# WS2812-Ring_v100.net
KiCad netlist of a schematic drawn in EAGLE
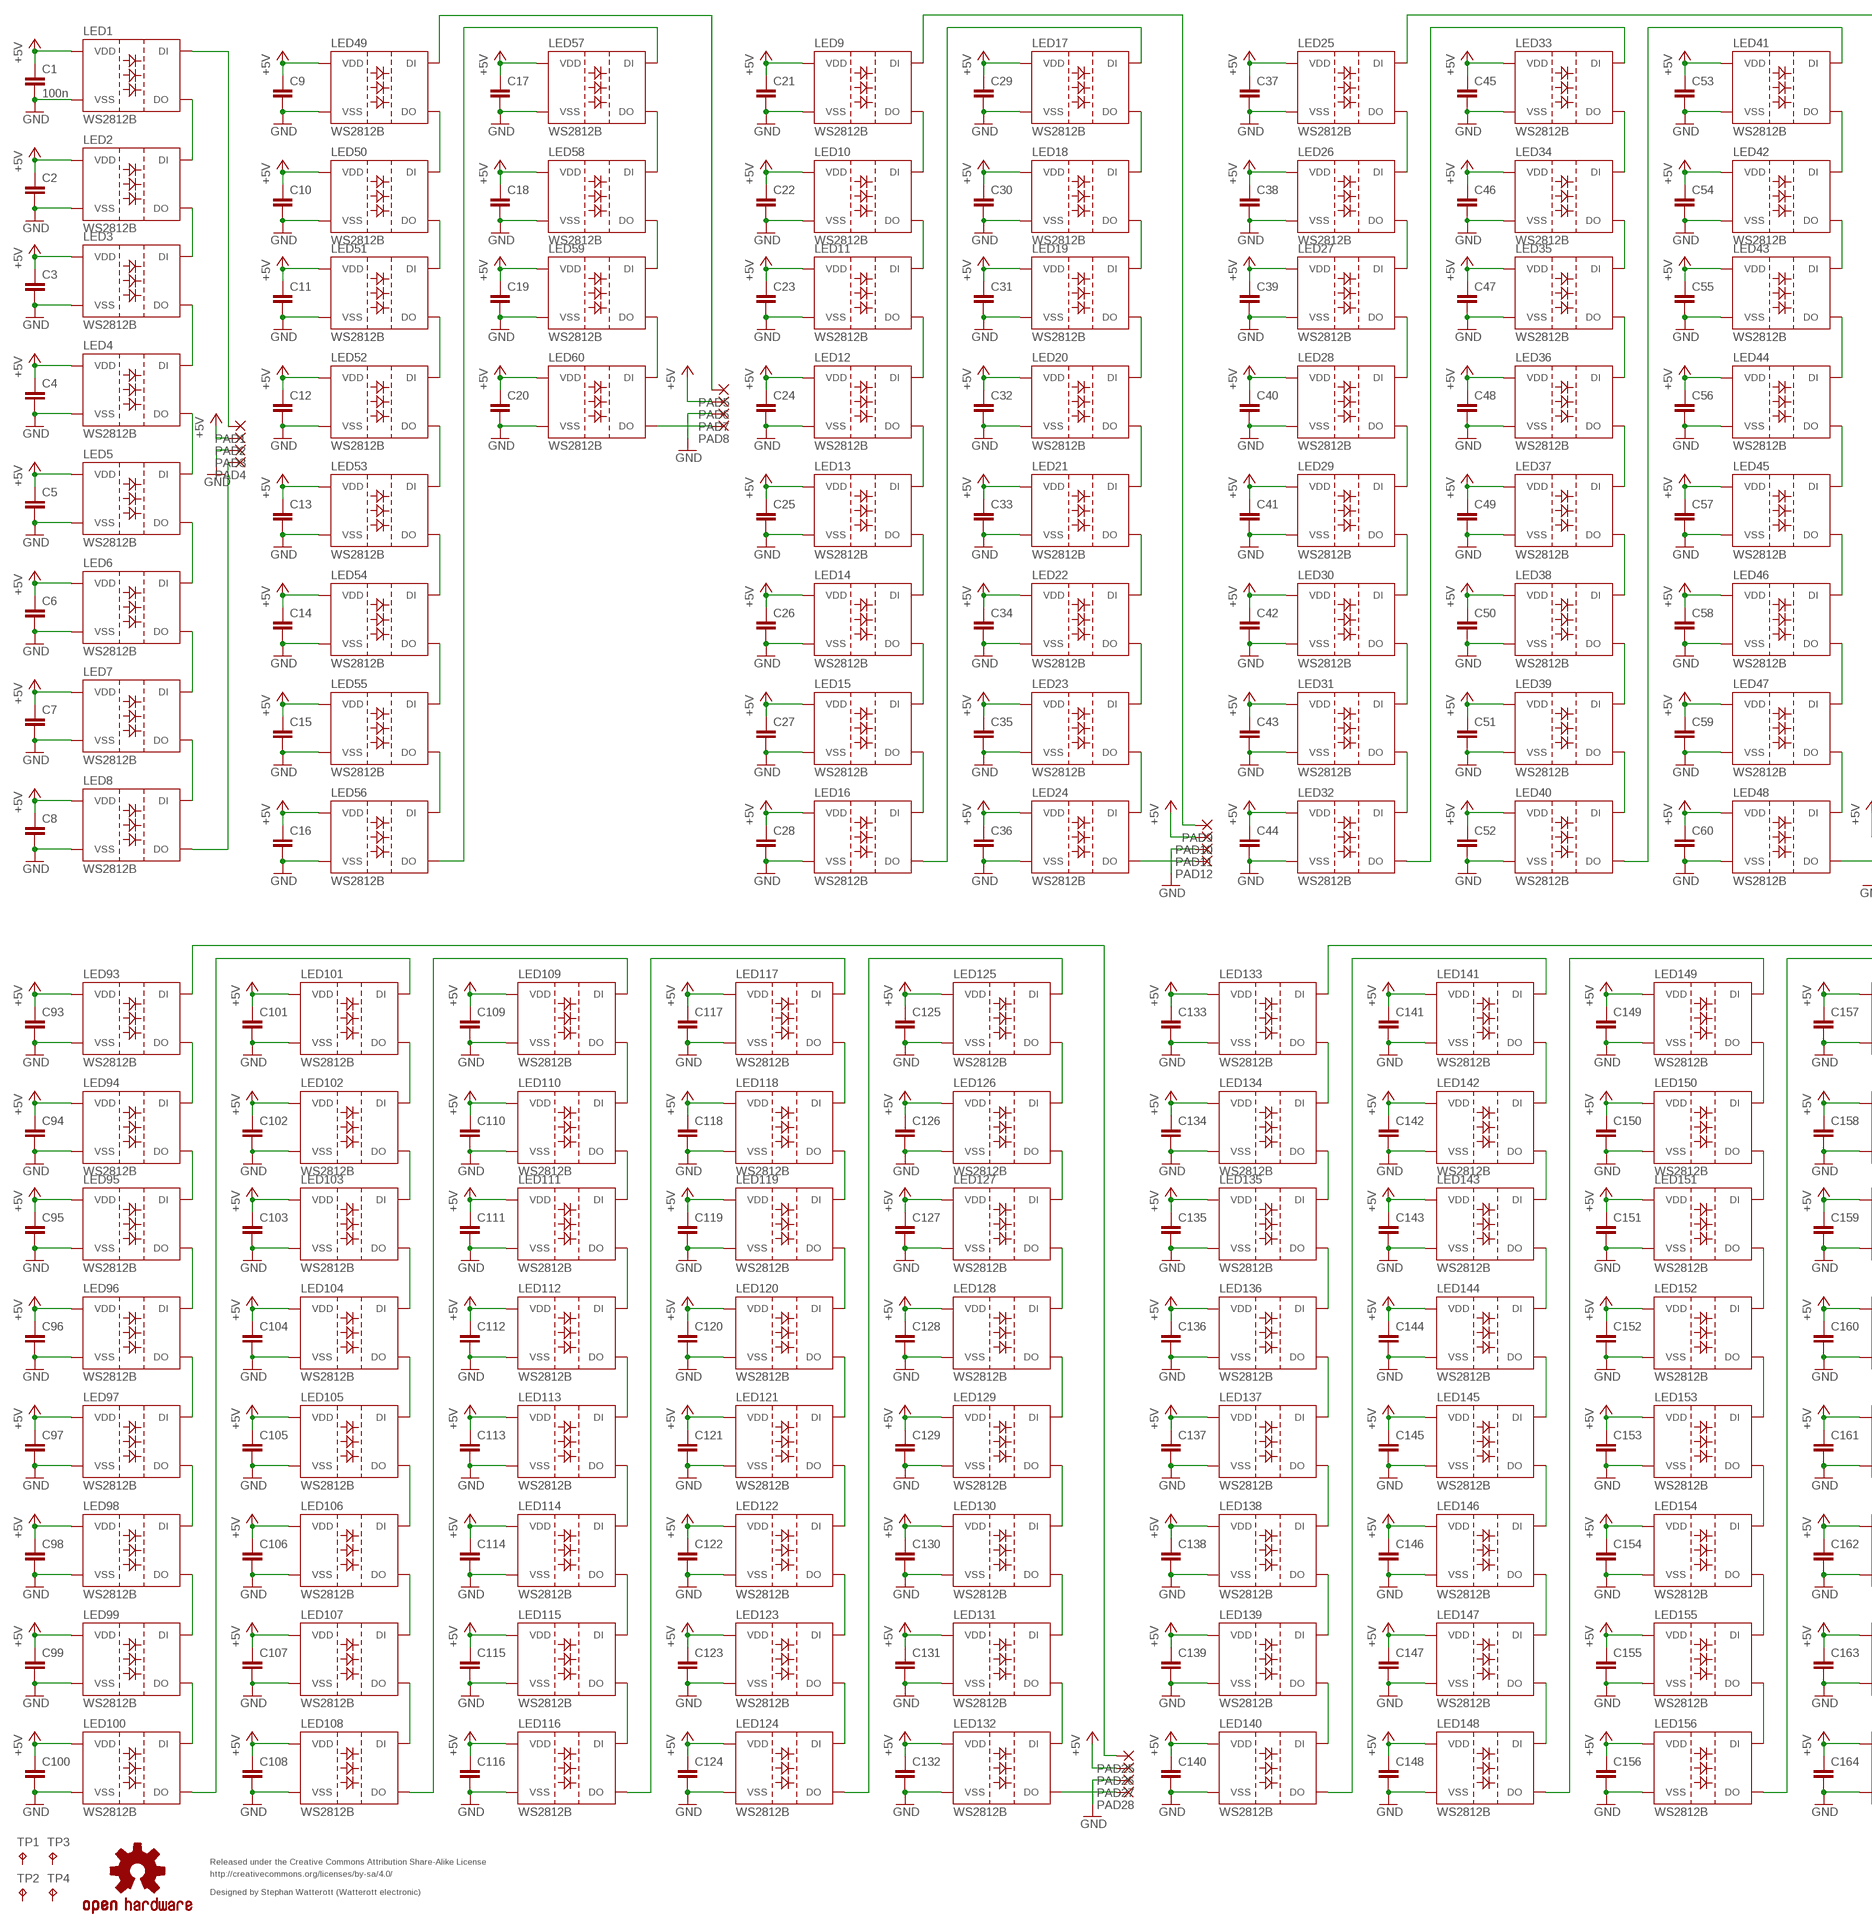
[diagram p0: schematic, sheet 1, part 1 of 2]
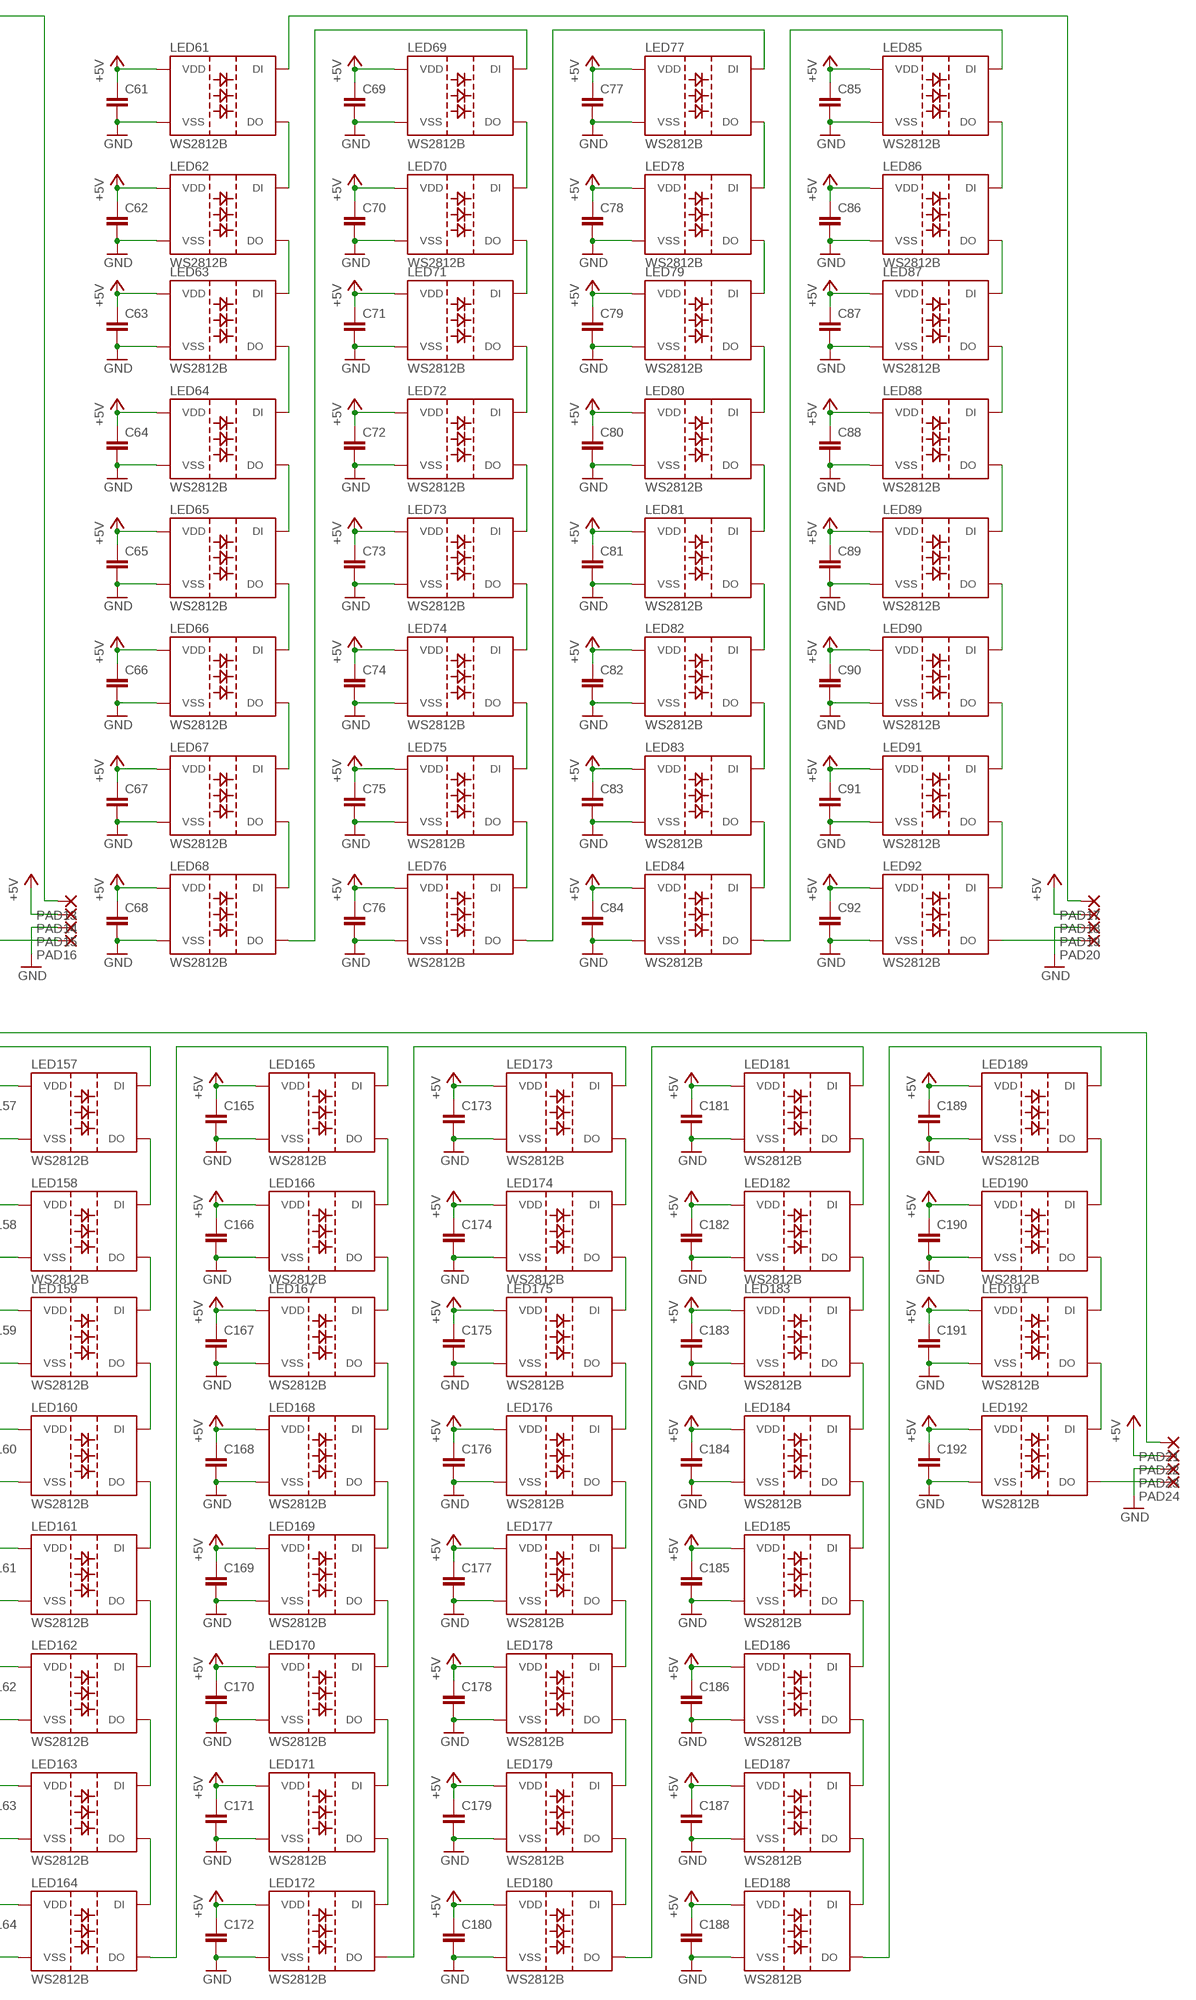
[diagram p1: schematic, sheet 1, part 2 of 2]

(export (version "E")
  (design (tool "Eeschema 10.0.6"))
  (components
    (comp (ref "C1")
      (value "100n")
      (footprint "eagle-import:C0402K")
      (libsource (lib "eagle-import") (part "C-EUC0402K"))
    )
    (comp (ref "C2")
      (value "C-EUC0402K")
      (footprint "eagle-import:C0402K")
      (libsource (lib "eagle-import") (part "C-EUC0402K"))
    )
    (comp (ref "C3")
      (value "C-EUC0402K")
      (footprint "eagle-import:C0402K")
      (libsource (lib "eagle-import") (part "C-EUC0402K"))
    )
    (comp (ref "C4")
      (value "C-EUC0402K")
      (footprint "eagle-import:C0402K")
      (libsource (lib "eagle-import") (part "C-EUC0402K"))
    )
    (comp (ref "C5")
      (value "C-EUC0402K")
      (footprint "eagle-import:C0402K")
      (libsource (lib "eagle-import") (part "C-EUC0402K"))
    )
    (comp (ref "C6")
      (value "C-EUC0402K")
      (footprint "eagle-import:C0402K")
      (libsource (lib "eagle-import") (part "C-EUC0402K"))
    )
    (comp (ref "C7")
      (value "C-EUC0402K")
      (footprint "eagle-import:C0402K")
      (libsource (lib "eagle-import") (part "C-EUC0402K"))
    )
    (comp (ref "C8")
      (value "C-EUC0402K")
      (footprint "eagle-import:C0402K")
      (libsource (lib "eagle-import") (part "C-EUC0402K"))
    )
    (comp (ref "C9")
      (value "C-EUC0402K")
      (footprint "eagle-import:C0402K")
      (libsource (lib "eagle-import") (part "C-EUC0402K"))
    )
    (comp (ref "C10")
      (value "C-EUC0402K")
      (footprint "eagle-import:C0402K")
      (libsource (lib "eagle-import") (part "C-EUC0402K"))
    )
    (comp (ref "C11")
      (value "C-EUC0402K")
      (footprint "eagle-import:C0402K")
      (libsource (lib "eagle-import") (part "C-EUC0402K"))
    )
    (comp (ref "C12")
      (value "C-EUC0402K")
      (footprint "eagle-import:C0402K")
      (libsource (lib "eagle-import") (part "C-EUC0402K"))
    )
    (comp (ref "C13")
      (value "C-EUC0402K")
      (footprint "eagle-import:C0402K")
      (libsource (lib "eagle-import") (part "C-EUC0402K"))
    )
    (comp (ref "C14")
      (value "C-EUC0402K")
      (footprint "eagle-import:C0402K")
      (libsource (lib "eagle-import") (part "C-EUC0402K"))
    )
    (comp (ref "C15")
      (value "C-EUC0402K")
      (footprint "eagle-import:C0402K")
      (libsource (lib "eagle-import") (part "C-EUC0402K"))
    )
    (comp (ref "C16")
      (value "C-EUC0402K")
      (footprint "eagle-import:C0402K")
      (libsource (lib "eagle-import") (part "C-EUC0402K"))
    )
    (comp (ref "C17")
      (value "C-EUC0402K")
      (footprint "eagle-import:C0402K")
      (libsource (lib "eagle-import") (part "C-EUC0402K"))
    )
    (comp (ref "C18")
      (value "C-EUC0402K")
      (footprint "eagle-import:C0402K")
      (libsource (lib "eagle-import") (part "C-EUC0402K"))
    )
    (comp (ref "C19")
      (value "C-EUC0402K")
      (footprint "eagle-import:C0402K")
      (libsource (lib "eagle-import") (part "C-EUC0402K"))
    )
    (comp (ref "C20")
      (value "C-EUC0402K")
      (footprint "eagle-import:C0402K")
      (libsource (lib "eagle-import") (part "C-EUC0402K"))
    )
    (comp (ref "C21")
      (value "C-EUC0402K")
      (footprint "eagle-import:C0402K")
      (libsource (lib "eagle-import") (part "C-EUC0402K"))
    )
    (comp (ref "C22")
      (value "C-EUC0402K")
      (footprint "eagle-import:C0402K")
      (libsource (lib "eagle-import") (part "C-EUC0402K"))
    )
    (comp (ref "C23")
      (value "C-EUC0402K")
      (footprint "eagle-import:C0402K")
      (libsource (lib "eagle-import") (part "C-EUC0402K"))
    )
    (comp (ref "C24")
      (value "C-EUC0402K")
      (footprint "eagle-import:C0402K")
      (libsource (lib "eagle-import") (part "C-EUC0402K"))
    )
    (comp (ref "C25")
      (value "C-EUC0402K")
      (footprint "eagle-import:C0402K")
      (libsource (lib "eagle-import") (part "C-EUC0402K"))
    )
    (comp (ref "C26")
      (value "C-EUC0402K")
      (footprint "eagle-import:C0402K")
      (libsource (lib "eagle-import") (part "C-EUC0402K"))
    )
    (comp (ref "C27")
      (value "C-EUC0402K")
      (footprint "eagle-import:C0402K")
      (libsource (lib "eagle-import") (part "C-EUC0402K"))
    )
    (comp (ref "C28")
      (value "C-EUC0402K")
      (footprint "eagle-import:C0402K")
      (libsource (lib "eagle-import") (part "C-EUC0402K"))
    )
    (comp (ref "C29")
      (value "C-EUC0402K")
      (footprint "eagle-import:C0402K")
      (libsource (lib "eagle-import") (part "C-EUC0402K"))
    )
    (comp (ref "C30")
      (value "C-EUC0402K")
      (footprint "eagle-import:C0402K")
      (libsource (lib "eagle-import") (part "C-EUC0402K"))
    )
    (comp (ref "C31")
      (value "C-EUC0402K")
      (footprint "eagle-import:C0402K")
      (libsource (lib "eagle-import") (part "C-EUC0402K"))
    )
    (comp (ref "C32")
      (value "C-EUC0402K")
      (footprint "eagle-import:C0402K")
      (libsource (lib "eagle-import") (part "C-EUC0402K"))
    )
    (comp (ref "C33")
      (value "C-EUC0402K")
      (footprint "eagle-import:C0402K")
      (libsource (lib "eagle-import") (part "C-EUC0402K"))
    )
    (comp (ref "C34")
      (value "C-EUC0402K")
      (footprint "eagle-import:C0402K")
      (libsource (lib "eagle-import") (part "C-EUC0402K"))
    )
    (comp (ref "C35")
      (value "C-EUC0402K")
      (footprint "eagle-import:C0402K")
      (libsource (lib "eagle-import") (part "C-EUC0402K"))
    )
    (comp (ref "C36")
      (value "C-EUC0402K")
      (footprint "eagle-import:C0402K")
      (libsource (lib "eagle-import") (part "C-EUC0402K"))
    )
    (comp (ref "C37")
      (value "C-EUC0402K")
      (footprint "eagle-import:C0402K")
      (libsource (lib "eagle-import") (part "C-EUC0402K"))
    )
    (comp (ref "C38")
      (value "C-EUC0402K")
      (footprint "eagle-import:C0402K")
      (libsource (lib "eagle-import") (part "C-EUC0402K"))
    )
    (comp (ref "C39")
      (value "C-EUC0402K")
      (footprint "eagle-import:C0402K")
      (libsource (lib "eagle-import") (part "C-EUC0402K"))
    )
    (comp (ref "C40")
      (value "C-EUC0402K")
      (footprint "eagle-import:C0402K")
      (libsource (lib "eagle-import") (part "C-EUC0402K"))
    )
    (comp (ref "C41")
      (value "C-EUC0402K")
      (footprint "eagle-import:C0402K")
      (libsource (lib "eagle-import") (part "C-EUC0402K"))
    )
    (comp (ref "C42")
      (value "C-EUC0402K")
      (footprint "eagle-import:C0402K")
      (libsource (lib "eagle-import") (part "C-EUC0402K"))
    )
    (comp (ref "C43")
      (value "C-EUC0402K")
      (footprint "eagle-import:C0402K")
      (libsource (lib "eagle-import") (part "C-EUC0402K"))
    )
    (comp (ref "C44")
      (value "C-EUC0402K")
      (footprint "eagle-import:C0402K")
      (libsource (lib "eagle-import") (part "C-EUC0402K"))
    )
    (comp (ref "C45")
      (value "C-EUC0402K")
      (footprint "eagle-import:C0402K")
      (libsource (lib "eagle-import") (part "C-EUC0402K"))
    )
    (comp (ref "C46")
      (value "C-EUC0402K")
      (footprint "eagle-import:C0402K")
      (libsource (lib "eagle-import") (part "C-EUC0402K"))
    )
    (comp (ref "C47")
      (value "C-EUC0402K")
      (footprint "eagle-import:C0402K")
      (libsource (lib "eagle-import") (part "C-EUC0402K"))
    )
    (comp (ref "C48")
      (value "C-EUC0402K")
      (footprint "eagle-import:C0402K")
      (libsource (lib "eagle-import") (part "C-EUC0402K"))
    )
    (comp (ref "C49")
      (value "C-EUC0402K")
      (footprint "eagle-import:C0402K")
      (libsource (lib "eagle-import") (part "C-EUC0402K"))
    )
    (comp (ref "C50")
      (value "C-EUC0402K")
      (footprint "eagle-import:C0402K")
      (libsource (lib "eagle-import") (part "C-EUC0402K"))
    )
    (comp (ref "C51")
      (value "C-EUC0402K")
      (footprint "eagle-import:C0402K")
      (libsource (lib "eagle-import") (part "C-EUC0402K"))
    )
    (comp (ref "C52")
      (value "C-EUC0402K")
      (footprint "eagle-import:C0402K")
      (libsource (lib "eagle-import") (part "C-EUC0402K"))
    )
    (comp (ref "C53")
      (value "C-EUC0402K")
      (footprint "eagle-import:C0402K")
      (libsource (lib "eagle-import") (part "C-EUC0402K"))
    )
    (comp (ref "C54")
      (value "C-EUC0402K")
      (footprint "eagle-import:C0402K")
      (libsource (lib "eagle-import") (part "C-EUC0402K"))
    )
    (comp (ref "C55")
      (value "C-EUC0402K")
      (footprint "eagle-import:C0402K")
      (libsource (lib "eagle-import") (part "C-EUC0402K"))
    )
    (comp (ref "C56")
      (value "C-EUC0402K")
      (footprint "eagle-import:C0402K")
      (libsource (lib "eagle-import") (part "C-EUC0402K"))
    )
    (comp (ref "C57")
      (value "C-EUC0402K")
      (footprint "eagle-import:C0402K")
      (libsource (lib "eagle-import") (part "C-EUC0402K"))
    )
    (comp (ref "C58")
      (value "C-EUC0402K")
      (footprint "eagle-import:C0402K")
      (libsource (lib "eagle-import") (part "C-EUC0402K"))
    )
    (comp (ref "C59")
      (value "C-EUC0402K")
      (footprint "eagle-import:C0402K")
      (libsource (lib "eagle-import") (part "C-EUC0402K"))
    )
    (comp (ref "C60")
      (value "C-EUC0402K")
      (footprint "eagle-import:C0402K")
      (libsource (lib "eagle-import") (part "C-EUC0402K"))
    )
    (comp (ref "C61")
      (value "C-EUC0402K")
      (footprint "eagle-import:C0402K")
      (libsource (lib "eagle-import") (part "C-EUC0402K"))
    )
    (comp (ref "C62")
      (value "C-EUC0402K")
      (footprint "eagle-import:C0402K")
      (libsource (lib "eagle-import") (part "C-EUC0402K"))
    )
    (comp (ref "C63")
      (value "C-EUC0402K")
      (footprint "eagle-import:C0402K")
      (libsource (lib "eagle-import") (part "C-EUC0402K"))
    )
    (comp (ref "C64")
      (value "C-EUC0402K")
      (footprint "eagle-import:C0402K")
      (libsource (lib "eagle-import") (part "C-EUC0402K"))
    )
    (comp (ref "C65")
      (value "C-EUC0402K")
      (footprint "eagle-import:C0402K")
      (libsource (lib "eagle-import") (part "C-EUC0402K"))
    )
    (comp (ref "C66")
      (value "C-EUC0402K")
      (footprint "eagle-import:C0402K")
      (libsource (lib "eagle-import") (part "C-EUC0402K"))
    )
    (comp (ref "C67")
      (value "C-EUC0402K")
      (footprint "eagle-import:C0402K")
      (libsource (lib "eagle-import") (part "C-EUC0402K"))
    )
    (comp (ref "C68")
      (value "C-EUC0402K")
      (footprint "eagle-import:C0402K")
      (libsource (lib "eagle-import") (part "C-EUC0402K"))
    )
    (comp (ref "C69")
      (value "C-EUC0402K")
      (footprint "eagle-import:C0402K")
      (libsource (lib "eagle-import") (part "C-EUC0402K"))
    )
    (comp (ref "C70")
      (value "C-EUC0402K")
      (footprint "eagle-import:C0402K")
      (libsource (lib "eagle-import") (part "C-EUC0402K"))
    )
    (comp (ref "C71")
      (value "C-EUC0402K")
      (footprint "eagle-import:C0402K")
      (libsource (lib "eagle-import") (part "C-EUC0402K"))
    )
    (comp (ref "C72")
      (value "C-EUC0402K")
      (footprint "eagle-import:C0402K")
      (libsource (lib "eagle-import") (part "C-EUC0402K"))
    )
    (comp (ref "C73")
      (value "C-EUC0402K")
      (footprint "eagle-import:C0402K")
      (libsource (lib "eagle-import") (part "C-EUC0402K"))
    )
    (comp (ref "C74")
      (value "C-EUC0402K")
      (footprint "eagle-import:C0402K")
      (libsource (lib "eagle-import") (part "C-EUC0402K"))
    )
    (comp (ref "C75")
      (value "C-EUC0402K")
      (footprint "eagle-import:C0402K")
      (libsource (lib "eagle-import") (part "C-EUC0402K"))
    )
    (comp (ref "C76")
      (value "C-EUC0402K")
      (footprint "eagle-import:C0402K")
      (libsource (lib "eagle-import") (part "C-EUC0402K"))
    )
    (comp (ref "C77")
      (value "C-EUC0402K")
      (footprint "eagle-import:C0402K")
      (libsource (lib "eagle-import") (part "C-EUC0402K"))
    )
    (comp (ref "C78")
      (value "C-EUC0402K")
      (footprint "eagle-import:C0402K")
      (libsource (lib "eagle-import") (part "C-EUC0402K"))
    )
    (comp (ref "C79")
      (value "C-EUC0402K")
      (footprint "eagle-import:C0402K")
      (libsource (lib "eagle-import") (part "C-EUC0402K"))
    )
    (comp (ref "C80")
      (value "C-EUC0402K")
      (footprint "eagle-import:C0402K")
      (libsource (lib "eagle-import") (part "C-EUC0402K"))
    )
    (comp (ref "C81")
      (value "C-EUC0402K")
      (footprint "eagle-import:C0402K")
      (libsource (lib "eagle-import") (part "C-EUC0402K"))
    )
    (comp (ref "C82")
      (value "C-EUC0402K")
      (footprint "eagle-import:C0402K")
      (libsource (lib "eagle-import") (part "C-EUC0402K"))
    )
    (comp (ref "C83")
      (value "C-EUC0402K")
      (footprint "eagle-import:C0402K")
      (libsource (lib "eagle-import") (part "C-EUC0402K"))
    )
    (comp (ref "C84")
      (value "C-EUC0402K")
      (footprint "eagle-import:C0402K")
      (libsource (lib "eagle-import") (part "C-EUC0402K"))
    )
    (comp (ref "C85")
      (value "C-EUC0402K")
      (footprint "eagle-import:C0402K")
      (libsource (lib "eagle-import") (part "C-EUC0402K"))
    )
    (comp (ref "C86")
      (value "C-EUC0402K")
      (footprint "eagle-import:C0402K")
      (libsource (lib "eagle-import") (part "C-EUC0402K"))
    )
    (comp (ref "C87")
      (value "C-EUC0402K")
      (footprint "eagle-import:C0402K")
      (libsource (lib "eagle-import") (part "C-EUC0402K"))
    )
    (comp (ref "C88")
      (value "C-EUC0402K")
      (footprint "eagle-import:C0402K")
      (libsource (lib "eagle-import") (part "C-EUC0402K"))
    )
    (comp (ref "C89")
      (value "C-EUC0402K")
      (footprint "eagle-import:C0402K")
      (libsource (lib "eagle-import") (part "C-EUC0402K"))
    )
    (comp (ref "C90")
      (value "C-EUC0402K")
      (footprint "eagle-import:C0402K")
      (libsource (lib "eagle-import") (part "C-EUC0402K"))
    )
    (comp (ref "C91")
      (value "C-EUC0402K")
      (footprint "eagle-import:C0402K")
      (libsource (lib "eagle-import") (part "C-EUC0402K"))
    )
    (comp (ref "C92")
      (value "C-EUC0402K")
      (footprint "eagle-import:C0402K")
      (libsource (lib "eagle-import") (part "C-EUC0402K"))
    )
    (comp (ref "C93")
      (value "C-EUC0402K")
      (footprint "eagle-import:C0402K")
      (libsource (lib "eagle-import") (part "C-EUC0402K"))
    )
    (comp (ref "C94")
      (value "C-EUC0402K")
      (footprint "eagle-import:C0402K")
      (libsource (lib "eagle-import") (part "C-EUC0402K"))
    )
    (comp (ref "C95")
      (value "C-EUC0402K")
      (footprint "eagle-import:C0402K")
      (libsource (lib "eagle-import") (part "C-EUC0402K"))
    )
    (comp (ref "C96")
      (value "C-EUC0402K")
      (footprint "eagle-import:C0402K")
      (libsource (lib "eagle-import") (part "C-EUC0402K"))
    )
    (comp (ref "C97")
      (value "C-EUC0402K")
      (footprint "eagle-import:C0402K")
      (libsource (lib "eagle-import") (part "C-EUC0402K"))
    )
    (comp (ref "C98")
      (value "C-EUC0402K")
      (footprint "eagle-import:C0402K")
      (libsource (lib "eagle-import") (part "C-EUC0402K"))
    )
    (comp (ref "C99")
      (value "C-EUC0402K")
      (footprint "eagle-import:C0402K")
      (libsource (lib "eagle-import") (part "C-EUC0402K"))
    )
    (comp (ref "C100")
      (value "C-EUC0402K")
      (footprint "eagle-import:C0402K")
      (libsource (lib "eagle-import") (part "C-EUC0402K"))
    )
    (comp (ref "C101")
      (value "C-EUC0402K")
      (footprint "eagle-import:C0402K")
      (libsource (lib "eagle-import") (part "C-EUC0402K"))
    )
    (comp (ref "C102")
      (value "C-EUC0402K")
      (footprint "eagle-import:C0402K")
      (libsource (lib "eagle-import") (part "C-EUC0402K"))
    )
    (comp (ref "C103")
      (value "C-EUC0402K")
      (footprint "eagle-import:C0402K")
      (libsource (lib "eagle-import") (part "C-EUC0402K"))
    )
    (comp (ref "C104")
      (value "C-EUC0402K")
      (footprint "eagle-import:C0402K")
      (libsource (lib "eagle-import") (part "C-EUC0402K"))
    )
    (comp (ref "C105")
      (value "C-EUC0402K")
      (footprint "eagle-import:C0402K")
      (libsource (lib "eagle-import") (part "C-EUC0402K"))
    )
    (comp (ref "C106")
      (value "C-EUC0402K")
      (footprint "eagle-import:C0402K")
      (libsource (lib "eagle-import") (part "C-EUC0402K"))
    )
    (comp (ref "C107")
      (value "C-EUC0402K")
      (footprint "eagle-import:C0402K")
      (libsource (lib "eagle-import") (part "C-EUC0402K"))
    )
    (comp (ref "C108")
      (value "C-EUC0402K")
      (footprint "eagle-import:C0402K")
      (libsource (lib "eagle-import") (part "C-EUC0402K"))
    )
    (comp (ref "C109")
      (value "C-EUC0402K")
      (footprint "eagle-import:C0402K")
      (libsource (lib "eagle-import") (part "C-EUC0402K"))
    )
    (comp (ref "C110")
      (value "C-EUC0402K")
      (footprint "eagle-import:C0402K")
      (libsource (lib "eagle-import") (part "C-EUC0402K"))
    )
    (comp (ref "C111")
      (value "C-EUC0402K")
      (footprint "eagle-import:C0402K")
      (libsource (lib "eagle-import") (part "C-EUC0402K"))
    )
    (comp (ref "C112")
      (value "C-EUC0402K")
      (footprint "eagle-import:C0402K")
      (libsource (lib "eagle-import") (part "C-EUC0402K"))
    )
    (comp (ref "C113")
      (value "C-EUC0402K")
      (footprint "eagle-import:C0402K")
      (libsource (lib "eagle-import") (part "C-EUC0402K"))
    )
    (comp (ref "C114")
      (value "C-EUC0402K")
      (footprint "eagle-import:C0402K")
      (libsource (lib "eagle-import") (part "C-EUC0402K"))
    )
    (comp (ref "C115")
      (value "C-EUC0402K")
      (footprint "eagle-import:C0402K")
      (libsource (lib "eagle-import") (part "C-EUC0402K"))
    )
    (comp (ref "C116")
      (value "C-EUC0402K")
      (footprint "eagle-import:C0402K")
      (libsource (lib "eagle-import") (part "C-EUC0402K"))
    )
    (comp (ref "C117")
      (value "C-EUC0402K")
      (footprint "eagle-import:C0402K")
      (libsource (lib "eagle-import") (part "C-EUC0402K"))
    )
    (comp (ref "C118")
      (value "C-EUC0402K")
      (footprint "eagle-import:C0402K")
      (libsource (lib "eagle-import") (part "C-EUC0402K"))
    )
    (comp (ref "C119")
      (value "C-EUC0402K")
      (footprint "eagle-import:C0402K")
      (libsource (lib "eagle-import") (part "C-EUC0402K"))
    )
    (comp (ref "C120")
      (value "C-EUC0402K")
      (footprint "eagle-import:C0402K")
      (libsource (lib "eagle-import") (part "C-EUC0402K"))
    )
    (comp (ref "C121")
      (value "C-EUC0402K")
      (footprint "eagle-import:C0402K")
      (libsource (lib "eagle-import") (part "C-EUC0402K"))
    )
    (comp (ref "C122")
      (value "C-EUC0402K")
      (footprint "eagle-import:C0402K")
      (libsource (lib "eagle-import") (part "C-EUC0402K"))
    )
    (comp (ref "C123")
      (value "C-EUC0402K")
      (footprint "eagle-import:C0402K")
      (libsource (lib "eagle-import") (part "C-EUC0402K"))
    )
    (comp (ref "C124")
      (value "C-EUC0402K")
      (footprint "eagle-import:C0402K")
      (libsource (lib "eagle-import") (part "C-EUC0402K"))
    )
    (comp (ref "C125")
      (value "C-EUC0402K")
      (footprint "eagle-import:C0402K")
      (libsource (lib "eagle-import") (part "C-EUC0402K"))
    )
    (comp (ref "C126")
      (value "C-EUC0402K")
      (footprint "eagle-import:C0402K")
      (libsource (lib "eagle-import") (part "C-EUC0402K"))
    )
    (comp (ref "C127")
      (value "C-EUC0402K")
      (footprint "eagle-import:C0402K")
      (libsource (lib "eagle-import") (part "C-EUC0402K"))
    )
    (comp (ref "C128")
      (value "C-EUC0402K")
      (footprint "eagle-import:C0402K")
      (libsource (lib "eagle-import") (part "C-EUC0402K"))
    )
    (comp (ref "C129")
      (value "C-EUC0402K")
      (footprint "eagle-import:C0402K")
      (libsource (lib "eagle-import") (part "C-EUC0402K"))
    )
    (comp (ref "C130")
      (value "C-EUC0402K")
      (footprint "eagle-import:C0402K")
      (libsource (lib "eagle-import") (part "C-EUC0402K"))
    )
    (comp (ref "C131")
      (value "C-EUC0402K")
      (footprint "eagle-import:C0402K")
      (libsource (lib "eagle-import") (part "C-EUC0402K"))
    )
    (comp (ref "C132")
      (value "C-EUC0402K")
      (footprint "eagle-import:C0402K")
      (libsource (lib "eagle-import") (part "C-EUC0402K"))
    )
    (comp (ref "C133")
      (value "C-EUC0402K")
      (footprint "eagle-import:C0402K")
      (libsource (lib "eagle-import") (part "C-EUC0402K"))
    )
    (comp (ref "C134")
      (value "C-EUC0402K")
      (footprint "eagle-import:C0402K")
      (libsource (lib "eagle-import") (part "C-EUC0402K"))
    )
    (comp (ref "C135")
      (value "C-EUC0402K")
      (footprint "eagle-import:C0402K")
      (libsource (lib "eagle-import") (part "C-EUC0402K"))
    )
    (comp (ref "C136")
      (value "C-EUC0402K")
      (footprint "eagle-import:C0402K")
      (libsource (lib "eagle-import") (part "C-EUC0402K"))
    )
    (comp (ref "C137")
      (value "C-EUC0402K")
      (footprint "eagle-import:C0402K")
      (libsource (lib "eagle-import") (part "C-EUC0402K"))
    )
    (comp (ref "C138")
      (value "C-EUC0402K")
      (footprint "eagle-import:C0402K")
      (libsource (lib "eagle-import") (part "C-EUC0402K"))
    )
    (comp (ref "C139")
      (value "C-EUC0402K")
      (footprint "eagle-import:C0402K")
      (libsource (lib "eagle-import") (part "C-EUC0402K"))
    )
    (comp (ref "C140")
      (value "C-EUC0402K")
      (footprint "eagle-import:C0402K")
      (libsource (lib "eagle-import") (part "C-EUC0402K"))
    )
    (comp (ref "C141")
      (value "C-EUC0402K")
      (footprint "eagle-import:C0402K")
      (libsource (lib "eagle-import") (part "C-EUC0402K"))
    )
    (comp (ref "C142")
      (value "C-EUC0402K")
      (footprint "eagle-import:C0402K")
      (libsource (lib "eagle-import") (part "C-EUC0402K"))
    )
    (comp (ref "C143")
      (value "C-EUC0402K")
      (footprint "eagle-import:C0402K")
      (libsource (lib "eagle-import") (part "C-EUC0402K"))
    )
    (comp (ref "C144")
      (value "C-EUC0402K")
      (footprint "eagle-import:C0402K")
      (libsource (lib "eagle-import") (part "C-EUC0402K"))
    )
    (comp (ref "C145")
      (value "C-EUC0402K")
      (footprint "eagle-import:C0402K")
      (libsource (lib "eagle-import") (part "C-EUC0402K"))
    )
    (comp (ref "C146")
      (value "C-EUC0402K")
      (footprint "eagle-import:C0402K")
      (libsource (lib "eagle-import") (part "C-EUC0402K"))
    )
    (comp (ref "C147")
      (value "C-EUC0402K")
      (footprint "eagle-import:C0402K")
      (libsource (lib "eagle-import") (part "C-EUC0402K"))
    )
    (comp (ref "C148")
      (value "C-EUC0402K")
      (footprint "eagle-import:C0402K")
      (libsource (lib "eagle-import") (part "C-EUC0402K"))
    )
    (comp (ref "C149")
      (value "C-EUC0402K")
      (footprint "eagle-import:C0402K")
      (libsource (lib "eagle-import") (part "C-EUC0402K"))
    )
    (comp (ref "C150")
      (value "C-EUC0402K")
      (footprint "eagle-import:C0402K")
      (libsource (lib "eagle-import") (part "C-EUC0402K"))
    )
    (comp (ref "C151")
      (value "C-EUC0402K")
      (footprint "eagle-import:C0402K")
      (libsource (lib "eagle-import") (part "C-EUC0402K"))
    )
    (comp (ref "C152")
      (value "C-EUC0402K")
      (footprint "eagle-import:C0402K")
      (libsource (lib "eagle-import") (part "C-EUC0402K"))
    )
    (comp (ref "C153")
      (value "C-EUC0402K")
      (footprint "eagle-import:C0402K")
      (libsource (lib "eagle-import") (part "C-EUC0402K"))
    )
    (comp (ref "C154")
      (value "C-EUC0402K")
      (footprint "eagle-import:C0402K")
      (libsource (lib "eagle-import") (part "C-EUC0402K"))
    )
    (comp (ref "C155")
      (value "C-EUC0402K")
      (footprint "eagle-import:C0402K")
      (libsource (lib "eagle-import") (part "C-EUC0402K"))
    )
    (comp (ref "C156")
      (value "C-EUC0402K")
      (footprint "eagle-import:C0402K")
      (libsource (lib "eagle-import") (part "C-EUC0402K"))
    )
    (comp (ref "C157")
      (value "C-EUC0402K")
      (footprint "eagle-import:C0402K")
      (libsource (lib "eagle-import") (part "C-EUC0402K"))
    )
    (comp (ref "C158")
      (value "C-EUC0402K")
      (footprint "eagle-import:C0402K")
      (libsource (lib "eagle-import") (part "C-EUC0402K"))
    )
    (comp (ref "C159")
      (value "C-EUC0402K")
      (footprint "eagle-import:C0402K")
      (libsource (lib "eagle-import") (part "C-EUC0402K"))
    )
    (comp (ref "C160")
      (value "C-EUC0402K")
      (footprint "eagle-import:C0402K")
      (libsource (lib "eagle-import") (part "C-EUC0402K"))
    )
    (comp (ref "C161")
      (value "C-EUC0402K")
      (footprint "eagle-import:C0402K")
      (libsource (lib "eagle-import") (part "C-EUC0402K"))
    )
    (comp (ref "C162")
      (value "C-EUC0402K")
      (footprint "eagle-import:C0402K")
      (libsource (lib "eagle-import") (part "C-EUC0402K"))
    )
    (comp (ref "C163")
      (value "C-EUC0402K")
      (footprint "eagle-import:C0402K")
      (libsource (lib "eagle-import") (part "C-EUC0402K"))
    )
    (comp (ref "C164")
      (value "C-EUC0402K")
      (footprint "eagle-import:C0402K")
      (libsource (lib "eagle-import") (part "C-EUC0402K"))
    )
    (comp (ref "C165")
      (value "C-EUC0402K")
      (footprint "eagle-import:C0402K")
      (libsource (lib "eagle-import") (part "C-EUC0402K"))
    )
    (comp (ref "C166")
      (value "C-EUC0402K")
      (footprint "eagle-import:C0402K")
      (libsource (lib "eagle-import") (part "C-EUC0402K"))
    )
    (comp (ref "C167")
      (value "C-EUC0402K")
      (footprint "eagle-import:C0402K")
      (libsource (lib "eagle-import") (part "C-EUC0402K"))
    )
    (comp (ref "C168")
      (value "C-EUC0402K")
      (footprint "eagle-import:C0402K")
      (libsource (lib "eagle-import") (part "C-EUC0402K"))
    )
    (comp (ref "C169")
      (value "C-EUC0402K")
      (footprint "eagle-import:C0402K")
      (libsource (lib "eagle-import") (part "C-EUC0402K"))
    )
    (comp (ref "C170")
      (value "C-EUC0402K")
      (footprint "eagle-import:C0402K")
      (libsource (lib "eagle-import") (part "C-EUC0402K"))
    )
    (comp (ref "C171")
      (value "C-EUC0402K")
      (footprint "eagle-import:C0402K")
      (libsource (lib "eagle-import") (part "C-EUC0402K"))
    )
    (comp (ref "C172")
      (value "C-EUC0402K")
      (footprint "eagle-import:C0402K")
      (libsource (lib "eagle-import") (part "C-EUC0402K"))
    )
    (comp (ref "C173")
      (value "C-EUC0402K")
      (footprint "eagle-import:C0402K")
      (libsource (lib "eagle-import") (part "C-EUC0402K"))
    )
    (comp (ref "C174")
      (value "C-EUC0402K")
      (footprint "eagle-import:C0402K")
      (libsource (lib "eagle-import") (part "C-EUC0402K"))
    )
    (comp (ref "C175")
      (value "C-EUC0402K")
      (footprint "eagle-import:C0402K")
      (libsource (lib "eagle-import") (part "C-EUC0402K"))
    )
    (comp (ref "C176")
      (value "C-EUC0402K")
      (footprint "eagle-import:C0402K")
      (libsource (lib "eagle-import") (part "C-EUC0402K"))
    )
    (comp (ref "C177")
      (value "C-EUC0402K")
      (footprint "eagle-import:C0402K")
      (libsource (lib "eagle-import") (part "C-EUC0402K"))
    )
    (comp (ref "C178")
      (value "C-EUC0402K")
      (footprint "eagle-import:C0402K")
      (libsource (lib "eagle-import") (part "C-EUC0402K"))
    )
    (comp (ref "C179")
      (value "C-EUC0402K")
      (footprint "eagle-import:C0402K")
      (libsource (lib "eagle-import") (part "C-EUC0402K"))
    )
    (comp (ref "C180")
      (value "C-EUC0402K")
      (footprint "eagle-import:C0402K")
      (libsource (lib "eagle-import") (part "C-EUC0402K"))
    )
    (comp (ref "C181")
      (value "C-EUC0402K")
      (footprint "eagle-import:C0402K")
      (libsource (lib "eagle-import") (part "C-EUC0402K"))
    )
    (comp (ref "C182")
      (value "C-EUC0402K")
      (footprint "eagle-import:C0402K")
      (libsource (lib "eagle-import") (part "C-EUC0402K"))
    )
    (comp (ref "C183")
      (value "C-EUC0402K")
      (footprint "eagle-import:C0402K")
      (libsource (lib "eagle-import") (part "C-EUC0402K"))
    )
    (comp (ref "C184")
      (value "C-EUC0402K")
      (footprint "eagle-import:C0402K")
      (libsource (lib "eagle-import") (part "C-EUC0402K"))
    )
    (comp (ref "C185")
      (value "C-EUC0402K")
      (footprint "eagle-import:C0402K")
      (libsource (lib "eagle-import") (part "C-EUC0402K"))
    )
    (comp (ref "C186")
      (value "C-EUC0402K")
      (footprint "eagle-import:C0402K")
      (libsource (lib "eagle-import") (part "C-EUC0402K"))
    )
    (comp (ref "C187")
      (value "C-EUC0402K")
      (footprint "eagle-import:C0402K")
      (libsource (lib "eagle-import") (part "C-EUC0402K"))
    )
    (comp (ref "C188")
      (value "C-EUC0402K")
      (footprint "eagle-import:C0402K")
      (libsource (lib "eagle-import") (part "C-EUC0402K"))
    )
    (comp (ref "C189")
      (value "C-EUC0402K")
      (footprint "eagle-import:C0402K")
      (libsource (lib "eagle-import") (part "C-EUC0402K"))
    )
    (comp (ref "C190")
      (value "C-EUC0402K")
      (footprint "eagle-import:C0402K")
      (libsource (lib "eagle-import") (part "C-EUC0402K"))
    )
    (comp (ref "C191")
      (value "C-EUC0402K")
      (footprint "eagle-import:C0402K")
      (libsource (lib "eagle-import") (part "C-EUC0402K"))
    )
    (comp (ref "C192")
      (value "C-EUC0402K")
      (footprint "eagle-import:C0402K")
      (libsource (lib "eagle-import") (part "C-EUC0402K"))
    )
    (comp (ref "LED1")
      (value "WS2812B")
      (footprint "eagle-import:WS2812B")
      (libsource (lib "eagle-import") (part "WS2812B"))
    )
    (comp (ref "LED2")
      (value "WS2812B")
      (footprint "eagle-import:WS2812B")
      (libsource (lib "eagle-import") (part "WS2812B"))
    )
    (comp (ref "LED3")
      (value "WS2812B")
      (footprint "eagle-import:WS2812B")
      (libsource (lib "eagle-import") (part "WS2812B"))
    )
    (comp (ref "LED4")
      (value "WS2812B")
      (footprint "eagle-import:WS2812B")
      (libsource (lib "eagle-import") (part "WS2812B"))
    )
    (comp (ref "LED5")
      (value "WS2812B")
      (footprint "eagle-import:WS2812B")
      (libsource (lib "eagle-import") (part "WS2812B"))
    )
    (comp (ref "LED6")
      (value "WS2812B")
      (footprint "eagle-import:WS2812B")
      (libsource (lib "eagle-import") (part "WS2812B"))
    )
    (comp (ref "LED7")
      (value "WS2812B")
      (footprint "eagle-import:WS2812B")
      (libsource (lib "eagle-import") (part "WS2812B"))
    )
    (comp (ref "LED8")
      (value "WS2812B")
      (footprint "eagle-import:WS2812B")
      (libsource (lib "eagle-import") (part "WS2812B"))
    )
    (comp (ref "LED9")
      (value "WS2812B")
      (footprint "eagle-import:WS2812B")
      (libsource (lib "eagle-import") (part "WS2812B"))
    )
    (comp (ref "LED10")
      (value "WS2812B")
      (footprint "eagle-import:WS2812B")
      (libsource (lib "eagle-import") (part "WS2812B"))
    )
    (comp (ref "LED11")
      (value "WS2812B")
      (footprint "eagle-import:WS2812B")
      (libsource (lib "eagle-import") (part "WS2812B"))
    )
    (comp (ref "LED12")
      (value "WS2812B")
      (footprint "eagle-import:WS2812B")
      (libsource (lib "eagle-import") (part "WS2812B"))
    )
    (comp (ref "LED13")
      (value "WS2812B")
      (footprint "eagle-import:WS2812B")
      (libsource (lib "eagle-import") (part "WS2812B"))
    )
    (comp (ref "LED14")
      (value "WS2812B")
      (footprint "eagle-import:WS2812B")
      (libsource (lib "eagle-import") (part "WS2812B"))
    )
    (comp (ref "LED15")
      (value "WS2812B")
      (footprint "eagle-import:WS2812B")
      (libsource (lib "eagle-import") (part "WS2812B"))
    )
    (comp (ref "LED16")
      (value "WS2812B")
      (footprint "eagle-import:WS2812B")
      (libsource (lib "eagle-import") (part "WS2812B"))
    )
    (comp (ref "LED17")
      (value "WS2812B")
      (footprint "eagle-import:WS2812B")
      (libsource (lib "eagle-import") (part "WS2812B"))
    )
    (comp (ref "LED18")
      (value "WS2812B")
      (footprint "eagle-import:WS2812B")
      (libsource (lib "eagle-import") (part "WS2812B"))
    )
    (comp (ref "LED19")
      (value "WS2812B")
      (footprint "eagle-import:WS2812B")
      (libsource (lib "eagle-import") (part "WS2812B"))
    )
    (comp (ref "LED20")
      (value "WS2812B")
      (footprint "eagle-import:WS2812B")
      (libsource (lib "eagle-import") (part "WS2812B"))
    )
    (comp (ref "LED21")
      (value "WS2812B")
      (footprint "eagle-import:WS2812B")
      (libsource (lib "eagle-import") (part "WS2812B"))
    )
    (comp (ref "LED22")
      (value "WS2812B")
      (footprint "eagle-import:WS2812B")
      (libsource (lib "eagle-import") (part "WS2812B"))
    )
    (comp (ref "LED23")
      (value "WS2812B")
      (footprint "eagle-import:WS2812B")
      (libsource (lib "eagle-import") (part "WS2812B"))
    )
    (comp (ref "LED24")
      (value "WS2812B")
      (footprint "eagle-import:WS2812B")
      (libsource (lib "eagle-import") (part "WS2812B"))
    )
    (comp (ref "LED25")
      (value "WS2812B")
      (footprint "eagle-import:WS2812B")
      (libsource (lib "eagle-import") (part "WS2812B"))
    )
    (comp (ref "LED26")
      (value "WS2812B")
      (footprint "eagle-import:WS2812B")
      (libsource (lib "eagle-import") (part "WS2812B"))
    )
    (comp (ref "LED27")
      (value "WS2812B")
      (footprint "eagle-import:WS2812B")
      (libsource (lib "eagle-import") (part "WS2812B"))
    )
    (comp (ref "LED28")
      (value "WS2812B")
      (footprint "eagle-import:WS2812B")
      (libsource (lib "eagle-import") (part "WS2812B"))
    )
    (comp (ref "LED29")
      (value "WS2812B")
      (footprint "eagle-import:WS2812B")
      (libsource (lib "eagle-import") (part "WS2812B"))
    )
    (comp (ref "LED30")
      (value "WS2812B")
      (footprint "eagle-import:WS2812B")
      (libsource (lib "eagle-import") (part "WS2812B"))
    )
    (comp (ref "LED31")
      (value "WS2812B")
      (footprint "eagle-import:WS2812B")
      (libsource (lib "eagle-import") (part "WS2812B"))
    )
    (comp (ref "LED32")
      (value "WS2812B")
      (footprint "eagle-import:WS2812B")
      (libsource (lib "eagle-import") (part "WS2812B"))
    )
    (comp (ref "LED33")
      (value "WS2812B")
      (footprint "eagle-import:WS2812B")
      (libsource (lib "eagle-import") (part "WS2812B"))
    )
    (comp (ref "LED34")
      (value "WS2812B")
      (footprint "eagle-import:WS2812B")
      (libsource (lib "eagle-import") (part "WS2812B"))
    )
    (comp (ref "LED35")
      (value "WS2812B")
      (footprint "eagle-import:WS2812B")
      (libsource (lib "eagle-import") (part "WS2812B"))
    )
    (comp (ref "LED36")
      (value "WS2812B")
      (footprint "eagle-import:WS2812B")
      (libsource (lib "eagle-import") (part "WS2812B"))
    )
    (comp (ref "LED37")
      (value "WS2812B")
      (footprint "eagle-import:WS2812B")
      (libsource (lib "eagle-import") (part "WS2812B"))
    )
    (comp (ref "LED38")
      (value "WS2812B")
      (footprint "eagle-import:WS2812B")
      (libsource (lib "eagle-import") (part "WS2812B"))
    )
    (comp (ref "LED39")
      (value "WS2812B")
      (footprint "eagle-import:WS2812B")
      (libsource (lib "eagle-import") (part "WS2812B"))
    )
    (comp (ref "LED40")
      (value "WS2812B")
      (footprint "eagle-import:WS2812B")
      (libsource (lib "eagle-import") (part "WS2812B"))
    )
    (comp (ref "LED41")
      (value "WS2812B")
      (footprint "eagle-import:WS2812B")
      (libsource (lib "eagle-import") (part "WS2812B"))
    )
    (comp (ref "LED42")
      (value "WS2812B")
      (footprint "eagle-import:WS2812B")
      (libsource (lib "eagle-import") (part "WS2812B"))
    )
    (comp (ref "LED43")
      (value "WS2812B")
      (footprint "eagle-import:WS2812B")
      (libsource (lib "eagle-import") (part "WS2812B"))
    )
    (comp (ref "LED44")
      (value "WS2812B")
      (footprint "eagle-import:WS2812B")
      (libsource (lib "eagle-import") (part "WS2812B"))
    )
    (comp (ref "LED45")
      (value "WS2812B")
      (footprint "eagle-import:WS2812B")
      (libsource (lib "eagle-import") (part "WS2812B"))
    )
    (comp (ref "LED46")
      (value "WS2812B")
      (footprint "eagle-import:WS2812B")
      (libsource (lib "eagle-import") (part "WS2812B"))
    )
    (comp (ref "LED47")
      (value "WS2812B")
      (footprint "eagle-import:WS2812B")
      (libsource (lib "eagle-import") (part "WS2812B"))
    )
    (comp (ref "LED48")
      (value "WS2812B")
      (footprint "eagle-import:WS2812B")
      (libsource (lib "eagle-import") (part "WS2812B"))
    )
    (comp (ref "LED49")
      (value "WS2812B")
      (footprint "eagle-import:WS2812B")
      (libsource (lib "eagle-import") (part "WS2812B"))
    )
    (comp (ref "LED50")
      (value "WS2812B")
      (footprint "eagle-import:WS2812B")
      (libsource (lib "eagle-import") (part "WS2812B"))
    )
    (comp (ref "LED51")
      (value "WS2812B")
      (footprint "eagle-import:WS2812B")
      (libsource (lib "eagle-import") (part "WS2812B"))
    )
    (comp (ref "LED52")
      (value "WS2812B")
      (footprint "eagle-import:WS2812B")
      (libsource (lib "eagle-import") (part "WS2812B"))
    )
    (comp (ref "LED53")
      (value "WS2812B")
      (footprint "eagle-import:WS2812B")
      (libsource (lib "eagle-import") (part "WS2812B"))
    )
    (comp (ref "LED54")
      (value "WS2812B")
      (footprint "eagle-import:WS2812B")
      (libsource (lib "eagle-import") (part "WS2812B"))
    )
    (comp (ref "LED55")
      (value "WS2812B")
      (footprint "eagle-import:WS2812B")
      (libsource (lib "eagle-import") (part "WS2812B"))
    )
    (comp (ref "LED56")
      (value "WS2812B")
      (footprint "eagle-import:WS2812B")
      (libsource (lib "eagle-import") (part "WS2812B"))
    )
    (comp (ref "LED57")
      (value "WS2812B")
      (footprint "eagle-import:WS2812B")
      (libsource (lib "eagle-import") (part "WS2812B"))
    )
    (comp (ref "LED58")
      (value "WS2812B")
      (footprint "eagle-import:WS2812B")
      (libsource (lib "eagle-import") (part "WS2812B"))
    )
    (comp (ref "LED59")
      (value "WS2812B")
      (footprint "eagle-import:WS2812B")
      (libsource (lib "eagle-import") (part "WS2812B"))
    )
    (comp (ref "LED60")
      (value "WS2812B")
      (footprint "eagle-import:WS2812B")
      (libsource (lib "eagle-import") (part "WS2812B"))
    )
    (comp (ref "LED61")
      (value "WS2812B")
      (footprint "eagle-import:WS2812B")
      (libsource (lib "eagle-import") (part "WS2812B"))
    )
    (comp (ref "LED62")
      (value "WS2812B")
      (footprint "eagle-import:WS2812B")
      (libsource (lib "eagle-import") (part "WS2812B"))
    )
    (comp (ref "LED63")
      (value "WS2812B")
      (footprint "eagle-import:WS2812B")
      (libsource (lib "eagle-import") (part "WS2812B"))
    )
    (comp (ref "LED64")
      (value "WS2812B")
      (footprint "eagle-import:WS2812B")
      (libsource (lib "eagle-import") (part "WS2812B"))
    )
    (comp (ref "LED65")
      (value "WS2812B")
      (footprint "eagle-import:WS2812B")
      (libsource (lib "eagle-import") (part "WS2812B"))
    )
    (comp (ref "LED66")
      (value "WS2812B")
      (footprint "eagle-import:WS2812B")
      (libsource (lib "eagle-import") (part "WS2812B"))
    )
    (comp (ref "LED67")
      (value "WS2812B")
      (footprint "eagle-import:WS2812B")
      (libsource (lib "eagle-import") (part "WS2812B"))
    )
    (comp (ref "LED68")
      (value "WS2812B")
      (footprint "eagle-import:WS2812B")
      (libsource (lib "eagle-import") (part "WS2812B"))
    )
    (comp (ref "LED69")
      (value "WS2812B")
      (footprint "eagle-import:WS2812B")
      (libsource (lib "eagle-import") (part "WS2812B"))
    )
    (comp (ref "LED70")
      (value "WS2812B")
      (footprint "eagle-import:WS2812B")
      (libsource (lib "eagle-import") (part "WS2812B"))
    )
    (comp (ref "LED71")
      (value "WS2812B")
      (footprint "eagle-import:WS2812B")
      (libsource (lib "eagle-import") (part "WS2812B"))
    )
    (comp (ref "LED72")
      (value "WS2812B")
      (footprint "eagle-import:WS2812B")
      (libsource (lib "eagle-import") (part "WS2812B"))
    )
    (comp (ref "LED73")
      (value "WS2812B")
      (footprint "eagle-import:WS2812B")
      (libsource (lib "eagle-import") (part "WS2812B"))
    )
    (comp (ref "LED74")
      (value "WS2812B")
      (footprint "eagle-import:WS2812B")
      (libsource (lib "eagle-import") (part "WS2812B"))
    )
    (comp (ref "LED75")
      (value "WS2812B")
      (footprint "eagle-import:WS2812B")
      (libsource (lib "eagle-import") (part "WS2812B"))
    )
    (comp (ref "LED76")
      (value "WS2812B")
      (footprint "eagle-import:WS2812B")
      (libsource (lib "eagle-import") (part "WS2812B"))
    )
    (comp (ref "LED77")
      (value "WS2812B")
      (footprint "eagle-import:WS2812B")
      (libsource (lib "eagle-import") (part "WS2812B"))
    )
    (comp (ref "LED78")
      (value "WS2812B")
      (footprint "eagle-import:WS2812B")
      (libsource (lib "eagle-import") (part "WS2812B"))
    )
    (comp (ref "LED79")
      (value "WS2812B")
      (footprint "eagle-import:WS2812B")
      (libsource (lib "eagle-import") (part "WS2812B"))
    )
    (comp (ref "LED80")
      (value "WS2812B")
      (footprint "eagle-import:WS2812B")
      (libsource (lib "eagle-import") (part "WS2812B"))
    )
    (comp (ref "LED81")
      (value "WS2812B")
      (footprint "eagle-import:WS2812B")
      (libsource (lib "eagle-import") (part "WS2812B"))
    )
    (comp (ref "LED82")
      (value "WS2812B")
      (footprint "eagle-import:WS2812B")
      (libsource (lib "eagle-import") (part "WS2812B"))
    )
    (comp (ref "LED83")
      (value "WS2812B")
      (footprint "eagle-import:WS2812B")
      (libsource (lib "eagle-import") (part "WS2812B"))
    )
    (comp (ref "LED84")
      (value "WS2812B")
      (footprint "eagle-import:WS2812B")
      (libsource (lib "eagle-import") (part "WS2812B"))
    )
    (comp (ref "LED85")
      (value "WS2812B")
      (footprint "eagle-import:WS2812B")
      (libsource (lib "eagle-import") (part "WS2812B"))
    )
    (comp (ref "LED86")
      (value "WS2812B")
      (footprint "eagle-import:WS2812B")
      (libsource (lib "eagle-import") (part "WS2812B"))
    )
    (comp (ref "LED87")
      (value "WS2812B")
      (footprint "eagle-import:WS2812B")
      (libsource (lib "eagle-import") (part "WS2812B"))
    )
    (comp (ref "LED88")
      (value "WS2812B")
      (footprint "eagle-import:WS2812B")
      (libsource (lib "eagle-import") (part "WS2812B"))
    )
    (comp (ref "LED89")
      (value "WS2812B")
      (footprint "eagle-import:WS2812B")
      (libsource (lib "eagle-import") (part "WS2812B"))
    )
    (comp (ref "LED90")
      (value "WS2812B")
      (footprint "eagle-import:WS2812B")
      (libsource (lib "eagle-import") (part "WS2812B"))
    )
    (comp (ref "LED91")
      (value "WS2812B")
      (footprint "eagle-import:WS2812B")
      (libsource (lib "eagle-import") (part "WS2812B"))
    )
    (comp (ref "LED92")
      (value "WS2812B")
      (footprint "eagle-import:WS2812B")
      (libsource (lib "eagle-import") (part "WS2812B"))
    )
    (comp (ref "LED93")
      (value "WS2812B")
      (footprint "eagle-import:WS2812B")
      (libsource (lib "eagle-import") (part "WS2812B"))
    )
    (comp (ref "LED94")
      (value "WS2812B")
      (footprint "eagle-import:WS2812B")
      (libsource (lib "eagle-import") (part "WS2812B"))
    )
    (comp (ref "LED95")
      (value "WS2812B")
      (footprint "eagle-import:WS2812B")
      (libsource (lib "eagle-import") (part "WS2812B"))
    )
    (comp (ref "LED96")
      (value "WS2812B")
      (footprint "eagle-import:WS2812B")
      (libsource (lib "eagle-import") (part "WS2812B"))
    )
    (comp (ref "LED97")
      (value "WS2812B")
      (footprint "eagle-import:WS2812B")
      (libsource (lib "eagle-import") (part "WS2812B"))
    )
    (comp (ref "LED98")
      (value "WS2812B")
      (footprint "eagle-import:WS2812B")
      (libsource (lib "eagle-import") (part "WS2812B"))
    )
    (comp (ref "LED99")
      (value "WS2812B")
      (footprint "eagle-import:WS2812B")
      (libsource (lib "eagle-import") (part "WS2812B"))
    )
    (comp (ref "LED100")
      (value "WS2812B")
      (footprint "eagle-import:WS2812B")
      (libsource (lib "eagle-import") (part "WS2812B"))
    )
    (comp (ref "LED101")
      (value "WS2812B")
      (footprint "eagle-import:WS2812B")
      (libsource (lib "eagle-import") (part "WS2812B"))
    )
    (comp (ref "LED102")
      (value "WS2812B")
      (footprint "eagle-import:WS2812B")
      (libsource (lib "eagle-import") (part "WS2812B"))
    )
    (comp (ref "LED103")
      (value "WS2812B")
      (footprint "eagle-import:WS2812B")
      (libsource (lib "eagle-import") (part "WS2812B"))
    )
    (comp (ref "LED104")
      (value "WS2812B")
      (footprint "eagle-import:WS2812B")
      (libsource (lib "eagle-import") (part "WS2812B"))
    )
    (comp (ref "LED105")
      (value "WS2812B")
      (footprint "eagle-import:WS2812B")
      (libsource (lib "eagle-import") (part "WS2812B"))
    )
    (comp (ref "LED106")
      (value "WS2812B")
      (footprint "eagle-import:WS2812B")
      (libsource (lib "eagle-import") (part "WS2812B"))
    )
    (comp (ref "LED107")
      (value "WS2812B")
      (footprint "eagle-import:WS2812B")
      (libsource (lib "eagle-import") (part "WS2812B"))
    )
    (comp (ref "LED108")
      (value "WS2812B")
      (footprint "eagle-import:WS2812B")
      (libsource (lib "eagle-import") (part "WS2812B"))
    )
    (comp (ref "LED109")
      (value "WS2812B")
      (footprint "eagle-import:WS2812B")
      (libsource (lib "eagle-import") (part "WS2812B"))
    )
    (comp (ref "LED110")
      (value "WS2812B")
      (footprint "eagle-import:WS2812B")
      (libsource (lib "eagle-import") (part "WS2812B"))
    )
    (comp (ref "LED111")
      (value "WS2812B")
      (footprint "eagle-import:WS2812B")
      (libsource (lib "eagle-import") (part "WS2812B"))
    )
    (comp (ref "LED112")
      (value "WS2812B")
      (footprint "eagle-import:WS2812B")
      (libsource (lib "eagle-import") (part "WS2812B"))
    )
    (comp (ref "LED113")
      (value "WS2812B")
      (footprint "eagle-import:WS2812B")
      (libsource (lib "eagle-import") (part "WS2812B"))
    )
    (comp (ref "LED114")
      (value "WS2812B")
      (footprint "eagle-import:WS2812B")
      (libsource (lib "eagle-import") (part "WS2812B"))
    )
    (comp (ref "LED115")
      (value "WS2812B")
      (footprint "eagle-import:WS2812B")
      (libsource (lib "eagle-import") (part "WS2812B"))
    )
    (comp (ref "LED116")
      (value "WS2812B")
      (footprint "eagle-import:WS2812B")
      (libsource (lib "eagle-import") (part "WS2812B"))
    )
    (comp (ref "LED117")
      (value "WS2812B")
      (footprint "eagle-import:WS2812B")
      (libsource (lib "eagle-import") (part "WS2812B"))
    )
    (comp (ref "LED118")
      (value "WS2812B")
      (footprint "eagle-import:WS2812B")
      (libsource (lib "eagle-import") (part "WS2812B"))
    )
    (comp (ref "LED119")
      (value "WS2812B")
      (footprint "eagle-import:WS2812B")
      (libsource (lib "eagle-import") (part "WS2812B"))
    )
    (comp (ref "LED120")
      (value "WS2812B")
      (footprint "eagle-import:WS2812B")
      (libsource (lib "eagle-import") (part "WS2812B"))
    )
    (comp (ref "LED121")
      (value "WS2812B")
      (footprint "eagle-import:WS2812B")
      (libsource (lib "eagle-import") (part "WS2812B"))
    )
    (comp (ref "LED122")
      (value "WS2812B")
      (footprint "eagle-import:WS2812B")
      (libsource (lib "eagle-import") (part "WS2812B"))
    )
    (comp (ref "LED123")
      (value "WS2812B")
      (footprint "eagle-import:WS2812B")
      (libsource (lib "eagle-import") (part "WS2812B"))
    )
    (comp (ref "LED124")
      (value "WS2812B")
      (footprint "eagle-import:WS2812B")
      (libsource (lib "eagle-import") (part "WS2812B"))
    )
    (comp (ref "LED125")
      (value "WS2812B")
      (footprint "eagle-import:WS2812B")
      (libsource (lib "eagle-import") (part "WS2812B"))
    )
    (comp (ref "LED126")
      (value "WS2812B")
      (footprint "eagle-import:WS2812B")
      (libsource (lib "eagle-import") (part "WS2812B"))
    )
    (comp (ref "LED127")
      (value "WS2812B")
      (footprint "eagle-import:WS2812B")
      (libsource (lib "eagle-import") (part "WS2812B"))
    )
    (comp (ref "LED128")
      (value "WS2812B")
      (footprint "eagle-import:WS2812B")
      (libsource (lib "eagle-import") (part "WS2812B"))
    )
    (comp (ref "LED129")
      (value "WS2812B")
      (footprint "eagle-import:WS2812B")
      (libsource (lib "eagle-import") (part "WS2812B"))
    )
    (comp (ref "LED130")
      (value "WS2812B")
      (footprint "eagle-import:WS2812B")
      (libsource (lib "eagle-import") (part "WS2812B"))
    )
    (comp (ref "LED131")
      (value "WS2812B")
      (footprint "eagle-import:WS2812B")
      (libsource (lib "eagle-import") (part "WS2812B"))
    )
    (comp (ref "LED132")
      (value "WS2812B")
      (footprint "eagle-import:WS2812B")
      (libsource (lib "eagle-import") (part "WS2812B"))
    )
    (comp (ref "LED133")
      (value "WS2812B")
      (footprint "eagle-import:WS2812B")
      (libsource (lib "eagle-import") (part "WS2812B"))
    )
    (comp (ref "LED134")
      (value "WS2812B")
      (footprint "eagle-import:WS2812B")
      (libsource (lib "eagle-import") (part "WS2812B"))
    )
    (comp (ref "LED135")
      (value "WS2812B")
      (footprint "eagle-import:WS2812B")
      (libsource (lib "eagle-import") (part "WS2812B"))
    )
    (comp (ref "LED136")
      (value "WS2812B")
      (footprint "eagle-import:WS2812B")
      (libsource (lib "eagle-import") (part "WS2812B"))
    )
    (comp (ref "LED137")
      (value "WS2812B")
      (footprint "eagle-import:WS2812B")
      (libsource (lib "eagle-import") (part "WS2812B"))
    )
    (comp (ref "LED138")
      (value "WS2812B")
      (footprint "eagle-import:WS2812B")
      (libsource (lib "eagle-import") (part "WS2812B"))
    )
    (comp (ref "LED139")
      (value "WS2812B")
      (footprint "eagle-import:WS2812B")
      (libsource (lib "eagle-import") (part "WS2812B"))
    )
    (comp (ref "LED140")
      (value "WS2812B")
      (footprint "eagle-import:WS2812B")
      (libsource (lib "eagle-import") (part "WS2812B"))
    )
    (comp (ref "LED141")
      (value "WS2812B")
      (footprint "eagle-import:WS2812B")
      (libsource (lib "eagle-import") (part "WS2812B"))
    )
    (comp (ref "LED142")
      (value "WS2812B")
      (footprint "eagle-import:WS2812B")
      (libsource (lib "eagle-import") (part "WS2812B"))
    )
    (comp (ref "LED143")
      (value "WS2812B")
      (footprint "eagle-import:WS2812B")
      (libsource (lib "eagle-import") (part "WS2812B"))
    )
    (comp (ref "LED144")
      (value "WS2812B")
      (footprint "eagle-import:WS2812B")
      (libsource (lib "eagle-import") (part "WS2812B"))
    )
    (comp (ref "LED145")
      (value "WS2812B")
      (footprint "eagle-import:WS2812B")
      (libsource (lib "eagle-import") (part "WS2812B"))
    )
    (comp (ref "LED146")
      (value "WS2812B")
      (footprint "eagle-import:WS2812B")
      (libsource (lib "eagle-import") (part "WS2812B"))
    )
    (comp (ref "LED147")
      (value "WS2812B")
      (footprint "eagle-import:WS2812B")
      (libsource (lib "eagle-import") (part "WS2812B"))
    )
    (comp (ref "LED148")
      (value "WS2812B")
      (footprint "eagle-import:WS2812B")
      (libsource (lib "eagle-import") (part "WS2812B"))
    )
    (comp (ref "LED149")
      (value "WS2812B")
      (footprint "eagle-import:WS2812B")
      (libsource (lib "eagle-import") (part "WS2812B"))
    )
    (comp (ref "LED150")
      (value "WS2812B")
      (footprint "eagle-import:WS2812B")
      (libsource (lib "eagle-import") (part "WS2812B"))
    )
    (comp (ref "LED151")
      (value "WS2812B")
      (footprint "eagle-import:WS2812B")
      (libsource (lib "eagle-import") (part "WS2812B"))
    )
    (comp (ref "LED152")
      (value "WS2812B")
      (footprint "eagle-import:WS2812B")
      (libsource (lib "eagle-import") (part "WS2812B"))
    )
    (comp (ref "LED153")
      (value "WS2812B")
      (footprint "eagle-import:WS2812B")
      (libsource (lib "eagle-import") (part "WS2812B"))
    )
    (comp (ref "LED154")
      (value "WS2812B")
      (footprint "eagle-import:WS2812B")
      (libsource (lib "eagle-import") (part "WS2812B"))
    )
    (comp (ref "LED155")
      (value "WS2812B")
      (footprint "eagle-import:WS2812B")
      (libsource (lib "eagle-import") (part "WS2812B"))
    )
    (comp (ref "LED156")
      (value "WS2812B")
      (footprint "eagle-import:WS2812B")
      (libsource (lib "eagle-import") (part "WS2812B"))
    )
    (comp (ref "LED157")
      (value "WS2812B")
      (footprint "eagle-import:WS2812B")
      (libsource (lib "eagle-import") (part "WS2812B"))
    )
    (comp (ref "LED158")
      (value "WS2812B")
      (footprint "eagle-import:WS2812B")
      (libsource (lib "eagle-import") (part "WS2812B"))
    )
    (comp (ref "LED159")
      (value "WS2812B")
      (footprint "eagle-import:WS2812B")
      (libsource (lib "eagle-import") (part "WS2812B"))
    )
    (comp (ref "LED160")
      (value "WS2812B")
      (footprint "eagle-import:WS2812B")
      (libsource (lib "eagle-import") (part "WS2812B"))
    )
    (comp (ref "LED161")
      (value "WS2812B")
      (footprint "eagle-import:WS2812B")
      (libsource (lib "eagle-import") (part "WS2812B"))
    )
    (comp (ref "LED162")
      (value "WS2812B")
      (footprint "eagle-import:WS2812B")
      (libsource (lib "eagle-import") (part "WS2812B"))
    )
    (comp (ref "LED163")
      (value "WS2812B")
      (footprint "eagle-import:WS2812B")
      (libsource (lib "eagle-import") (part "WS2812B"))
    )
    (comp (ref "LED164")
      (value "WS2812B")
      (footprint "eagle-import:WS2812B")
      (libsource (lib "eagle-import") (part "WS2812B"))
    )
    (comp (ref "LED165")
      (value "WS2812B")
      (footprint "eagle-import:WS2812B")
      (libsource (lib "eagle-import") (part "WS2812B"))
    )
    (comp (ref "LED166")
      (value "WS2812B")
      (footprint "eagle-import:WS2812B")
      (libsource (lib "eagle-import") (part "WS2812B"))
    )
    (comp (ref "LED167")
      (value "WS2812B")
      (footprint "eagle-import:WS2812B")
      (libsource (lib "eagle-import") (part "WS2812B"))
    )
    (comp (ref "LED168")
      (value "WS2812B")
      (footprint "eagle-import:WS2812B")
      (libsource (lib "eagle-import") (part "WS2812B"))
    )
    (comp (ref "LED169")
      (value "WS2812B")
      (footprint "eagle-import:WS2812B")
      (libsource (lib "eagle-import") (part "WS2812B"))
    )
    (comp (ref "LED170")
      (value "WS2812B")
      (footprint "eagle-import:WS2812B")
      (libsource (lib "eagle-import") (part "WS2812B"))
    )
    (comp (ref "LED171")
      (value "WS2812B")
      (footprint "eagle-import:WS2812B")
      (libsource (lib "eagle-import") (part "WS2812B"))
    )
    (comp (ref "LED172")
      (value "WS2812B")
      (footprint "eagle-import:WS2812B")
      (libsource (lib "eagle-import") (part "WS2812B"))
    )
    (comp (ref "LED173")
      (value "WS2812B")
      (footprint "eagle-import:WS2812B")
      (libsource (lib "eagle-import") (part "WS2812B"))
    )
    (comp (ref "LED174")
      (value "WS2812B")
      (footprint "eagle-import:WS2812B")
      (libsource (lib "eagle-import") (part "WS2812B"))
    )
    (comp (ref "LED175")
      (value "WS2812B")
      (footprint "eagle-import:WS2812B")
      (libsource (lib "eagle-import") (part "WS2812B"))
    )
    (comp (ref "LED176")
      (value "WS2812B")
      (footprint "eagle-import:WS2812B")
      (libsource (lib "eagle-import") (part "WS2812B"))
    )
    (comp (ref "LED177")
      (value "WS2812B")
      (footprint "eagle-import:WS2812B")
      (libsource (lib "eagle-import") (part "WS2812B"))
    )
    (comp (ref "LED178")
      (value "WS2812B")
      (footprint "eagle-import:WS2812B")
      (libsource (lib "eagle-import") (part "WS2812B"))
    )
    (comp (ref "LED179")
      (value "WS2812B")
      (footprint "eagle-import:WS2812B")
      (libsource (lib "eagle-import") (part "WS2812B"))
    )
    (comp (ref "LED180")
      (value "WS2812B")
      (footprint "eagle-import:WS2812B")
      (libsource (lib "eagle-import") (part "WS2812B"))
    )
    (comp (ref "LED181")
      (value "WS2812B")
      (footprint "eagle-import:WS2812B")
      (libsource (lib "eagle-import") (part "WS2812B"))
    )
    (comp (ref "LED182")
      (value "WS2812B")
      (footprint "eagle-import:WS2812B")
      (libsource (lib "eagle-import") (part "WS2812B"))
    )
    (comp (ref "LED183")
      (value "WS2812B")
      (footprint "eagle-import:WS2812B")
      (libsource (lib "eagle-import") (part "WS2812B"))
    )
    (comp (ref "LED184")
      (value "WS2812B")
      (footprint "eagle-import:WS2812B")
      (libsource (lib "eagle-import") (part "WS2812B"))
    )
    (comp (ref "LED185")
      (value "WS2812B")
      (footprint "eagle-import:WS2812B")
      (libsource (lib "eagle-import") (part "WS2812B"))
    )
    (comp (ref "LED186")
      (value "WS2812B")
      (footprint "eagle-import:WS2812B")
      (libsource (lib "eagle-import") (part "WS2812B"))
    )
    (comp (ref "LED187")
      (value "WS2812B")
      (footprint "eagle-import:WS2812B")
      (libsource (lib "eagle-import") (part "WS2812B"))
    )
    (comp (ref "LED188")
      (value "WS2812B")
      (footprint "eagle-import:WS2812B")
      (libsource (lib "eagle-import") (part "WS2812B"))
    )
    (comp (ref "LED189")
      (value "WS2812B")
      (footprint "eagle-import:WS2812B")
      (libsource (lib "eagle-import") (part "WS2812B"))
    )
    (comp (ref "LED190")
      (value "WS2812B")
      (footprint "eagle-import:WS2812B")
      (libsource (lib "eagle-import") (part "WS2812B"))
    )
    (comp (ref "LED191")
      (value "WS2812B")
      (footprint "eagle-import:WS2812B")
      (libsource (lib "eagle-import") (part "WS2812B"))
    )
    (comp (ref "LED192")
      (value "WS2812B")
      (footprint "eagle-import:WS2812B")
      (libsource (lib "eagle-import") (part "WS2812B"))
    )
    (comp (ref "LOGO7")
      (value "OSHW-LOGOM")
      (footprint "eagle-import:OSHW-LOGO-M")
      (libsource (lib "eagle-import") (part "OSHW-LOGOM"))
    )
    (comp (ref "PAD1")
      (value "SMD2")
      (footprint "eagle-import:SMD1,27-2,54")
      (libsource (lib "eagle-import") (part "SMD2"))
    )
    (comp (ref "PAD2")
      (value "SMD2")
      (footprint "eagle-import:SMD1,27-2,54")
      (libsource (lib "eagle-import") (part "SMD2"))
    )
    (comp (ref "PAD3")
      (value "SMD2")
      (footprint "eagle-import:SMD1,27-2,54")
      (libsource (lib "eagle-import") (part "SMD2"))
    )
    (comp (ref "PAD4")
      (value "SMD2")
      (footprint "eagle-import:SMD1,27-2,54")
      (libsource (lib "eagle-import") (part "SMD2"))
    )
    (comp (ref "PAD5")
      (value "SMD2")
      (footprint "eagle-import:SMD1,27-2,54")
      (libsource (lib "eagle-import") (part "SMD2"))
    )
    (comp (ref "PAD6")
      (value "SMD2")
      (footprint "eagle-import:SMD1,27-2,54")
      (libsource (lib "eagle-import") (part "SMD2"))
    )
    (comp (ref "PAD7")
      (value "SMD2")
      (footprint "eagle-import:SMD1,27-2,54")
      (libsource (lib "eagle-import") (part "SMD2"))
    )
    (comp (ref "PAD8")
      (value "SMD2")
      (footprint "eagle-import:SMD1,27-2,54")
      (libsource (lib "eagle-import") (part "SMD2"))
    )
    (comp (ref "PAD9")
      (value "SMD2")
      (footprint "eagle-import:SMD1,27-2,54")
      (libsource (lib "eagle-import") (part "SMD2"))
    )
    (comp (ref "PAD10")
      (value "SMD2")
      (footprint "eagle-import:SMD1,27-2,54")
      (libsource (lib "eagle-import") (part "SMD2"))
    )
    (comp (ref "PAD11")
      (value "SMD2")
      (footprint "eagle-import:SMD1,27-2,54")
      (libsource (lib "eagle-import") (part "SMD2"))
    )
    (comp (ref "PAD12")
      (value "SMD2")
      (footprint "eagle-import:SMD1,27-2,54")
      (libsource (lib "eagle-import") (part "SMD2"))
    )
    (comp (ref "PAD13")
      (value "SMD2")
      (footprint "eagle-import:SMD1,27-2,54")
      (libsource (lib "eagle-import") (part "SMD2"))
    )
    (comp (ref "PAD14")
      (value "SMD2")
      (footprint "eagle-import:SMD1,27-2,54")
      (libsource (lib "eagle-import") (part "SMD2"))
    )
    (comp (ref "PAD15")
      (value "SMD2")
      (footprint "eagle-import:SMD1,27-2,54")
      (libsource (lib "eagle-import") (part "SMD2"))
    )
    (comp (ref "PAD16")
      (value "SMD2")
      (footprint "eagle-import:SMD1,27-2,54")
      (libsource (lib "eagle-import") (part "SMD2"))
    )
    (comp (ref "PAD17")
      (value "SMD2")
      (footprint "eagle-import:SMD1,27-2,54")
      (libsource (lib "eagle-import") (part "SMD2"))
    )
    (comp (ref "PAD18")
      (value "SMD2")
      (footprint "eagle-import:SMD1,27-2,54")
      (libsource (lib "eagle-import") (part "SMD2"))
    )
    (comp (ref "PAD19")
      (value "SMD2")
      (footprint "eagle-import:SMD1,27-2,54")
      (libsource (lib "eagle-import") (part "SMD2"))
    )
    (comp (ref "PAD20")
      (value "SMD2")
      (footprint "eagle-import:SMD1,27-2,54")
      (libsource (lib "eagle-import") (part "SMD2"))
    )
    (comp (ref "PAD21")
      (value "SMD2")
      (footprint "eagle-import:SMD1,27-2,54")
      (libsource (lib "eagle-import") (part "SMD2"))
    )
    (comp (ref "PAD22")
      (value "SMD2")
      (footprint "eagle-import:SMD1,27-2,54")
      (libsource (lib "eagle-import") (part "SMD2"))
    )
    (comp (ref "PAD23")
      (value "SMD2")
      (footprint "eagle-import:SMD1,27-2,54")
      (libsource (lib "eagle-import") (part "SMD2"))
    )
    (comp (ref "PAD24")
      (value "SMD2")
      (footprint "eagle-import:SMD1,27-2,54")
      (libsource (lib "eagle-import") (part "SMD2"))
    )
    (comp (ref "PAD25")
      (value "SMD2")
      (footprint "eagle-import:SMD1,27-2,54")
      (libsource (lib "eagle-import") (part "SMD2"))
    )
    (comp (ref "PAD26")
      (value "SMD2")
      (footprint "eagle-import:SMD1,27-2,54")
      (libsource (lib "eagle-import") (part "SMD2"))
    )
    (comp (ref "PAD27")
      (value "SMD2")
      (footprint "eagle-import:SMD1,27-2,54")
      (libsource (lib "eagle-import") (part "SMD2"))
    )
    (comp (ref "PAD28")
      (value "SMD2")
      (footprint "eagle-import:SMD1,27-2,54")
      (libsource (lib "eagle-import") (part "SMD2"))
    )
    (comp (ref "TP1")
      (value "TPB1,27")
      (footprint "eagle-import:B1,27")
      (libsource (lib "eagle-import") (part "TPB1,27"))
    )
    (comp (ref "TP2")
      (value "TPB1,27")
      (footprint "eagle-import:B1,27")
      (libsource (lib "eagle-import") (part "TPB1,27"))
    )
    (comp (ref "TP3")
      (value "TPB1,27")
      (footprint "eagle-import:B1,27")
      (libsource (lib "eagle-import") (part "TPB1,27"))
    )
    (comp (ref "TP4")
      (value "TPB1,27")
      (footprint "eagle-import:B1,27")
      (libsource (lib "eagle-import") (part "TPB1,27"))
    )
  )
  (nets
    (net (code "1") (name "+5V") (class "Default")
      (node (ref "C1") (pin "1") (pinfunction "1_1") (pintype "passive"))
      (node (ref "C10") (pin "1") (pinfunction "1_1") (pintype "passive"))
      (node (ref "C100") (pin "1") (pinfunction "1_1") (pintype "passive"))
      (node (ref "C101") (pin "1") (pinfunction "1_1") (pintype "passive"))
      (node (ref "C102") (pin "1") (pinfunction "1_1") (pintype "passive"))
      (node (ref "C103") (pin "1") (pinfunction "1_1") (pintype "passive"))
      (node (ref "C104") (pin "1") (pinfunction "1_1") (pintype "passive"))
      (node (ref "C105") (pin "1") (pinfunction "1_1") (pintype "passive"))
      (node (ref "C106") (pin "1") (pinfunction "1_1") (pintype "passive"))
      (node (ref "C107") (pin "1") (pinfunction "1_1") (pintype "passive"))
      (node (ref "C108") (pin "1") (pinfunction "1_1") (pintype "passive"))
      (node (ref "C109") (pin "1") (pinfunction "1_1") (pintype "passive"))
      (node (ref "C11") (pin "1") (pinfunction "1_1") (pintype "passive"))
      (node (ref "C110") (pin "1") (pinfunction "1_1") (pintype "passive"))
      (node (ref "C111") (pin "1") (pinfunction "1_1") (pintype "passive"))
      (node (ref "C112") (pin "1") (pinfunction "1_1") (pintype "passive"))
      (node (ref "C113") (pin "1") (pinfunction "1_1") (pintype "passive"))
      (node (ref "C114") (pin "1") (pinfunction "1_1") (pintype "passive"))
      (node (ref "C115") (pin "1") (pinfunction "1_1") (pintype "passive"))
      (node (ref "C116") (pin "1") (pinfunction "1_1") (pintype "passive"))
      (node (ref "C117") (pin "1") (pinfunction "1_1") (pintype "passive"))
      (node (ref "C118") (pin "1") (pinfunction "1_1") (pintype "passive"))
      (node (ref "C119") (pin "1") (pinfunction "1_1") (pintype "passive"))
      (node (ref "C12") (pin "1") (pinfunction "1_1") (pintype "passive"))
      (node (ref "C120") (pin "1") (pinfunction "1_1") (pintype "passive"))
      (node (ref "C121") (pin "1") (pinfunction "1_1") (pintype "passive"))
      (node (ref "C122") (pin "1") (pinfunction "1_1") (pintype "passive"))
      (node (ref "C123") (pin "1") (pinfunction "1_1") (pintype "passive"))
      (node (ref "C124") (pin "1") (pinfunction "1_1") (pintype "passive"))
      (node (ref "C125") (pin "1") (pinfunction "1_1") (pintype "passive"))
      (node (ref "C126") (pin "1") (pinfunction "1_1") (pintype "passive"))
      (node (ref "C127") (pin "1") (pinfunction "1_1") (pintype "passive"))
      (node (ref "C128") (pin "1") (pinfunction "1_1") (pintype "passive"))
      (node (ref "C129") (pin "1") (pinfunction "1_1") (pintype "passive"))
      (node (ref "C13") (pin "1") (pinfunction "1_1") (pintype "passive"))
      (node (ref "C130") (pin "1") (pinfunction "1_1") (pintype "passive"))
      (node (ref "C131") (pin "1") (pinfunction "1_1") (pintype "passive"))
      (node (ref "C132") (pin "1") (pinfunction "1_1") (pintype "passive"))
      (node (ref "C133") (pin "1") (pinfunction "1_1") (pintype "passive"))
      (node (ref "C134") (pin "1") (pinfunction "1_1") (pintype "passive"))
      (node (ref "C135") (pin "1") (pinfunction "1_1") (pintype "passive"))
      (node (ref "C136") (pin "1") (pinfunction "1_1") (pintype "passive"))
      (node (ref "C137") (pin "1") (pinfunction "1_1") (pintype "passive"))
      (node (ref "C138") (pin "1") (pinfunction "1_1") (pintype "passive"))
      (node (ref "C139") (pin "1") (pinfunction "1_1") (pintype "passive"))
      (node (ref "C14") (pin "1") (pinfunction "1_1") (pintype "passive"))
      (node (ref "C140") (pin "1") (pinfunction "1_1") (pintype "passive"))
      (node (ref "C141") (pin "1") (pinfunction "1_1") (pintype "passive"))
      (node (ref "C142") (pin "1") (pinfunction "1_1") (pintype "passive"))
      (node (ref "C143") (pin "1") (pinfunction "1_1") (pintype "passive"))
      (node (ref "C144") (pin "1") (pinfunction "1_1") (pintype "passive"))
      (node (ref "C145") (pin "1") (pinfunction "1_1") (pintype "passive"))
      (node (ref "C146") (pin "1") (pinfunction "1_1") (pintype "passive"))
      (node (ref "C147") (pin "1") (pinfunction "1_1") (pintype "passive"))
      (node (ref "C148") (pin "1") (pinfunction "1_1") (pintype "passive"))
      (node (ref "C149") (pin "1") (pinfunction "1_1") (pintype "passive"))
      (node (ref "C15") (pin "1") (pinfunction "1_1") (pintype "passive"))
      (node (ref "C150") (pin "1") (pinfunction "1_1") (pintype "passive"))
      (node (ref "C151") (pin "1") (pinfunction "1_1") (pintype "passive"))
      (node (ref "C152") (pin "1") (pinfunction "1_1") (pintype "passive"))
      (node (ref "C153") (pin "1") (pinfunction "1_1") (pintype "passive"))
      (node (ref "C154") (pin "1") (pinfunction "1_1") (pintype "passive"))
      (node (ref "C155") (pin "1") (pinfunction "1_1") (pintype "passive"))
      (node (ref "C156") (pin "1") (pinfunction "1_1") (pintype "passive"))
      (node (ref "C157") (pin "1") (pinfunction "1_1") (pintype "passive"))
      (node (ref "C158") (pin "1") (pinfunction "1_1") (pintype "passive"))
      (node (ref "C159") (pin "1") (pinfunction "1_1") (pintype "passive"))
      (node (ref "C16") (pin "1") (pinfunction "1_1") (pintype "passive"))
      (node (ref "C160") (pin "1") (pinfunction "1_1") (pintype "passive"))
      (node (ref "C161") (pin "1") (pinfunction "1_1") (pintype "passive"))
      (node (ref "C162") (pin "1") (pinfunction "1_1") (pintype "passive"))
      (node (ref "C163") (pin "1") (pinfunction "1_1") (pintype "passive"))
      (node (ref "C164") (pin "1") (pinfunction "1_1") (pintype "passive"))
      (node (ref "C165") (pin "1") (pinfunction "1_1") (pintype "passive"))
      (node (ref "C166") (pin "1") (pinfunction "1_1") (pintype "passive"))
      (node (ref "C167") (pin "1") (pinfunction "1_1") (pintype "passive"))
      (node (ref "C168") (pin "1") (pinfunction "1_1") (pintype "passive"))
      (node (ref "C169") (pin "1") (pinfunction "1_1") (pintype "passive"))
      (node (ref "C17") (pin "1") (pinfunction "1_1") (pintype "passive"))
      (node (ref "C170") (pin "1") (pinfunction "1_1") (pintype "passive"))
      (node (ref "C171") (pin "1") (pinfunction "1_1") (pintype "passive"))
      (node (ref "C172") (pin "1") (pinfunction "1_1") (pintype "passive"))
      (node (ref "C173") (pin "1") (pinfunction "1_1") (pintype "passive"))
      (node (ref "C174") (pin "1") (pinfunction "1_1") (pintype "passive"))
      (node (ref "C175") (pin "1") (pinfunction "1_1") (pintype "passive"))
      (node (ref "C176") (pin "1") (pinfunction "1_1") (pintype "passive"))
      (node (ref "C177") (pin "1") (pinfunction "1_1") (pintype "passive"))
      (node (ref "C178") (pin "1") (pinfunction "1_1") (pintype "passive"))
      (node (ref "C179") (pin "1") (pinfunction "1_1") (pintype "passive"))
      (node (ref "C18") (pin "1") (pinfunction "1_1") (pintype "passive"))
      (node (ref "C180") (pin "1") (pinfunction "1_1") (pintype "passive"))
      (node (ref "C181") (pin "1") (pinfunction "1_1") (pintype "passive"))
      (node (ref "C182") (pin "1") (pinfunction "1_1") (pintype "passive"))
      (node (ref "C183") (pin "1") (pinfunction "1_1") (pintype "passive"))
      (node (ref "C184") (pin "1") (pinfunction "1_1") (pintype "passive"))
      (node (ref "C185") (pin "1") (pinfunction "1_1") (pintype "passive"))
      (node (ref "C186") (pin "1") (pinfunction "1_1") (pintype "passive"))
      (node (ref "C187") (pin "1") (pinfunction "1_1") (pintype "passive"))
      (node (ref "C188") (pin "1") (pinfunction "1_1") (pintype "passive"))
      (node (ref "C189") (pin "1") (pinfunction "1_1") (pintype "passive"))
      (node (ref "C19") (pin "1") (pinfunction "1_1") (pintype "passive"))
      (node (ref "C190") (pin "1") (pinfunction "1_1") (pintype "passive"))
      (node (ref "C191") (pin "1") (pinfunction "1_1") (pintype "passive"))
      (node (ref "C192") (pin "1") (pinfunction "1_1") (pintype "passive"))
      (node (ref "C2") (pin "1") (pinfunction "1_1") (pintype "passive"))
      (node (ref "C20") (pin "1") (pinfunction "1_1") (pintype "passive"))
      (node (ref "C21") (pin "1") (pinfunction "1_1") (pintype "passive"))
      (node (ref "C22") (pin "1") (pinfunction "1_1") (pintype "passive"))
      (node (ref "C23") (pin "1") (pinfunction "1_1") (pintype "passive"))
      (node (ref "C24") (pin "1") (pinfunction "1_1") (pintype "passive"))
      (node (ref "C25") (pin "1") (pinfunction "1_1") (pintype "passive"))
      (node (ref "C26") (pin "1") (pinfunction "1_1") (pintype "passive"))
      (node (ref "C27") (pin "1") (pinfunction "1_1") (pintype "passive"))
      (node (ref "C28") (pin "1") (pinfunction "1_1") (pintype "passive"))
      (node (ref "C29") (pin "1") (pinfunction "1_1") (pintype "passive"))
      (node (ref "C3") (pin "1") (pinfunction "1_1") (pintype "passive"))
      (node (ref "C30") (pin "1") (pinfunction "1_1") (pintype "passive"))
      (node (ref "C31") (pin "1") (pinfunction "1_1") (pintype "passive"))
      (node (ref "C32") (pin "1") (pinfunction "1_1") (pintype "passive"))
      (node (ref "C33") (pin "1") (pinfunction "1_1") (pintype "passive"))
      (node (ref "C34") (pin "1") (pinfunction "1_1") (pintype "passive"))
      (node (ref "C35") (pin "1") (pinfunction "1_1") (pintype "passive"))
      (node (ref "C36") (pin "1") (pinfunction "1_1") (pintype "passive"))
      (node (ref "C37") (pin "1") (pinfunction "1_1") (pintype "passive"))
      (node (ref "C38") (pin "1") (pinfunction "1_1") (pintype "passive"))
      (node (ref "C39") (pin "1") (pinfunction "1_1") (pintype "passive"))
      (node (ref "C4") (pin "1") (pinfunction "1_1") (pintype "passive"))
      (node (ref "C40") (pin "1") (pinfunction "1_1") (pintype "passive"))
      (node (ref "C41") (pin "1") (pinfunction "1_1") (pintype "passive"))
      (node (ref "C42") (pin "1") (pinfunction "1_1") (pintype "passive"))
      (node (ref "C43") (pin "1") (pinfunction "1_1") (pintype "passive"))
      (node (ref "C44") (pin "1") (pinfunction "1_1") (pintype "passive"))
      (node (ref "C45") (pin "1") (pinfunction "1_1") (pintype "passive"))
      (node (ref "C46") (pin "1") (pinfunction "1_1") (pintype "passive"))
      (node (ref "C47") (pin "1") (pinfunction "1_1") (pintype "passive"))
      (node (ref "C48") (pin "1") (pinfunction "1_1") (pintype "passive"))
      (node (ref "C49") (pin "1") (pinfunction "1_1") (pintype "passive"))
      (node (ref "C5") (pin "1") (pinfunction "1_1") (pintype "passive"))
      (node (ref "C50") (pin "1") (pinfunction "1_1") (pintype "passive"))
      (node (ref "C51") (pin "1") (pinfunction "1_1") (pintype "passive"))
      (node (ref "C52") (pin "1") (pinfunction "1_1") (pintype "passive"))
      (node (ref "C53") (pin "1") (pinfunction "1_1") (pintype "passive"))
      (node (ref "C54") (pin "1") (pinfunction "1_1") (pintype "passive"))
      (node (ref "C55") (pin "1") (pinfunction "1_1") (pintype "passive"))
      (node (ref "C56") (pin "1") (pinfunction "1_1") (pintype "passive"))
      (node (ref "C57") (pin "1") (pinfunction "1_1") (pintype "passive"))
      (node (ref "C58") (pin "1") (pinfunction "1_1") (pintype "passive"))
      (node (ref "C59") (pin "1") (pinfunction "1_1") (pintype "passive"))
      (node (ref "C6") (pin "1") (pinfunction "1_1") (pintype "passive"))
      (node (ref "C60") (pin "1") (pinfunction "1_1") (pintype "passive"))
      (node (ref "C61") (pin "1") (pinfunction "1_1") (pintype "passive"))
      (node (ref "C62") (pin "1") (pinfunction "1_1") (pintype "passive"))
      (node (ref "C63") (pin "1") (pinfunction "1_1") (pintype "passive"))
      (node (ref "C64") (pin "1") (pinfunction "1_1") (pintype "passive"))
      (node (ref "C65") (pin "1") (pinfunction "1_1") (pintype "passive"))
      (node (ref "C66") (pin "1") (pinfunction "1_1") (pintype "passive"))
      (node (ref "C67") (pin "1") (pinfunction "1_1") (pintype "passive"))
      (node (ref "C68") (pin "1") (pinfunction "1_1") (pintype "passive"))
      (node (ref "C69") (pin "1") (pinfunction "1_1") (pintype "passive"))
      (node (ref "C7") (pin "1") (pinfunction "1_1") (pintype "passive"))
      (node (ref "C70") (pin "1") (pinfunction "1_1") (pintype "passive"))
      (node (ref "C71") (pin "1") (pinfunction "1_1") (pintype "passive"))
      (node (ref "C72") (pin "1") (pinfunction "1_1") (pintype "passive"))
      (node (ref "C73") (pin "1") (pinfunction "1_1") (pintype "passive"))
      (node (ref "C74") (pin "1") (pinfunction "1_1") (pintype "passive"))
      (node (ref "C75") (pin "1") (pinfunction "1_1") (pintype "passive"))
      (node (ref "C76") (pin "1") (pinfunction "1_1") (pintype "passive"))
      (node (ref "C77") (pin "1") (pinfunction "1_1") (pintype "passive"))
      (node (ref "C78") (pin "1") (pinfunction "1_1") (pintype "passive"))
      (node (ref "C79") (pin "1") (pinfunction "1_1") (pintype "passive"))
      (node (ref "C8") (pin "1") (pinfunction "1_1") (pintype "passive"))
      (node (ref "C80") (pin "1") (pinfunction "1_1") (pintype "passive"))
      (node (ref "C81") (pin "1") (pinfunction "1_1") (pintype "passive"))
      (node (ref "C82") (pin "1") (pinfunction "1_1") (pintype "passive"))
      (node (ref "C83") (pin "1") (pinfunction "1_1") (pintype "passive"))
      (node (ref "C84") (pin "1") (pinfunction "1_1") (pintype "passive"))
      (node (ref "C85") (pin "1") (pinfunction "1_1") (pintype "passive"))
      (node (ref "C86") (pin "1") (pinfunction "1_1") (pintype "passive"))
      (node (ref "C87") (pin "1") (pinfunction "1_1") (pintype "passive"))
      (node (ref "C88") (pin "1") (pinfunction "1_1") (pintype "passive"))
      (node (ref "C89") (pin "1") (pinfunction "1_1") (pintype "passive"))
      (node (ref "C9") (pin "1") (pinfunction "1_1") (pintype "passive"))
      (node (ref "C90") (pin "1") (pinfunction "1_1") (pintype "passive"))
      (node (ref "C91") (pin "1") (pinfunction "1_1") (pintype "passive"))
      (node (ref "C92") (pin "1") (pinfunction "1_1") (pintype "passive"))
      (node (ref "C93") (pin "1") (pinfunction "1_1") (pintype "passive"))
      (node (ref "C94") (pin "1") (pinfunction "1_1") (pintype "passive"))
      (node (ref "C95") (pin "1") (pinfunction "1_1") (pintype "passive"))
      (node (ref "C96") (pin "1") (pinfunction "1_1") (pintype "passive"))
      (node (ref "C97") (pin "1") (pinfunction "1_1") (pintype "passive"))
      (node (ref "C98") (pin "1") (pinfunction "1_1") (pintype "passive"))
      (node (ref "C99") (pin "1") (pinfunction "1_1") (pintype "passive"))
      (node (ref "LED1") (pin "1") (pinfunction "VDD_1") (pintype "bidirectional"))
      (node (ref "LED10") (pin "1") (pinfunction "VDD_1") (pintype "bidirectional"))
      (node (ref "LED100") (pin "1") (pinfunction "VDD_1") (pintype "bidirectional"))
      (node (ref "LED101") (pin "1") (pinfunction "VDD_1") (pintype "bidirectional"))
      (node (ref "LED102") (pin "1") (pinfunction "VDD_1") (pintype "bidirectional"))
      (node (ref "LED103") (pin "1") (pinfunction "VDD_1") (pintype "bidirectional"))
      (node (ref "LED104") (pin "1") (pinfunction "VDD_1") (pintype "bidirectional"))
      (node (ref "LED105") (pin "1") (pinfunction "VDD_1") (pintype "bidirectional"))
      (node (ref "LED106") (pin "1") (pinfunction "VDD_1") (pintype "bidirectional"))
      (node (ref "LED107") (pin "1") (pinfunction "VDD_1") (pintype "bidirectional"))
      (node (ref "LED108") (pin "1") (pinfunction "VDD_1") (pintype "bidirectional"))
      (node (ref "LED109") (pin "1") (pinfunction "VDD_1") (pintype "bidirectional"))
      (node (ref "LED11") (pin "1") (pinfunction "VDD_1") (pintype "bidirectional"))
      (node (ref "LED110") (pin "1") (pinfunction "VDD_1") (pintype "bidirectional"))
      (node (ref "LED111") (pin "1") (pinfunction "VDD_1") (pintype "bidirectional"))
      (node (ref "LED112") (pin "1") (pinfunction "VDD_1") (pintype "bidirectional"))
      (node (ref "LED113") (pin "1") (pinfunction "VDD_1") (pintype "bidirectional"))
      (node (ref "LED114") (pin "1") (pinfunction "VDD_1") (pintype "bidirectional"))
      (node (ref "LED115") (pin "1") (pinfunction "VDD_1") (pintype "bidirectional"))
      (node (ref "LED116") (pin "1") (pinfunction "VDD_1") (pintype "bidirectional"))
      (node (ref "LED117") (pin "1") (pinfunction "VDD_1") (pintype "bidirectional"))
      (node (ref "LED118") (pin "1") (pinfunction "VDD_1") (pintype "bidirectional"))
      (node (ref "LED119") (pin "1") (pinfunction "VDD_1") (pintype "bidirectional"))
      (node (ref "LED12") (pin "1") (pinfunction "VDD_1") (pintype "bidirectional"))
      (node (ref "LED120") (pin "1") (pinfunction "VDD_1") (pintype "bidirectional"))
      (node (ref "LED121") (pin "1") (pinfunction "VDD_1") (pintype "bidirectional"))
      (node (ref "LED122") (pin "1") (pinfunction "VDD_1") (pintype "bidirectional"))
      (node (ref "LED123") (pin "1") (pinfunction "VDD_1") (pintype "bidirectional"))
      (node (ref "LED124") (pin "1") (pinfunction "VDD_1") (pintype "bidirectional"))
      (node (ref "LED125") (pin "1") (pinfunction "VDD_1") (pintype "bidirectional"))
      (node (ref "LED126") (pin "1") (pinfunction "VDD_1") (pintype "bidirectional"))
      (node (ref "LED127") (pin "1") (pinfunction "VDD_1") (pintype "bidirectional"))
      (node (ref "LED128") (pin "1") (pinfunction "VDD_1") (pintype "bidirectional"))
      (node (ref "LED129") (pin "1") (pinfunction "VDD_1") (pintype "bidirectional"))
      (node (ref "LED13") (pin "1") (pinfunction "VDD_1") (pintype "bidirectional"))
      (node (ref "LED130") (pin "1") (pinfunction "VDD_1") (pintype "bidirectional"))
      (node (ref "LED131") (pin "1") (pinfunction "VDD_1") (pintype "bidirectional"))
      (node (ref "LED132") (pin "1") (pinfunction "VDD_1") (pintype "bidirectional"))
      (node (ref "LED133") (pin "1") (pinfunction "VDD_1") (pintype "bidirectional"))
      (node (ref "LED134") (pin "1") (pinfunction "VDD_1") (pintype "bidirectional"))
      (node (ref "LED135") (pin "1") (pinfunction "VDD_1") (pintype "bidirectional"))
      (node (ref "LED136") (pin "1") (pinfunction "VDD_1") (pintype "bidirectional"))
      (node (ref "LED137") (pin "1") (pinfunction "VDD_1") (pintype "bidirectional"))
      (node (ref "LED138") (pin "1") (pinfunction "VDD_1") (pintype "bidirectional"))
      (node (ref "LED139") (pin "1") (pinfunction "VDD_1") (pintype "bidirectional"))
      (node (ref "LED14") (pin "1") (pinfunction "VDD_1") (pintype "bidirectional"))
      (node (ref "LED140") (pin "1") (pinfunction "VDD_1") (pintype "bidirectional"))
      (node (ref "LED141") (pin "1") (pinfunction "VDD_1") (pintype "bidirectional"))
      (node (ref "LED142") (pin "1") (pinfunction "VDD_1") (pintype "bidirectional"))
      (node (ref "LED143") (pin "1") (pinfunction "VDD_1") (pintype "bidirectional"))
      (node (ref "LED144") (pin "1") (pinfunction "VDD_1") (pintype "bidirectional"))
      (node (ref "LED145") (pin "1") (pinfunction "VDD_1") (pintype "bidirectional"))
      (node (ref "LED146") (pin "1") (pinfunction "VDD_1") (pintype "bidirectional"))
      (node (ref "LED147") (pin "1") (pinfunction "VDD_1") (pintype "bidirectional"))
      (node (ref "LED148") (pin "1") (pinfunction "VDD_1") (pintype "bidirectional"))
      (node (ref "LED149") (pin "1") (pinfunction "VDD_1") (pintype "bidirectional"))
      (node (ref "LED15") (pin "1") (pinfunction "VDD_1") (pintype "bidirectional"))
      (node (ref "LED150") (pin "1") (pinfunction "VDD_1") (pintype "bidirectional"))
      (node (ref "LED151") (pin "1") (pinfunction "VDD_1") (pintype "bidirectional"))
      (node (ref "LED152") (pin "1") (pinfunction "VDD_1") (pintype "bidirectional"))
      (node (ref "LED153") (pin "1") (pinfunction "VDD_1") (pintype "bidirectional"))
      (node (ref "LED154") (pin "1") (pinfunction "VDD_1") (pintype "bidirectional"))
      (node (ref "LED155") (pin "1") (pinfunction "VDD_1") (pintype "bidirectional"))
      (node (ref "LED156") (pin "1") (pinfunction "VDD_1") (pintype "bidirectional"))
      (node (ref "LED157") (pin "1") (pinfunction "VDD_1") (pintype "bidirectional"))
      (node (ref "LED158") (pin "1") (pinfunction "VDD_1") (pintype "bidirectional"))
      (node (ref "LED159") (pin "1") (pinfunction "VDD_1") (pintype "bidirectional"))
      (node (ref "LED16") (pin "1") (pinfunction "VDD_1") (pintype "bidirectional"))
      (node (ref "LED160") (pin "1") (pinfunction "VDD_1") (pintype "bidirectional"))
      (node (ref "LED161") (pin "1") (pinfunction "VDD_1") (pintype "bidirectional"))
      (node (ref "LED162") (pin "1") (pinfunction "VDD_1") (pintype "bidirectional"))
      (node (ref "LED163") (pin "1") (pinfunction "VDD_1") (pintype "bidirectional"))
      (node (ref "LED164") (pin "1") (pinfunction "VDD_1") (pintype "bidirectional"))
      (node (ref "LED165") (pin "1") (pinfunction "VDD_1") (pintype "bidirectional"))
      (node (ref "LED166") (pin "1") (pinfunction "VDD_1") (pintype "bidirectional"))
      (node (ref "LED167") (pin "1") (pinfunction "VDD_1") (pintype "bidirectional"))
      (node (ref "LED168") (pin "1") (pinfunction "VDD_1") (pintype "bidirectional"))
      (node (ref "LED169") (pin "1") (pinfunction "VDD_1") (pintype "bidirectional"))
      (node (ref "LED17") (pin "1") (pinfunction "VDD_1") (pintype "bidirectional"))
      (node (ref "LED170") (pin "1") (pinfunction "VDD_1") (pintype "bidirectional"))
      (node (ref "LED171") (pin "1") (pinfunction "VDD_1") (pintype "bidirectional"))
      (node (ref "LED172") (pin "1") (pinfunction "VDD_1") (pintype "bidirectional"))
      (node (ref "LED173") (pin "1") (pinfunction "VDD_1") (pintype "bidirectional"))
      (node (ref "LED174") (pin "1") (pinfunction "VDD_1") (pintype "bidirectional"))
      (node (ref "LED175") (pin "1") (pinfunction "VDD_1") (pintype "bidirectional"))
      (node (ref "LED176") (pin "1") (pinfunction "VDD_1") (pintype "bidirectional"))
      (node (ref "LED177") (pin "1") (pinfunction "VDD_1") (pintype "bidirectional"))
      (node (ref "LED178") (pin "1") (pinfunction "VDD_1") (pintype "bidirectional"))
      (node (ref "LED179") (pin "1") (pinfunction "VDD_1") (pintype "bidirectional"))
      (node (ref "LED18") (pin "1") (pinfunction "VDD_1") (pintype "bidirectional"))
      (node (ref "LED180") (pin "1") (pinfunction "VDD_1") (pintype "bidirectional"))
      (node (ref "LED181") (pin "1") (pinfunction "VDD_1") (pintype "bidirectional"))
      (node (ref "LED182") (pin "1") (pinfunction "VDD_1") (pintype "bidirectional"))
      (node (ref "LED183") (pin "1") (pinfunction "VDD_1") (pintype "bidirectional"))
      (node (ref "LED184") (pin "1") (pinfunction "VDD_1") (pintype "bidirectional"))
      (node (ref "LED185") (pin "1") (pinfunction "VDD_1") (pintype "bidirectional"))
      (node (ref "LED186") (pin "1") (pinfunction "VDD_1") (pintype "bidirectional"))
      (node (ref "LED187") (pin "1") (pinfunction "VDD_1") (pintype "bidirectional"))
      (node (ref "LED188") (pin "1") (pinfunction "VDD_1") (pintype "bidirectional"))
      (node (ref "LED189") (pin "1") (pinfunction "VDD_1") (pintype "bidirectional"))
      (node (ref "LED19") (pin "1") (pinfunction "VDD_1") (pintype "bidirectional"))
      (node (ref "LED190") (pin "1") (pinfunction "VDD_1") (pintype "bidirectional"))
      (node (ref "LED191") (pin "1") (pinfunction "VDD_1") (pintype "bidirectional"))
      (node (ref "LED192") (pin "1") (pinfunction "VDD_1") (pintype "bidirectional"))
      (node (ref "LED2") (pin "1") (pinfunction "VDD_1") (pintype "bidirectional"))
      (node (ref "LED20") (pin "1") (pinfunction "VDD_1") (pintype "bidirectional"))
      (node (ref "LED21") (pin "1") (pinfunction "VDD_1") (pintype "bidirectional"))
      (node (ref "LED22") (pin "1") (pinfunction "VDD_1") (pintype "bidirectional"))
      (node (ref "LED23") (pin "1") (pinfunction "VDD_1") (pintype "bidirectional"))
      (node (ref "LED24") (pin "1") (pinfunction "VDD_1") (pintype "bidirectional"))
      (node (ref "LED25") (pin "1") (pinfunction "VDD_1") (pintype "bidirectional"))
      (node (ref "LED26") (pin "1") (pinfunction "VDD_1") (pintype "bidirectional"))
      (node (ref "LED27") (pin "1") (pinfunction "VDD_1") (pintype "bidirectional"))
      (node (ref "LED28") (pin "1") (pinfunction "VDD_1") (pintype "bidirectional"))
      (node (ref "LED29") (pin "1") (pinfunction "VDD_1") (pintype "bidirectional"))
      (node (ref "LED3") (pin "1") (pinfunction "VDD_1") (pintype "bidirectional"))
      (node (ref "LED30") (pin "1") (pinfunction "VDD_1") (pintype "bidirectional"))
      (node (ref "LED31") (pin "1") (pinfunction "VDD_1") (pintype "bidirectional"))
      (node (ref "LED32") (pin "1") (pinfunction "VDD_1") (pintype "bidirectional"))
      (node (ref "LED33") (pin "1") (pinfunction "VDD_1") (pintype "bidirectional"))
      (node (ref "LED34") (pin "1") (pinfunction "VDD_1") (pintype "bidirectional"))
      (node (ref "LED35") (pin "1") (pinfunction "VDD_1") (pintype "bidirectional"))
      (node (ref "LED36") (pin "1") (pinfunction "VDD_1") (pintype "bidirectional"))
      (node (ref "LED37") (pin "1") (pinfunction "VDD_1") (pintype "bidirectional"))
      (node (ref "LED38") (pin "1") (pinfunction "VDD_1") (pintype "bidirectional"))
      (node (ref "LED39") (pin "1") (pinfunction "VDD_1") (pintype "bidirectional"))
      (node (ref "LED4") (pin "1") (pinfunction "VDD_1") (pintype "bidirectional"))
      (node (ref "LED40") (pin "1") (pinfunction "VDD_1") (pintype "bidirectional"))
      (node (ref "LED41") (pin "1") (pinfunction "VDD_1") (pintype "bidirectional"))
      (node (ref "LED42") (pin "1") (pinfunction "VDD_1") (pintype "bidirectional"))
      (node (ref "LED43") (pin "1") (pinfunction "VDD_1") (pintype "bidirectional"))
      (node (ref "LED44") (pin "1") (pinfunction "VDD_1") (pintype "bidirectional"))
      (node (ref "LED45") (pin "1") (pinfunction "VDD_1") (pintype "bidirectional"))
      (node (ref "LED46") (pin "1") (pinfunction "VDD_1") (pintype "bidirectional"))
      (node (ref "LED47") (pin "1") (pinfunction "VDD_1") (pintype "bidirectional"))
      (node (ref "LED48") (pin "1") (pinfunction "VDD_1") (pintype "bidirectional"))
      (node (ref "LED49") (pin "1") (pinfunction "VDD_1") (pintype "bidirectional"))
      (node (ref "LED5") (pin "1") (pinfunction "VDD_1") (pintype "bidirectional"))
      (node (ref "LED50") (pin "1") (pinfunction "VDD_1") (pintype "bidirectional"))
      (node (ref "LED51") (pin "1") (pinfunction "VDD_1") (pintype "bidirectional"))
      (node (ref "LED52") (pin "1") (pinfunction "VDD_1") (pintype "bidirectional"))
      (node (ref "LED53") (pin "1") (pinfunction "VDD_1") (pintype "bidirectional"))
      (node (ref "LED54") (pin "1") (pinfunction "VDD_1") (pintype "bidirectional"))
      (node (ref "LED55") (pin "1") (pinfunction "VDD_1") (pintype "bidirectional"))
      (node (ref "LED56") (pin "1") (pinfunction "VDD_1") (pintype "bidirectional"))
      (node (ref "LED57") (pin "1") (pinfunction "VDD_1") (pintype "bidirectional"))
      (node (ref "LED58") (pin "1") (pinfunction "VDD_1") (pintype "bidirectional"))
      (node (ref "LED59") (pin "1") (pinfunction "VDD_1") (pintype "bidirectional"))
      (node (ref "LED6") (pin "1") (pinfunction "VDD_1") (pintype "bidirectional"))
      (node (ref "LED60") (pin "1") (pinfunction "VDD_1") (pintype "bidirectional"))
      (node (ref "LED61") (pin "1") (pinfunction "VDD_1") (pintype "bidirectional"))
      (node (ref "LED62") (pin "1") (pinfunction "VDD_1") (pintype "bidirectional"))
      (node (ref "LED63") (pin "1") (pinfunction "VDD_1") (pintype "bidirectional"))
      (node (ref "LED64") (pin "1") (pinfunction "VDD_1") (pintype "bidirectional"))
      (node (ref "LED65") (pin "1") (pinfunction "VDD_1") (pintype "bidirectional"))
      (node (ref "LED66") (pin "1") (pinfunction "VDD_1") (pintype "bidirectional"))
      (node (ref "LED67") (pin "1") (pinfunction "VDD_1") (pintype "bidirectional"))
      (node (ref "LED68") (pin "1") (pinfunction "VDD_1") (pintype "bidirectional"))
      (node (ref "LED69") (pin "1") (pinfunction "VDD_1") (pintype "bidirectional"))
      (node (ref "LED7") (pin "1") (pinfunction "VDD_1") (pintype "bidirectional"))
      (node (ref "LED70") (pin "1") (pinfunction "VDD_1") (pintype "bidirectional"))
      (node (ref "LED71") (pin "1") (pinfunction "VDD_1") (pintype "bidirectional"))
      (node (ref "LED72") (pin "1") (pinfunction "VDD_1") (pintype "bidirectional"))
      (node (ref "LED73") (pin "1") (pinfunction "VDD_1") (pintype "bidirectional"))
      (node (ref "LED74") (pin "1") (pinfunction "VDD_1") (pintype "bidirectional"))
      (node (ref "LED75") (pin "1") (pinfunction "VDD_1") (pintype "bidirectional"))
      (node (ref "LED76") (pin "1") (pinfunction "VDD_1") (pintype "bidirectional"))
      (node (ref "LED77") (pin "1") (pinfunction "VDD_1") (pintype "bidirectional"))
      (node (ref "LED78") (pin "1") (pinfunction "VDD_1") (pintype "bidirectional"))
      (node (ref "LED79") (pin "1") (pinfunction "VDD_1") (pintype "bidirectional"))
      (node (ref "LED8") (pin "1") (pinfunction "VDD_1") (pintype "bidirectional"))
      (node (ref "LED80") (pin "1") (pinfunction "VDD_1") (pintype "bidirectional"))
      (node (ref "LED81") (pin "1") (pinfunction "VDD_1") (pintype "bidirectional"))
      (node (ref "LED82") (pin "1") (pinfunction "VDD_1") (pintype "bidirectional"))
      (node (ref "LED83") (pin "1") (pinfunction "VDD_1") (pintype "bidirectional"))
      (node (ref "LED84") (pin "1") (pinfunction "VDD_1") (pintype "bidirectional"))
      (node (ref "LED85") (pin "1") (pinfunction "VDD_1") (pintype "bidirectional"))
      (node (ref "LED86") (pin "1") (pinfunction "VDD_1") (pintype "bidirectional"))
      (node (ref "LED87") (pin "1") (pinfunction "VDD_1") (pintype "bidirectional"))
      (node (ref "LED88") (pin "1") (pinfunction "VDD_1") (pintype "bidirectional"))
      (node (ref "LED89") (pin "1") (pinfunction "VDD_1") (pintype "bidirectional"))
      (node (ref "LED9") (pin "1") (pinfunction "VDD_1") (pintype "bidirectional"))
      (node (ref "LED90") (pin "1") (pinfunction "VDD_1") (pintype "bidirectional"))
      (node (ref "LED91") (pin "1") (pinfunction "VDD_1") (pintype "bidirectional"))
      (node (ref "LED92") (pin "1") (pinfunction "VDD_1") (pintype "bidirectional"))
      (node (ref "LED93") (pin "1") (pinfunction "VDD_1") (pintype "bidirectional"))
      (node (ref "LED94") (pin "1") (pinfunction "VDD_1") (pintype "bidirectional"))
      (node (ref "LED95") (pin "1") (pinfunction "VDD_1") (pintype "bidirectional"))
      (node (ref "LED96") (pin "1") (pinfunction "VDD_1") (pintype "bidirectional"))
      (node (ref "LED97") (pin "1") (pinfunction "VDD_1") (pintype "bidirectional"))
      (node (ref "LED98") (pin "1") (pinfunction "VDD_1") (pintype "bidirectional"))
      (node (ref "LED99") (pin "1") (pinfunction "VDD_1") (pintype "bidirectional"))
      (node (ref "PAD10") (pin "1") (pinfunction "P_1") (pintype "passive"))
      (node (ref "PAD14") (pin "1") (pinfunction "P_1") (pintype "passive"))
      (node (ref "PAD18") (pin "1") (pinfunction "P_1") (pintype "passive"))
      (node (ref "PAD2") (pin "1") (pinfunction "P_1") (pintype "passive"))
      (node (ref "PAD22") (pin "1") (pinfunction "P_1") (pintype "passive"))
      (node (ref "PAD26") (pin "1") (pinfunction "P_1") (pintype "passive"))
      (node (ref "PAD6") (pin "1") (pinfunction "P_1") (pintype "passive"))
    )
    (net (code "2") (name "GND") (class "Default")
      (node (ref "C1") (pin "2") (pinfunction "2_2") (pintype "passive"))
      (node (ref "C10") (pin "2") (pinfunction "2_2") (pintype "passive"))
      (node (ref "C100") (pin "2") (pinfunction "2_2") (pintype "passive"))
      (node (ref "C101") (pin "2") (pinfunction "2_2") (pintype "passive"))
      (node (ref "C102") (pin "2") (pinfunction "2_2") (pintype "passive"))
      (node (ref "C103") (pin "2") (pinfunction "2_2") (pintype "passive"))
      (node (ref "C104") (pin "2") (pinfunction "2_2") (pintype "passive"))
      (node (ref "C105") (pin "2") (pinfunction "2_2") (pintype "passive"))
      (node (ref "C106") (pin "2") (pinfunction "2_2") (pintype "passive"))
      (node (ref "C107") (pin "2") (pinfunction "2_2") (pintype "passive"))
      (node (ref "C108") (pin "2") (pinfunction "2_2") (pintype "passive"))
      (node (ref "C109") (pin "2") (pinfunction "2_2") (pintype "passive"))
      (node (ref "C11") (pin "2") (pinfunction "2_2") (pintype "passive"))
      (node (ref "C110") (pin "2") (pinfunction "2_2") (pintype "passive"))
      (node (ref "C111") (pin "2") (pinfunction "2_2") (pintype "passive"))
      (node (ref "C112") (pin "2") (pinfunction "2_2") (pintype "passive"))
      (node (ref "C113") (pin "2") (pinfunction "2_2") (pintype "passive"))
      (node (ref "C114") (pin "2") (pinfunction "2_2") (pintype "passive"))
      (node (ref "C115") (pin "2") (pinfunction "2_2") (pintype "passive"))
      (node (ref "C116") (pin "2") (pinfunction "2_2") (pintype "passive"))
      (node (ref "C117") (pin "2") (pinfunction "2_2") (pintype "passive"))
      (node (ref "C118") (pin "2") (pinfunction "2_2") (pintype "passive"))
      (node (ref "C119") (pin "2") (pinfunction "2_2") (pintype "passive"))
      (node (ref "C12") (pin "2") (pinfunction "2_2") (pintype "passive"))
      (node (ref "C120") (pin "2") (pinfunction "2_2") (pintype "passive"))
      (node (ref "C121") (pin "2") (pinfunction "2_2") (pintype "passive"))
      (node (ref "C122") (pin "2") (pinfunction "2_2") (pintype "passive"))
      (node (ref "C123") (pin "2") (pinfunction "2_2") (pintype "passive"))
      (node (ref "C124") (pin "2") (pinfunction "2_2") (pintype "passive"))
      (node (ref "C125") (pin "2") (pinfunction "2_2") (pintype "passive"))
      (node (ref "C126") (pin "2") (pinfunction "2_2") (pintype "passive"))
      (node (ref "C127") (pin "2") (pinfunction "2_2") (pintype "passive"))
      (node (ref "C128") (pin "2") (pinfunction "2_2") (pintype "passive"))
      (node (ref "C129") (pin "2") (pinfunction "2_2") (pintype "passive"))
      (node (ref "C13") (pin "2") (pinfunction "2_2") (pintype "passive"))
      (node (ref "C130") (pin "2") (pinfunction "2_2") (pintype "passive"))
      (node (ref "C131") (pin "2") (pinfunction "2_2") (pintype "passive"))
      (node (ref "C132") (pin "2") (pinfunction "2_2") (pintype "passive"))
      (node (ref "C133") (pin "2") (pinfunction "2_2") (pintype "passive"))
      (node (ref "C134") (pin "2") (pinfunction "2_2") (pintype "passive"))
      (node (ref "C135") (pin "2") (pinfunction "2_2") (pintype "passive"))
      (node (ref "C136") (pin "2") (pinfunction "2_2") (pintype "passive"))
      (node (ref "C137") (pin "2") (pinfunction "2_2") (pintype "passive"))
      (node (ref "C138") (pin "2") (pinfunction "2_2") (pintype "passive"))
      (node (ref "C139") (pin "2") (pinfunction "2_2") (pintype "passive"))
      (node (ref "C14") (pin "2") (pinfunction "2_2") (pintype "passive"))
      (node (ref "C140") (pin "2") (pinfunction "2_2") (pintype "passive"))
      (node (ref "C141") (pin "2") (pinfunction "2_2") (pintype "passive"))
      (node (ref "C142") (pin "2") (pinfunction "2_2") (pintype "passive"))
      (node (ref "C143") (pin "2") (pinfunction "2_2") (pintype "passive"))
      (node (ref "C144") (pin "2") (pinfunction "2_2") (pintype "passive"))
      (node (ref "C145") (pin "2") (pinfunction "2_2") (pintype "passive"))
      (node (ref "C146") (pin "2") (pinfunction "2_2") (pintype "passive"))
      (node (ref "C147") (pin "2") (pinfunction "2_2") (pintype "passive"))
      (node (ref "C148") (pin "2") (pinfunction "2_2") (pintype "passive"))
      (node (ref "C149") (pin "2") (pinfunction "2_2") (pintype "passive"))
      (node (ref "C15") (pin "2") (pinfunction "2_2") (pintype "passive"))
      (node (ref "C150") (pin "2") (pinfunction "2_2") (pintype "passive"))
      (node (ref "C151") (pin "2") (pinfunction "2_2") (pintype "passive"))
      (node (ref "C152") (pin "2") (pinfunction "2_2") (pintype "passive"))
      (node (ref "C153") (pin "2") (pinfunction "2_2") (pintype "passive"))
      (node (ref "C154") (pin "2") (pinfunction "2_2") (pintype "passive"))
      (node (ref "C155") (pin "2") (pinfunction "2_2") (pintype "passive"))
      (node (ref "C156") (pin "2") (pinfunction "2_2") (pintype "passive"))
      (node (ref "C157") (pin "2") (pinfunction "2_2") (pintype "passive"))
      (node (ref "C158") (pin "2") (pinfunction "2_2") (pintype "passive"))
      (node (ref "C159") (pin "2") (pinfunction "2_2") (pintype "passive"))
      (node (ref "C16") (pin "2") (pinfunction "2_2") (pintype "passive"))
      (node (ref "C160") (pin "2") (pinfunction "2_2") (pintype "passive"))
      (node (ref "C161") (pin "2") (pinfunction "2_2") (pintype "passive"))
      (node (ref "C162") (pin "2") (pinfunction "2_2") (pintype "passive"))
      (node (ref "C163") (pin "2") (pinfunction "2_2") (pintype "passive"))
      (node (ref "C164") (pin "2") (pinfunction "2_2") (pintype "passive"))
      (node (ref "C165") (pin "2") (pinfunction "2_2") (pintype "passive"))
      (node (ref "C166") (pin "2") (pinfunction "2_2") (pintype "passive"))
      (node (ref "C167") (pin "2") (pinfunction "2_2") (pintype "passive"))
      (node (ref "C168") (pin "2") (pinfunction "2_2") (pintype "passive"))
      (node (ref "C169") (pin "2") (pinfunction "2_2") (pintype "passive"))
      (node (ref "C17") (pin "2") (pinfunction "2_2") (pintype "passive"))
      (node (ref "C170") (pin "2") (pinfunction "2_2") (pintype "passive"))
      (node (ref "C171") (pin "2") (pinfunction "2_2") (pintype "passive"))
      (node (ref "C172") (pin "2") (pinfunction "2_2") (pintype "passive"))
      (node (ref "C173") (pin "2") (pinfunction "2_2") (pintype "passive"))
      (node (ref "C174") (pin "2") (pinfunction "2_2") (pintype "passive"))
      (node (ref "C175") (pin "2") (pinfunction "2_2") (pintype "passive"))
      (node (ref "C176") (pin "2") (pinfunction "2_2") (pintype "passive"))
      (node (ref "C177") (pin "2") (pinfunction "2_2") (pintype "passive"))
      (node (ref "C178") (pin "2") (pinfunction "2_2") (pintype "passive"))
      (node (ref "C179") (pin "2") (pinfunction "2_2") (pintype "passive"))
      (node (ref "C18") (pin "2") (pinfunction "2_2") (pintype "passive"))
      (node (ref "C180") (pin "2") (pinfunction "2_2") (pintype "passive"))
      (node (ref "C181") (pin "2") (pinfunction "2_2") (pintype "passive"))
      (node (ref "C182") (pin "2") (pinfunction "2_2") (pintype "passive"))
      (node (ref "C183") (pin "2") (pinfunction "2_2") (pintype "passive"))
      (node (ref "C184") (pin "2") (pinfunction "2_2") (pintype "passive"))
      (node (ref "C185") (pin "2") (pinfunction "2_2") (pintype "passive"))
      (node (ref "C186") (pin "2") (pinfunction "2_2") (pintype "passive"))
      (node (ref "C187") (pin "2") (pinfunction "2_2") (pintype "passive"))
      (node (ref "C188") (pin "2") (pinfunction "2_2") (pintype "passive"))
      (node (ref "C189") (pin "2") (pinfunction "2_2") (pintype "passive"))
      (node (ref "C19") (pin "2") (pinfunction "2_2") (pintype "passive"))
      (node (ref "C190") (pin "2") (pinfunction "2_2") (pintype "passive"))
      (node (ref "C191") (pin "2") (pinfunction "2_2") (pintype "passive"))
      (node (ref "C192") (pin "2") (pinfunction "2_2") (pintype "passive"))
      (node (ref "C2") (pin "2") (pinfunction "2_2") (pintype "passive"))
      (node (ref "C20") (pin "2") (pinfunction "2_2") (pintype "passive"))
      (node (ref "C21") (pin "2") (pinfunction "2_2") (pintype "passive"))
      (node (ref "C22") (pin "2") (pinfunction "2_2") (pintype "passive"))
      (node (ref "C23") (pin "2") (pinfunction "2_2") (pintype "passive"))
      (node (ref "C24") (pin "2") (pinfunction "2_2") (pintype "passive"))
      (node (ref "C25") (pin "2") (pinfunction "2_2") (pintype "passive"))
      (node (ref "C26") (pin "2") (pinfunction "2_2") (pintype "passive"))
      (node (ref "C27") (pin "2") (pinfunction "2_2") (pintype "passive"))
      (node (ref "C28") (pin "2") (pinfunction "2_2") (pintype "passive"))
      (node (ref "C29") (pin "2") (pinfunction "2_2") (pintype "passive"))
      (node (ref "C3") (pin "2") (pinfunction "2_2") (pintype "passive"))
      (node (ref "C30") (pin "2") (pinfunction "2_2") (pintype "passive"))
      (node (ref "C31") (pin "2") (pinfunction "2_2") (pintype "passive"))
      (node (ref "C32") (pin "2") (pinfunction "2_2") (pintype "passive"))
      (node (ref "C33") (pin "2") (pinfunction "2_2") (pintype "passive"))
      (node (ref "C34") (pin "2") (pinfunction "2_2") (pintype "passive"))
      (node (ref "C35") (pin "2") (pinfunction "2_2") (pintype "passive"))
      (node (ref "C36") (pin "2") (pinfunction "2_2") (pintype "passive"))
      (node (ref "C37") (pin "2") (pinfunction "2_2") (pintype "passive"))
      (node (ref "C38") (pin "2") (pinfunction "2_2") (pintype "passive"))
      (node (ref "C39") (pin "2") (pinfunction "2_2") (pintype "passive"))
      (node (ref "C4") (pin "2") (pinfunction "2_2") (pintype "passive"))
      (node (ref "C40") (pin "2") (pinfunction "2_2") (pintype "passive"))
      (node (ref "C41") (pin "2") (pinfunction "2_2") (pintype "passive"))
      (node (ref "C42") (pin "2") (pinfunction "2_2") (pintype "passive"))
      (node (ref "C43") (pin "2") (pinfunction "2_2") (pintype "passive"))
      (node (ref "C44") (pin "2") (pinfunction "2_2") (pintype "passive"))
      (node (ref "C45") (pin "2") (pinfunction "2_2") (pintype "passive"))
      (node (ref "C46") (pin "2") (pinfunction "2_2") (pintype "passive"))
      (node (ref "C47") (pin "2") (pinfunction "2_2") (pintype "passive"))
      (node (ref "C48") (pin "2") (pinfunction "2_2") (pintype "passive"))
      (node (ref "C49") (pin "2") (pinfunction "2_2") (pintype "passive"))
      (node (ref "C5") (pin "2") (pinfunction "2_2") (pintype "passive"))
      (node (ref "C50") (pin "2") (pinfunction "2_2") (pintype "passive"))
      (node (ref "C51") (pin "2") (pinfunction "2_2") (pintype "passive"))
      (node (ref "C52") (pin "2") (pinfunction "2_2") (pintype "passive"))
      (node (ref "C53") (pin "2") (pinfunction "2_2") (pintype "passive"))
      (node (ref "C54") (pin "2") (pinfunction "2_2") (pintype "passive"))
      (node (ref "C55") (pin "2") (pinfunction "2_2") (pintype "passive"))
      (node (ref "C56") (pin "2") (pinfunction "2_2") (pintype "passive"))
      (node (ref "C57") (pin "2") (pinfunction "2_2") (pintype "passive"))
      (node (ref "C58") (pin "2") (pinfunction "2_2") (pintype "passive"))
      (node (ref "C59") (pin "2") (pinfunction "2_2") (pintype "passive"))
      (node (ref "C6") (pin "2") (pinfunction "2_2") (pintype "passive"))
      (node (ref "C60") (pin "2") (pinfunction "2_2") (pintype "passive"))
      (node (ref "C61") (pin "2") (pinfunction "2_2") (pintype "passive"))
      (node (ref "C62") (pin "2") (pinfunction "2_2") (pintype "passive"))
      (node (ref "C63") (pin "2") (pinfunction "2_2") (pintype "passive"))
      (node (ref "C64") (pin "2") (pinfunction "2_2") (pintype "passive"))
      (node (ref "C65") (pin "2") (pinfunction "2_2") (pintype "passive"))
      (node (ref "C66") (pin "2") (pinfunction "2_2") (pintype "passive"))
      (node (ref "C67") (pin "2") (pinfunction "2_2") (pintype "passive"))
      (node (ref "C68") (pin "2") (pinfunction "2_2") (pintype "passive"))
      (node (ref "C69") (pin "2") (pinfunction "2_2") (pintype "passive"))
      (node (ref "C7") (pin "2") (pinfunction "2_2") (pintype "passive"))
      (node (ref "C70") (pin "2") (pinfunction "2_2") (pintype "passive"))
      (node (ref "C71") (pin "2") (pinfunction "2_2") (pintype "passive"))
      (node (ref "C72") (pin "2") (pinfunction "2_2") (pintype "passive"))
      (node (ref "C73") (pin "2") (pinfunction "2_2") (pintype "passive"))
      (node (ref "C74") (pin "2") (pinfunction "2_2") (pintype "passive"))
      (node (ref "C75") (pin "2") (pinfunction "2_2") (pintype "passive"))
      (node (ref "C76") (pin "2") (pinfunction "2_2") (pintype "passive"))
      (node (ref "C77") (pin "2") (pinfunction "2_2") (pintype "passive"))
      (node (ref "C78") (pin "2") (pinfunction "2_2") (pintype "passive"))
      (node (ref "C79") (pin "2") (pinfunction "2_2") (pintype "passive"))
      (node (ref "C8") (pin "2") (pinfunction "2_2") (pintype "passive"))
      (node (ref "C80") (pin "2") (pinfunction "2_2") (pintype "passive"))
      (node (ref "C81") (pin "2") (pinfunction "2_2") (pintype "passive"))
      (node (ref "C82") (pin "2") (pinfunction "2_2") (pintype "passive"))
      (node (ref "C83") (pin "2") (pinfunction "2_2") (pintype "passive"))
      (node (ref "C84") (pin "2") (pinfunction "2_2") (pintype "passive"))
      (node (ref "C85") (pin "2") (pinfunction "2_2") (pintype "passive"))
      (node (ref "C86") (pin "2") (pinfunction "2_2") (pintype "passive"))
      (node (ref "C87") (pin "2") (pinfunction "2_2") (pintype "passive"))
      (node (ref "C88") (pin "2") (pinfunction "2_2") (pintype "passive"))
      (node (ref "C89") (pin "2") (pinfunction "2_2") (pintype "passive"))
      (node (ref "C9") (pin "2") (pinfunction "2_2") (pintype "passive"))
      (node (ref "C90") (pin "2") (pinfunction "2_2") (pintype "passive"))
      (node (ref "C91") (pin "2") (pinfunction "2_2") (pintype "passive"))
      (node (ref "C92") (pin "2") (pinfunction "2_2") (pintype "passive"))
      (node (ref "C93") (pin "2") (pinfunction "2_2") (pintype "passive"))
      (node (ref "C94") (pin "2") (pinfunction "2_2") (pintype "passive"))
      (node (ref "C95") (pin "2") (pinfunction "2_2") (pintype "passive"))
      (node (ref "C96") (pin "2") (pinfunction "2_2") (pintype "passive"))
      (node (ref "C97") (pin "2") (pinfunction "2_2") (pintype "passive"))
      (node (ref "C98") (pin "2") (pinfunction "2_2") (pintype "passive"))
      (node (ref "C99") (pin "2") (pinfunction "2_2") (pintype "passive"))
      (node (ref "LED1") (pin "3") (pinfunction "VSS_3") (pintype "bidirectional"))
      (node (ref "LED10") (pin "3") (pinfunction "VSS_3") (pintype "bidirectional"))
      (node (ref "LED100") (pin "3") (pinfunction "VSS_3") (pintype "bidirectional"))
      (node (ref "LED101") (pin "3") (pinfunction "VSS_3") (pintype "bidirectional"))
      (node (ref "LED102") (pin "3") (pinfunction "VSS_3") (pintype "bidirectional"))
      (node (ref "LED103") (pin "3") (pinfunction "VSS_3") (pintype "bidirectional"))
      (node (ref "LED104") (pin "3") (pinfunction "VSS_3") (pintype "bidirectional"))
      (node (ref "LED105") (pin "3") (pinfunction "VSS_3") (pintype "bidirectional"))
      (node (ref "LED106") (pin "3") (pinfunction "VSS_3") (pintype "bidirectional"))
      (node (ref "LED107") (pin "3") (pinfunction "VSS_3") (pintype "bidirectional"))
      (node (ref "LED108") (pin "3") (pinfunction "VSS_3") (pintype "bidirectional"))
      (node (ref "LED109") (pin "3") (pinfunction "VSS_3") (pintype "bidirectional"))
      (node (ref "LED11") (pin "3") (pinfunction "VSS_3") (pintype "bidirectional"))
      (node (ref "LED110") (pin "3") (pinfunction "VSS_3") (pintype "bidirectional"))
      (node (ref "LED111") (pin "3") (pinfunction "VSS_3") (pintype "bidirectional"))
      (node (ref "LED112") (pin "3") (pinfunction "VSS_3") (pintype "bidirectional"))
      (node (ref "LED113") (pin "3") (pinfunction "VSS_3") (pintype "bidirectional"))
      (node (ref "LED114") (pin "3") (pinfunction "VSS_3") (pintype "bidirectional"))
      (node (ref "LED115") (pin "3") (pinfunction "VSS_3") (pintype "bidirectional"))
      (node (ref "LED116") (pin "3") (pinfunction "VSS_3") (pintype "bidirectional"))
      (node (ref "LED117") (pin "3") (pinfunction "VSS_3") (pintype "bidirectional"))
      (node (ref "LED118") (pin "3") (pinfunction "VSS_3") (pintype "bidirectional"))
      (node (ref "LED119") (pin "3") (pinfunction "VSS_3") (pintype "bidirectional"))
      (node (ref "LED12") (pin "3") (pinfunction "VSS_3") (pintype "bidirectional"))
      (node (ref "LED120") (pin "3") (pinfunction "VSS_3") (pintype "bidirectional"))
      (node (ref "LED121") (pin "3") (pinfunction "VSS_3") (pintype "bidirectional"))
      (node (ref "LED122") (pin "3") (pinfunction "VSS_3") (pintype "bidirectional"))
      (node (ref "LED123") (pin "3") (pinfunction "VSS_3") (pintype "bidirectional"))
      (node (ref "LED124") (pin "3") (pinfunction "VSS_3") (pintype "bidirectional"))
      (node (ref "LED125") (pin "3") (pinfunction "VSS_3") (pintype "bidirectional"))
      (node (ref "LED126") (pin "3") (pinfunction "VSS_3") (pintype "bidirectional"))
      (node (ref "LED127") (pin "3") (pinfunction "VSS_3") (pintype "bidirectional"))
      (node (ref "LED128") (pin "3") (pinfunction "VSS_3") (pintype "bidirectional"))
      (node (ref "LED129") (pin "3") (pinfunction "VSS_3") (pintype "bidirectional"))
      (node (ref "LED13") (pin "3") (pinfunction "VSS_3") (pintype "bidirectional"))
      (node (ref "LED130") (pin "3") (pinfunction "VSS_3") (pintype "bidirectional"))
      (node (ref "LED131") (pin "3") (pinfunction "VSS_3") (pintype "bidirectional"))
      (node (ref "LED132") (pin "3") (pinfunction "VSS_3") (pintype "bidirectional"))
      (node (ref "LED133") (pin "3") (pinfunction "VSS_3") (pintype "bidirectional"))
      (node (ref "LED134") (pin "3") (pinfunction "VSS_3") (pintype "bidirectional"))
      (node (ref "LED135") (pin "3") (pinfunction "VSS_3") (pintype "bidirectional"))
      (node (ref "LED136") (pin "3") (pinfunction "VSS_3") (pintype "bidirectional"))
      (node (ref "LED137") (pin "3") (pinfunction "VSS_3") (pintype "bidirectional"))
      (node (ref "LED138") (pin "3") (pinfunction "VSS_3") (pintype "bidirectional"))
      (node (ref "LED139") (pin "3") (pinfunction "VSS_3") (pintype "bidirectional"))
      (node (ref "LED14") (pin "3") (pinfunction "VSS_3") (pintype "bidirectional"))
      (node (ref "LED140") (pin "3") (pinfunction "VSS_3") (pintype "bidirectional"))
      (node (ref "LED141") (pin "3") (pinfunction "VSS_3") (pintype "bidirectional"))
      (node (ref "LED142") (pin "3") (pinfunction "VSS_3") (pintype "bidirectional"))
      (node (ref "LED143") (pin "3") (pinfunction "VSS_3") (pintype "bidirectional"))
      (node (ref "LED144") (pin "3") (pinfunction "VSS_3") (pintype "bidirectional"))
      (node (ref "LED145") (pin "3") (pinfunction "VSS_3") (pintype "bidirectional"))
      (node (ref "LED146") (pin "3") (pinfunction "VSS_3") (pintype "bidirectional"))
      (node (ref "LED147") (pin "3") (pinfunction "VSS_3") (pintype "bidirectional"))
      (node (ref "LED148") (pin "3") (pinfunction "VSS_3") (pintype "bidirectional"))
      (node (ref "LED149") (pin "3") (pinfunction "VSS_3") (pintype "bidirectional"))
      (node (ref "LED15") (pin "3") (pinfunction "VSS_3") (pintype "bidirectional"))
      (node (ref "LED150") (pin "3") (pinfunction "VSS_3") (pintype "bidirectional"))
      (node (ref "LED151") (pin "3") (pinfunction "VSS_3") (pintype "bidirectional"))
      (node (ref "LED152") (pin "3") (pinfunction "VSS_3") (pintype "bidirectional"))
      (node (ref "LED153") (pin "3") (pinfunction "VSS_3") (pintype "bidirectional"))
      (node (ref "LED154") (pin "3") (pinfunction "VSS_3") (pintype "bidirectional"))
      (node (ref "LED155") (pin "3") (pinfunction "VSS_3") (pintype "bidirectional"))
      (node (ref "LED156") (pin "3") (pinfunction "VSS_3") (pintype "bidirectional"))
      (node (ref "LED157") (pin "3") (pinfunction "VSS_3") (pintype "bidirectional"))
      (node (ref "LED158") (pin "3") (pinfunction "VSS_3") (pintype "bidirectional"))
      (node (ref "LED159") (pin "3") (pinfunction "VSS_3") (pintype "bidirectional"))
      (node (ref "LED16") (pin "3") (pinfunction "VSS_3") (pintype "bidirectional"))
      (node (ref "LED160") (pin "3") (pinfunction "VSS_3") (pintype "bidirectional"))
      (node (ref "LED161") (pin "3") (pinfunction "VSS_3") (pintype "bidirectional"))
      (node (ref "LED162") (pin "3") (pinfunction "VSS_3") (pintype "bidirectional"))
      (node (ref "LED163") (pin "3") (pinfunction "VSS_3") (pintype "bidirectional"))
      (node (ref "LED164") (pin "3") (pinfunction "VSS_3") (pintype "bidirectional"))
      (node (ref "LED165") (pin "3") (pinfunction "VSS_3") (pintype "bidirectional"))
      (node (ref "LED166") (pin "3") (pinfunction "VSS_3") (pintype "bidirectional"))
      (node (ref "LED167") (pin "3") (pinfunction "VSS_3") (pintype "bidirectional"))
      (node (ref "LED168") (pin "3") (pinfunction "VSS_3") (pintype "bidirectional"))
      (node (ref "LED169") (pin "3") (pinfunction "VSS_3") (pintype "bidirectional"))
      (node (ref "LED17") (pin "3") (pinfunction "VSS_3") (pintype "bidirectional"))
      (node (ref "LED170") (pin "3") (pinfunction "VSS_3") (pintype "bidirectional"))
      (node (ref "LED171") (pin "3") (pinfunction "VSS_3") (pintype "bidirectional"))
      (node (ref "LED172") (pin "3") (pinfunction "VSS_3") (pintype "bidirectional"))
      (node (ref "LED173") (pin "3") (pinfunction "VSS_3") (pintype "bidirectional"))
      (node (ref "LED174") (pin "3") (pinfunction "VSS_3") (pintype "bidirectional"))
      (node (ref "LED175") (pin "3") (pinfunction "VSS_3") (pintype "bidirectional"))
      (node (ref "LED176") (pin "3") (pinfunction "VSS_3") (pintype "bidirectional"))
      (node (ref "LED177") (pin "3") (pinfunction "VSS_3") (pintype "bidirectional"))
      (node (ref "LED178") (pin "3") (pinfunction "VSS_3") (pintype "bidirectional"))
      (node (ref "LED179") (pin "3") (pinfunction "VSS_3") (pintype "bidirectional"))
      (node (ref "LED18") (pin "3") (pinfunction "VSS_3") (pintype "bidirectional"))
      (node (ref "LED180") (pin "3") (pinfunction "VSS_3") (pintype "bidirectional"))
      (node (ref "LED181") (pin "3") (pinfunction "VSS_3") (pintype "bidirectional"))
      (node (ref "LED182") (pin "3") (pinfunction "VSS_3") (pintype "bidirectional"))
      (node (ref "LED183") (pin "3") (pinfunction "VSS_3") (pintype "bidirectional"))
      (node (ref "LED184") (pin "3") (pinfunction "VSS_3") (pintype "bidirectional"))
      (node (ref "LED185") (pin "3") (pinfunction "VSS_3") (pintype "bidirectional"))
      (node (ref "LED186") (pin "3") (pinfunction "VSS_3") (pintype "bidirectional"))
      (node (ref "LED187") (pin "3") (pinfunction "VSS_3") (pintype "bidirectional"))
      (node (ref "LED188") (pin "3") (pinfunction "VSS_3") (pintype "bidirectional"))
      (node (ref "LED189") (pin "3") (pinfunction "VSS_3") (pintype "bidirectional"))
      (node (ref "LED19") (pin "3") (pinfunction "VSS_3") (pintype "bidirectional"))
      (node (ref "LED190") (pin "3") (pinfunction "VSS_3") (pintype "bidirectional"))
      (node (ref "LED191") (pin "3") (pinfunction "VSS_3") (pintype "bidirectional"))
      (node (ref "LED192") (pin "3") (pinfunction "VSS_3") (pintype "bidirectional"))
      (node (ref "LED2") (pin "3") (pinfunction "VSS_3") (pintype "bidirectional"))
      (node (ref "LED20") (pin "3") (pinfunction "VSS_3") (pintype "bidirectional"))
      (node (ref "LED21") (pin "3") (pinfunction "VSS_3") (pintype "bidirectional"))
      (node (ref "LED22") (pin "3") (pinfunction "VSS_3") (pintype "bidirectional"))
      (node (ref "LED23") (pin "3") (pinfunction "VSS_3") (pintype "bidirectional"))
      (node (ref "LED24") (pin "3") (pinfunction "VSS_3") (pintype "bidirectional"))
      (node (ref "LED25") (pin "3") (pinfunction "VSS_3") (pintype "bidirectional"))
      (node (ref "LED26") (pin "3") (pinfunction "VSS_3") (pintype "bidirectional"))
      (node (ref "LED27") (pin "3") (pinfunction "VSS_3") (pintype "bidirectional"))
      (node (ref "LED28") (pin "3") (pinfunction "VSS_3") (pintype "bidirectional"))
      (node (ref "LED29") (pin "3") (pinfunction "VSS_3") (pintype "bidirectional"))
      (node (ref "LED3") (pin "3") (pinfunction "VSS_3") (pintype "bidirectional"))
      (node (ref "LED30") (pin "3") (pinfunction "VSS_3") (pintype "bidirectional"))
      (node (ref "LED31") (pin "3") (pinfunction "VSS_3") (pintype "bidirectional"))
      (node (ref "LED32") (pin "3") (pinfunction "VSS_3") (pintype "bidirectional"))
      (node (ref "LED33") (pin "3") (pinfunction "VSS_3") (pintype "bidirectional"))
      (node (ref "LED34") (pin "3") (pinfunction "VSS_3") (pintype "bidirectional"))
      (node (ref "LED35") (pin "3") (pinfunction "VSS_3") (pintype "bidirectional"))
      (node (ref "LED36") (pin "3") (pinfunction "VSS_3") (pintype "bidirectional"))
      (node (ref "LED37") (pin "3") (pinfunction "VSS_3") (pintype "bidirectional"))
      (node (ref "LED38") (pin "3") (pinfunction "VSS_3") (pintype "bidirectional"))
      (node (ref "LED39") (pin "3") (pinfunction "VSS_3") (pintype "bidirectional"))
      (node (ref "LED4") (pin "3") (pinfunction "VSS_3") (pintype "bidirectional"))
      (node (ref "LED40") (pin "3") (pinfunction "VSS_3") (pintype "bidirectional"))
      (node (ref "LED41") (pin "3") (pinfunction "VSS_3") (pintype "bidirectional"))
      (node (ref "LED42") (pin "3") (pinfunction "VSS_3") (pintype "bidirectional"))
      (node (ref "LED43") (pin "3") (pinfunction "VSS_3") (pintype "bidirectional"))
      (node (ref "LED44") (pin "3") (pinfunction "VSS_3") (pintype "bidirectional"))
      (node (ref "LED45") (pin "3") (pinfunction "VSS_3") (pintype "bidirectional"))
      (node (ref "LED46") (pin "3") (pinfunction "VSS_3") (pintype "bidirectional"))
      (node (ref "LED47") (pin "3") (pinfunction "VSS_3") (pintype "bidirectional"))
      (node (ref "LED48") (pin "3") (pinfunction "VSS_3") (pintype "bidirectional"))
      (node (ref "LED49") (pin "3") (pinfunction "VSS_3") (pintype "bidirectional"))
      (node (ref "LED5") (pin "3") (pinfunction "VSS_3") (pintype "bidirectional"))
      (node (ref "LED50") (pin "3") (pinfunction "VSS_3") (pintype "bidirectional"))
      (node (ref "LED51") (pin "3") (pinfunction "VSS_3") (pintype "bidirectional"))
      (node (ref "LED52") (pin "3") (pinfunction "VSS_3") (pintype "bidirectional"))
      (node (ref "LED53") (pin "3") (pinfunction "VSS_3") (pintype "bidirectional"))
      (node (ref "LED54") (pin "3") (pinfunction "VSS_3") (pintype "bidirectional"))
      (node (ref "LED55") (pin "3") (pinfunction "VSS_3") (pintype "bidirectional"))
      (node (ref "LED56") (pin "3") (pinfunction "VSS_3") (pintype "bidirectional"))
      (node (ref "LED57") (pin "3") (pinfunction "VSS_3") (pintype "bidirectional"))
      (node (ref "LED58") (pin "3") (pinfunction "VSS_3") (pintype "bidirectional"))
      (node (ref "LED59") (pin "3") (pinfunction "VSS_3") (pintype "bidirectional"))
      (node (ref "LED6") (pin "3") (pinfunction "VSS_3") (pintype "bidirectional"))
      (node (ref "LED60") (pin "3") (pinfunction "VSS_3") (pintype "bidirectional"))
      (node (ref "LED61") (pin "3") (pinfunction "VSS_3") (pintype "bidirectional"))
      (node (ref "LED62") (pin "3") (pinfunction "VSS_3") (pintype "bidirectional"))
      (node (ref "LED63") (pin "3") (pinfunction "VSS_3") (pintype "bidirectional"))
      (node (ref "LED64") (pin "3") (pinfunction "VSS_3") (pintype "bidirectional"))
      (node (ref "LED65") (pin "3") (pinfunction "VSS_3") (pintype "bidirectional"))
      (node (ref "LED66") (pin "3") (pinfunction "VSS_3") (pintype "bidirectional"))
      (node (ref "LED67") (pin "3") (pinfunction "VSS_3") (pintype "bidirectional"))
      (node (ref "LED68") (pin "3") (pinfunction "VSS_3") (pintype "bidirectional"))
      (node (ref "LED69") (pin "3") (pinfunction "VSS_3") (pintype "bidirectional"))
      (node (ref "LED7") (pin "3") (pinfunction "VSS_3") (pintype "bidirectional"))
      (node (ref "LED70") (pin "3") (pinfunction "VSS_3") (pintype "bidirectional"))
      (node (ref "LED71") (pin "3") (pinfunction "VSS_3") (pintype "bidirectional"))
      (node (ref "LED72") (pin "3") (pinfunction "VSS_3") (pintype "bidirectional"))
      (node (ref "LED73") (pin "3") (pinfunction "VSS_3") (pintype "bidirectional"))
      (node (ref "LED74") (pin "3") (pinfunction "VSS_3") (pintype "bidirectional"))
      (node (ref "LED75") (pin "3") (pinfunction "VSS_3") (pintype "bidirectional"))
      (node (ref "LED76") (pin "3") (pinfunction "VSS_3") (pintype "bidirectional"))
      (node (ref "LED77") (pin "3") (pinfunction "VSS_3") (pintype "bidirectional"))
      (node (ref "LED78") (pin "3") (pinfunction "VSS_3") (pintype "bidirectional"))
      (node (ref "LED79") (pin "3") (pinfunction "VSS_3") (pintype "bidirectional"))
      (node (ref "LED8") (pin "3") (pinfunction "VSS_3") (pintype "bidirectional"))
      (node (ref "LED80") (pin "3") (pinfunction "VSS_3") (pintype "bidirectional"))
      (node (ref "LED81") (pin "3") (pinfunction "VSS_3") (pintype "bidirectional"))
      (node (ref "LED82") (pin "3") (pinfunction "VSS_3") (pintype "bidirectional"))
      (node (ref "LED83") (pin "3") (pinfunction "VSS_3") (pintype "bidirectional"))
      (node (ref "LED84") (pin "3") (pinfunction "VSS_3") (pintype "bidirectional"))
      (node (ref "LED85") (pin "3") (pinfunction "VSS_3") (pintype "bidirectional"))
      (node (ref "LED86") (pin "3") (pinfunction "VSS_3") (pintype "bidirectional"))
      (node (ref "LED87") (pin "3") (pinfunction "VSS_3") (pintype "bidirectional"))
      (node (ref "LED88") (pin "3") (pinfunction "VSS_3") (pintype "bidirectional"))
      (node (ref "LED89") (pin "3") (pinfunction "VSS_3") (pintype "bidirectional"))
      (node (ref "LED9") (pin "3") (pinfunction "VSS_3") (pintype "bidirectional"))
      (node (ref "LED90") (pin "3") (pinfunction "VSS_3") (pintype "bidirectional"))
      (node (ref "LED91") (pin "3") (pinfunction "VSS_3") (pintype "bidirectional"))
      (node (ref "LED92") (pin "3") (pinfunction "VSS_3") (pintype "bidirectional"))
      (node (ref "LED93") (pin "3") (pinfunction "VSS_3") (pintype "bidirectional"))
      (node (ref "LED94") (pin "3") (pinfunction "VSS_3") (pintype "bidirectional"))
      (node (ref "LED95") (pin "3") (pinfunction "VSS_3") (pintype "bidirectional"))
      (node (ref "LED96") (pin "3") (pinfunction "VSS_3") (pintype "bidirectional"))
      (node (ref "LED97") (pin "3") (pinfunction "VSS_3") (pintype "bidirectional"))
      (node (ref "LED98") (pin "3") (pinfunction "VSS_3") (pintype "bidirectional"))
      (node (ref "LED99") (pin "3") (pinfunction "VSS_3") (pintype "bidirectional"))
      (node (ref "PAD11") (pin "1") (pinfunction "P_1") (pintype "passive"))
      (node (ref "PAD15") (pin "1") (pinfunction "P_1") (pintype "passive"))
      (node (ref "PAD19") (pin "1") (pinfunction "P_1") (pintype "passive"))
      (node (ref "PAD23") (pin "1") (pinfunction "P_1") (pintype "passive"))
      (node (ref "PAD27") (pin "1") (pinfunction "P_1") (pintype "passive"))
      (node (ref "PAD3") (pin "1") (pinfunction "P_1") (pintype "passive"))
      (node (ref "PAD7") (pin "1") (pinfunction "P_1") (pintype "passive"))
    )
    (net (code "3") (name "Net-(LED1-DI)") (class "Default")
      (node (ref "LED1") (pin "4") (pinfunction "DI_4") (pintype "bidirectional"))
      (node (ref "PAD1") (pin "1") (pinfunction "P_1") (pintype "passive"))
    )
    (net (code "4") (name "Net-(LED1-DO)") (class "Default")
      (node (ref "LED1") (pin "2") (pinfunction "DO_2") (pintype "bidirectional"))
      (node (ref "LED2") (pin "4") (pinfunction "DI_4") (pintype "bidirectional"))
    )
    (net (code "5") (name "Net-(LED2-DO)") (class "Default")
      (node (ref "LED2") (pin "2") (pinfunction "DO_2") (pintype "bidirectional"))
      (node (ref "LED3") (pin "4") (pinfunction "DI_4") (pintype "bidirectional"))
    )
    (net (code "6") (name "Net-(LED3-DO)") (class "Default")
      (node (ref "LED3") (pin "2") (pinfunction "DO_2") (pintype "bidirectional"))
      (node (ref "LED4") (pin "4") (pinfunction "DI_4") (pintype "bidirectional"))
    )
    (net (code "7") (name "Net-(LED4-DO)") (class "Default")
      (node (ref "LED4") (pin "2") (pinfunction "DO_2") (pintype "bidirectional"))
      (node (ref "LED5") (pin "4") (pinfunction "DI_4") (pintype "bidirectional"))
    )
    (net (code "8") (name "Net-(LED5-DO)") (class "Default")
      (node (ref "LED5") (pin "2") (pinfunction "DO_2") (pintype "bidirectional"))
      (node (ref "LED6") (pin "4") (pinfunction "DI_4") (pintype "bidirectional"))
    )
    (net (code "9") (name "Net-(LED6-DO)") (class "Default")
      (node (ref "LED6") (pin "2") (pinfunction "DO_2") (pintype "bidirectional"))
      (node (ref "LED7") (pin "4") (pinfunction "DI_4") (pintype "bidirectional"))
    )
    (net (code "10") (name "Net-(LED7-DO)") (class "Default")
      (node (ref "LED7") (pin "2") (pinfunction "DO_2") (pintype "bidirectional"))
      (node (ref "LED8") (pin "4") (pinfunction "DI_4") (pintype "bidirectional"))
    )
    (net (code "11") (name "Net-(LED8-DO)") (class "Default")
      (node (ref "LED8") (pin "2") (pinfunction "DO_2") (pintype "bidirectional"))
      (node (ref "PAD4") (pin "1") (pinfunction "P_1") (pintype "passive"))
    )
    (net (code "12") (name "Net-(LED9-DI)") (class "Default")
      (node (ref "LED9") (pin "4") (pinfunction "DI_4") (pintype "bidirectional"))
      (node (ref "PAD9") (pin "1") (pinfunction "P_1") (pintype "passive"))
    )
    (net (code "13") (name "Net-(LED10-DI)") (class "Default")
      (node (ref "LED10") (pin "4") (pinfunction "DI_4") (pintype "bidirectional"))
      (node (ref "LED9") (pin "2") (pinfunction "DO_2") (pintype "bidirectional"))
    )
    (net (code "14") (name "Net-(LED10-DO)") (class "Default")
      (node (ref "LED10") (pin "2") (pinfunction "DO_2") (pintype "bidirectional"))
      (node (ref "LED11") (pin "4") (pinfunction "DI_4") (pintype "bidirectional"))
    )
    (net (code "15") (name "Net-(LED11-DO)") (class "Default")
      (node (ref "LED11") (pin "2") (pinfunction "DO_2") (pintype "bidirectional"))
      (node (ref "LED12") (pin "4") (pinfunction "DI_4") (pintype "bidirectional"))
    )
    (net (code "16") (name "Net-(LED12-DO)") (class "Default")
      (node (ref "LED12") (pin "2") (pinfunction "DO_2") (pintype "bidirectional"))
      (node (ref "LED13") (pin "4") (pinfunction "DI_4") (pintype "bidirectional"))
    )
    (net (code "17") (name "Net-(LED13-DO)") (class "Default")
      (node (ref "LED13") (pin "2") (pinfunction "DO_2") (pintype "bidirectional"))
      (node (ref "LED14") (pin "4") (pinfunction "DI_4") (pintype "bidirectional"))
    )
    (net (code "18") (name "Net-(LED14-DO)") (class "Default")
      (node (ref "LED14") (pin "2") (pinfunction "DO_2") (pintype "bidirectional"))
      (node (ref "LED15") (pin "4") (pinfunction "DI_4") (pintype "bidirectional"))
    )
    (net (code "19") (name "Net-(LED15-DO)") (class "Default")
      (node (ref "LED15") (pin "2") (pinfunction "DO_2") (pintype "bidirectional"))
      (node (ref "LED16") (pin "4") (pinfunction "DI_4") (pintype "bidirectional"))
    )
    (net (code "20") (name "Net-(LED16-DO)") (class "Default")
      (node (ref "LED16") (pin "2") (pinfunction "DO_2") (pintype "bidirectional"))
      (node (ref "LED17") (pin "4") (pinfunction "DI_4") (pintype "bidirectional"))
    )
    (net (code "21") (name "Net-(LED17-DO)") (class "Default")
      (node (ref "LED17") (pin "2") (pinfunction "DO_2") (pintype "bidirectional"))
      (node (ref "LED18") (pin "4") (pinfunction "DI_4") (pintype "bidirectional"))
    )
    (net (code "22") (name "Net-(LED18-DO)") (class "Default")
      (node (ref "LED18") (pin "2") (pinfunction "DO_2") (pintype "bidirectional"))
      (node (ref "LED19") (pin "4") (pinfunction "DI_4") (pintype "bidirectional"))
    )
    (net (code "23") (name "Net-(LED19-DO)") (class "Default")
      (node (ref "LED19") (pin "2") (pinfunction "DO_2") (pintype "bidirectional"))
      (node (ref "LED20") (pin "4") (pinfunction "DI_4") (pintype "bidirectional"))
    )
    (net (code "24") (name "Net-(LED20-DO)") (class "Default")
      (node (ref "LED20") (pin "2") (pinfunction "DO_2") (pintype "bidirectional"))
      (node (ref "LED21") (pin "4") (pinfunction "DI_4") (pintype "bidirectional"))
    )
    (net (code "25") (name "Net-(LED21-DO)") (class "Default")
      (node (ref "LED21") (pin "2") (pinfunction "DO_2") (pintype "bidirectional"))
      (node (ref "LED22") (pin "4") (pinfunction "DI_4") (pintype "bidirectional"))
    )
    (net (code "26") (name "Net-(LED22-DO)") (class "Default")
      (node (ref "LED22") (pin "2") (pinfunction "DO_2") (pintype "bidirectional"))
      (node (ref "LED23") (pin "4") (pinfunction "DI_4") (pintype "bidirectional"))
    )
    (net (code "27") (name "Net-(LED23-DO)") (class "Default")
      (node (ref "LED23") (pin "2") (pinfunction "DO_2") (pintype "bidirectional"))
      (node (ref "LED24") (pin "4") (pinfunction "DI_4") (pintype "bidirectional"))
    )
    (net (code "28") (name "Net-(LED24-DO)") (class "Default")
      (node (ref "LED24") (pin "2") (pinfunction "DO_2") (pintype "bidirectional"))
      (node (ref "PAD12") (pin "1") (pinfunction "P_1") (pintype "passive"))
    )
    (net (code "29") (name "Net-(LED25-DI)") (class "Default")
      (node (ref "LED25") (pin "4") (pinfunction "DI_4") (pintype "bidirectional"))
      (node (ref "PAD13") (pin "1") (pinfunction "P_1") (pintype "passive"))
    )
    (net (code "30") (name "Net-(LED25-DO)") (class "Default")
      (node (ref "LED25") (pin "2") (pinfunction "DO_2") (pintype "bidirectional"))
      (node (ref "LED26") (pin "4") (pinfunction "DI_4") (pintype "bidirectional"))
    )
    (net (code "31") (name "Net-(LED26-DO)") (class "Default")
      (node (ref "LED26") (pin "2") (pinfunction "DO_2") (pintype "bidirectional"))
      (node (ref "LED27") (pin "4") (pinfunction "DI_4") (pintype "bidirectional"))
    )
    (net (code "32") (name "Net-(LED27-DO)") (class "Default")
      (node (ref "LED27") (pin "2") (pinfunction "DO_2") (pintype "bidirectional"))
      (node (ref "LED28") (pin "4") (pinfunction "DI_4") (pintype "bidirectional"))
    )
    (net (code "33") (name "Net-(LED28-DO)") (class "Default")
      (node (ref "LED28") (pin "2") (pinfunction "DO_2") (pintype "bidirectional"))
      (node (ref "LED29") (pin "4") (pinfunction "DI_4") (pintype "bidirectional"))
    )
    (net (code "34") (name "Net-(LED29-DO)") (class "Default")
      (node (ref "LED29") (pin "2") (pinfunction "DO_2") (pintype "bidirectional"))
      (node (ref "LED30") (pin "4") (pinfunction "DI_4") (pintype "bidirectional"))
    )
    (net (code "35") (name "Net-(LED30-DO)") (class "Default")
      (node (ref "LED30") (pin "2") (pinfunction "DO_2") (pintype "bidirectional"))
      (node (ref "LED31") (pin "4") (pinfunction "DI_4") (pintype "bidirectional"))
    )
    (net (code "36") (name "Net-(LED31-DO)") (class "Default")
      (node (ref "LED31") (pin "2") (pinfunction "DO_2") (pintype "bidirectional"))
      (node (ref "LED32") (pin "4") (pinfunction "DI_4") (pintype "bidirectional"))
    )
    (net (code "37") (name "Net-(LED32-DO)") (class "Default")
      (node (ref "LED32") (pin "2") (pinfunction "DO_2") (pintype "bidirectional"))
      (node (ref "LED33") (pin "4") (pinfunction "DI_4") (pintype "bidirectional"))
    )
    (net (code "38") (name "Net-(LED33-DO)") (class "Default")
      (node (ref "LED33") (pin "2") (pinfunction "DO_2") (pintype "bidirectional"))
      (node (ref "LED34") (pin "4") (pinfunction "DI_4") (pintype "bidirectional"))
    )
    (net (code "39") (name "Net-(LED34-DO)") (class "Default")
      (node (ref "LED34") (pin "2") (pinfunction "DO_2") (pintype "bidirectional"))
      (node (ref "LED35") (pin "4") (pinfunction "DI_4") (pintype "bidirectional"))
    )
    (net (code "40") (name "Net-(LED35-DO)") (class "Default")
      (node (ref "LED35") (pin "2") (pinfunction "DO_2") (pintype "bidirectional"))
      (node (ref "LED36") (pin "4") (pinfunction "DI_4") (pintype "bidirectional"))
    )
    (net (code "41") (name "Net-(LED36-DO)") (class "Default")
      (node (ref "LED36") (pin "2") (pinfunction "DO_2") (pintype "bidirectional"))
      (node (ref "LED37") (pin "4") (pinfunction "DI_4") (pintype "bidirectional"))
    )
    (net (code "42") (name "Net-(LED37-DO)") (class "Default")
      (node (ref "LED37") (pin "2") (pinfunction "DO_2") (pintype "bidirectional"))
      (node (ref "LED38") (pin "4") (pinfunction "DI_4") (pintype "bidirectional"))
    )
    (net (code "43") (name "Net-(LED38-DO)") (class "Default")
      (node (ref "LED38") (pin "2") (pinfunction "DO_2") (pintype "bidirectional"))
      (node (ref "LED39") (pin "4") (pinfunction "DI_4") (pintype "bidirectional"))
    )
    (net (code "44") (name "Net-(LED39-DO)") (class "Default")
      (node (ref "LED39") (pin "2") (pinfunction "DO_2") (pintype "bidirectional"))
      (node (ref "LED40") (pin "4") (pinfunction "DI_4") (pintype "bidirectional"))
    )
    (net (code "45") (name "Net-(LED40-DO)") (class "Default")
      (node (ref "LED40") (pin "2") (pinfunction "DO_2") (pintype "bidirectional"))
      (node (ref "LED41") (pin "4") (pinfunction "DI_4") (pintype "bidirectional"))
    )
    (net (code "46") (name "Net-(LED41-DO)") (class "Default")
      (node (ref "LED41") (pin "2") (pinfunction "DO_2") (pintype "bidirectional"))
      (node (ref "LED42") (pin "4") (pinfunction "DI_4") (pintype "bidirectional"))
    )
    (net (code "47") (name "Net-(LED42-DO)") (class "Default")
      (node (ref "LED42") (pin "2") (pinfunction "DO_2") (pintype "bidirectional"))
      (node (ref "LED43") (pin "4") (pinfunction "DI_4") (pintype "bidirectional"))
    )
    (net (code "48") (name "Net-(LED43-DO)") (class "Default")
      (node (ref "LED43") (pin "2") (pinfunction "DO_2") (pintype "bidirectional"))
      (node (ref "LED44") (pin "4") (pinfunction "DI_4") (pintype "bidirectional"))
    )
    (net (code "49") (name "Net-(LED44-DO)") (class "Default")
      (node (ref "LED44") (pin "2") (pinfunction "DO_2") (pintype "bidirectional"))
      (node (ref "LED45") (pin "4") (pinfunction "DI_4") (pintype "bidirectional"))
    )
    (net (code "50") (name "Net-(LED45-DO)") (class "Default")
      (node (ref "LED45") (pin "2") (pinfunction "DO_2") (pintype "bidirectional"))
      (node (ref "LED46") (pin "4") (pinfunction "DI_4") (pintype "bidirectional"))
    )
    (net (code "51") (name "Net-(LED46-DO)") (class "Default")
      (node (ref "LED46") (pin "2") (pinfunction "DO_2") (pintype "bidirectional"))
      (node (ref "LED47") (pin "4") (pinfunction "DI_4") (pintype "bidirectional"))
    )
    (net (code "52") (name "Net-(LED47-DO)") (class "Default")
      (node (ref "LED47") (pin "2") (pinfunction "DO_2") (pintype "bidirectional"))
      (node (ref "LED48") (pin "4") (pinfunction "DI_4") (pintype "bidirectional"))
    )
    (net (code "53") (name "Net-(LED48-DO)") (class "Default")
      (node (ref "LED48") (pin "2") (pinfunction "DO_2") (pintype "bidirectional"))
      (node (ref "PAD16") (pin "1") (pinfunction "P_1") (pintype "passive"))
    )
    (net (code "54") (name "Net-(LED49-DI)") (class "Default")
      (node (ref "LED49") (pin "4") (pinfunction "DI_4") (pintype "bidirectional"))
      (node (ref "PAD5") (pin "1") (pinfunction "P_1") (pintype "passive"))
    )
    (net (code "55") (name "Net-(LED49-DO)") (class "Default")
      (node (ref "LED49") (pin "2") (pinfunction "DO_2") (pintype "bidirectional"))
      (node (ref "LED50") (pin "4") (pinfunction "DI_4") (pintype "bidirectional"))
    )
    (net (code "56") (name "Net-(LED50-DO)") (class "Default")
      (node (ref "LED50") (pin "2") (pinfunction "DO_2") (pintype "bidirectional"))
      (node (ref "LED51") (pin "4") (pinfunction "DI_4") (pintype "bidirectional"))
    )
    (net (code "57") (name "Net-(LED51-DO)") (class "Default")
      (node (ref "LED51") (pin "2") (pinfunction "DO_2") (pintype "bidirectional"))
      (node (ref "LED52") (pin "4") (pinfunction "DI_4") (pintype "bidirectional"))
    )
    (net (code "58") (name "Net-(LED52-DO)") (class "Default")
      (node (ref "LED52") (pin "2") (pinfunction "DO_2") (pintype "bidirectional"))
      (node (ref "LED53") (pin "4") (pinfunction "DI_4") (pintype "bidirectional"))
    )
    (net (code "59") (name "Net-(LED53-DO)") (class "Default")
      (node (ref "LED53") (pin "2") (pinfunction "DO_2") (pintype "bidirectional"))
      (node (ref "LED54") (pin "4") (pinfunction "DI_4") (pintype "bidirectional"))
    )
    (net (code "60") (name "Net-(LED54-DO)") (class "Default")
      (node (ref "LED54") (pin "2") (pinfunction "DO_2") (pintype "bidirectional"))
      (node (ref "LED55") (pin "4") (pinfunction "DI_4") (pintype "bidirectional"))
    )
    (net (code "61") (name "Net-(LED55-DO)") (class "Default")
      (node (ref "LED55") (pin "2") (pinfunction "DO_2") (pintype "bidirectional"))
      (node (ref "LED56") (pin "4") (pinfunction "DI_4") (pintype "bidirectional"))
    )
    (net (code "62") (name "Net-(LED56-DO)") (class "Default")
      (node (ref "LED56") (pin "2") (pinfunction "DO_2") (pintype "bidirectional"))
      (node (ref "LED57") (pin "4") (pinfunction "DI_4") (pintype "bidirectional"))
    )
    (net (code "63") (name "Net-(LED57-DO)") (class "Default")
      (node (ref "LED57") (pin "2") (pinfunction "DO_2") (pintype "bidirectional"))
      (node (ref "LED58") (pin "4") (pinfunction "DI_4") (pintype "bidirectional"))
    )
    (net (code "64") (name "Net-(LED58-DO)") (class "Default")
      (node (ref "LED58") (pin "2") (pinfunction "DO_2") (pintype "bidirectional"))
      (node (ref "LED59") (pin "4") (pinfunction "DI_4") (pintype "bidirectional"))
    )
    (net (code "65") (name "Net-(LED59-DO)") (class "Default")
      (node (ref "LED59") (pin "2") (pinfunction "DO_2") (pintype "bidirectional"))
      (node (ref "LED60") (pin "4") (pinfunction "DI_4") (pintype "bidirectional"))
    )
    (net (code "66") (name "Net-(LED60-DO)") (class "Default")
      (node (ref "LED60") (pin "2") (pinfunction "DO_2") (pintype "bidirectional"))
      (node (ref "PAD8") (pin "1") (pinfunction "P_1") (pintype "passive"))
    )
    (net (code "67") (name "Net-(LED61-DI)") (class "Default")
      (node (ref "LED61") (pin "4") (pinfunction "DI_4") (pintype "bidirectional"))
      (node (ref "PAD17") (pin "1") (pinfunction "P_1") (pintype "passive"))
    )
    (net (code "68") (name "Net-(LED61-DO)") (class "Default")
      (node (ref "LED61") (pin "2") (pinfunction "DO_2") (pintype "bidirectional"))
      (node (ref "LED62") (pin "4") (pinfunction "DI_4") (pintype "bidirectional"))
    )
    (net (code "69") (name "Net-(LED62-DO)") (class "Default")
      (node (ref "LED62") (pin "2") (pinfunction "DO_2") (pintype "bidirectional"))
      (node (ref "LED63") (pin "4") (pinfunction "DI_4") (pintype "bidirectional"))
    )
    (net (code "70") (name "Net-(LED63-DO)") (class "Default")
      (node (ref "LED63") (pin "2") (pinfunction "DO_2") (pintype "bidirectional"))
      (node (ref "LED64") (pin "4") (pinfunction "DI_4") (pintype "bidirectional"))
    )
    (net (code "71") (name "Net-(LED64-DO)") (class "Default")
      (node (ref "LED64") (pin "2") (pinfunction "DO_2") (pintype "bidirectional"))
      (node (ref "LED65") (pin "4") (pinfunction "DI_4") (pintype "bidirectional"))
    )
    (net (code "72") (name "Net-(LED65-DO)") (class "Default")
      (node (ref "LED65") (pin "2") (pinfunction "DO_2") (pintype "bidirectional"))
      (node (ref "LED66") (pin "4") (pinfunction "DI_4") (pintype "bidirectional"))
    )
    (net (code "73") (name "Net-(LED66-DO)") (class "Default")
      (node (ref "LED66") (pin "2") (pinfunction "DO_2") (pintype "bidirectional"))
      (node (ref "LED67") (pin "4") (pinfunction "DI_4") (pintype "bidirectional"))
    )
    (net (code "74") (name "Net-(LED67-DO)") (class "Default")
      (node (ref "LED67") (pin "2") (pinfunction "DO_2") (pintype "bidirectional"))
      (node (ref "LED68") (pin "4") (pinfunction "DI_4") (pintype "bidirectional"))
    )
    (net (code "75") (name "Net-(LED68-DO)") (class "Default")
      (node (ref "LED68") (pin "2") (pinfunction "DO_2") (pintype "bidirectional"))
      (node (ref "LED69") (pin "4") (pinfunction "DI_4") (pintype "bidirectional"))
    )
    (net (code "76") (name "Net-(LED69-DO)") (class "Default")
      (node (ref "LED69") (pin "2") (pinfunction "DO_2") (pintype "bidirectional"))
      (node (ref "LED70") (pin "4") (pinfunction "DI_4") (pintype "bidirectional"))
    )
    (net (code "77") (name "Net-(LED70-DO)") (class "Default")
      (node (ref "LED70") (pin "2") (pinfunction "DO_2") (pintype "bidirectional"))
      (node (ref "LED71") (pin "4") (pinfunction "DI_4") (pintype "bidirectional"))
    )
    (net (code "78") (name "Net-(LED71-DO)") (class "Default")
      (node (ref "LED71") (pin "2") (pinfunction "DO_2") (pintype "bidirectional"))
      (node (ref "LED72") (pin "4") (pinfunction "DI_4") (pintype "bidirectional"))
    )
    (net (code "79") (name "Net-(LED72-DO)") (class "Default")
      (node (ref "LED72") (pin "2") (pinfunction "DO_2") (pintype "bidirectional"))
      (node (ref "LED73") (pin "4") (pinfunction "DI_4") (pintype "bidirectional"))
    )
    (net (code "80") (name "Net-(LED73-DO)") (class "Default")
      (node (ref "LED73") (pin "2") (pinfunction "DO_2") (pintype "bidirectional"))
      (node (ref "LED74") (pin "4") (pinfunction "DI_4") (pintype "bidirectional"))
    )
    (net (code "81") (name "Net-(LED74-DO)") (class "Default")
      (node (ref "LED74") (pin "2") (pinfunction "DO_2") (pintype "bidirectional"))
      (node (ref "LED75") (pin "4") (pinfunction "DI_4") (pintype "bidirectional"))
    )
    (net (code "82") (name "Net-(LED75-DO)") (class "Default")
      (node (ref "LED75") (pin "2") (pinfunction "DO_2") (pintype "bidirectional"))
      (node (ref "LED76") (pin "4") (pinfunction "DI_4") (pintype "bidirectional"))
    )
    (net (code "83") (name "Net-(LED76-DO)") (class "Default")
      (node (ref "LED76") (pin "2") (pinfunction "DO_2") (pintype "bidirectional"))
      (node (ref "LED77") (pin "4") (pinfunction "DI_4") (pintype "bidirectional"))
    )
    (net (code "84") (name "Net-(LED77-DO)") (class "Default")
      (node (ref "LED77") (pin "2") (pinfunction "DO_2") (pintype "bidirectional"))
      (node (ref "LED78") (pin "4") (pinfunction "DI_4") (pintype "bidirectional"))
    )
    (net (code "85") (name "Net-(LED78-DO)") (class "Default")
      (node (ref "LED78") (pin "2") (pinfunction "DO_2") (pintype "bidirectional"))
      (node (ref "LED79") (pin "4") (pinfunction "DI_4") (pintype "bidirectional"))
    )
    (net (code "86") (name "Net-(LED79-DO)") (class "Default")
      (node (ref "LED79") (pin "2") (pinfunction "DO_2") (pintype "bidirectional"))
      (node (ref "LED80") (pin "4") (pinfunction "DI_4") (pintype "bidirectional"))
    )
    (net (code "87") (name "Net-(LED80-DO)") (class "Default")
      (node (ref "LED80") (pin "2") (pinfunction "DO_2") (pintype "bidirectional"))
      (node (ref "LED81") (pin "4") (pinfunction "DI_4") (pintype "bidirectional"))
    )
    (net (code "88") (name "Net-(LED81-DO)") (class "Default")
      (node (ref "LED81") (pin "2") (pinfunction "DO_2") (pintype "bidirectional"))
      (node (ref "LED82") (pin "4") (pinfunction "DI_4") (pintype "bidirectional"))
    )
    (net (code "89") (name "Net-(LED82-DO)") (class "Default")
      (node (ref "LED82") (pin "2") (pinfunction "DO_2") (pintype "bidirectional"))
      (node (ref "LED83") (pin "4") (pinfunction "DI_4") (pintype "bidirectional"))
    )
    (net (code "90") (name "Net-(LED83-DO)") (class "Default")
      (node (ref "LED83") (pin "2") (pinfunction "DO_2") (pintype "bidirectional"))
      (node (ref "LED84") (pin "4") (pinfunction "DI_4") (pintype "bidirectional"))
    )
    (net (code "91") (name "Net-(LED84-DO)") (class "Default")
      (node (ref "LED84") (pin "2") (pinfunction "DO_2") (pintype "bidirectional"))
      (node (ref "LED85") (pin "4") (pinfunction "DI_4") (pintype "bidirectional"))
    )
    (net (code "92") (name "Net-(LED85-DO)") (class "Default")
      (node (ref "LED85") (pin "2") (pinfunction "DO_2") (pintype "bidirectional"))
      (node (ref "LED86") (pin "4") (pinfunction "DI_4") (pintype "bidirectional"))
    )
    (net (code "93") (name "Net-(LED86-DO)") (class "Default")
      (node (ref "LED86") (pin "2") (pinfunction "DO_2") (pintype "bidirectional"))
      (node (ref "LED87") (pin "4") (pinfunction "DI_4") (pintype "bidirectional"))
    )
    (net (code "94") (name "Net-(LED87-DO)") (class "Default")
      (node (ref "LED87") (pin "2") (pinfunction "DO_2") (pintype "bidirectional"))
      (node (ref "LED88") (pin "4") (pinfunction "DI_4") (pintype "bidirectional"))
    )
    (net (code "95") (name "Net-(LED88-DO)") (class "Default")
      (node (ref "LED88") (pin "2") (pinfunction "DO_2") (pintype "bidirectional"))
      (node (ref "LED89") (pin "4") (pinfunction "DI_4") (pintype "bidirectional"))
    )
    (net (code "96") (name "Net-(LED89-DO)") (class "Default")
      (node (ref "LED89") (pin "2") (pinfunction "DO_2") (pintype "bidirectional"))
      (node (ref "LED90") (pin "4") (pinfunction "DI_4") (pintype "bidirectional"))
    )
    (net (code "97") (name "Net-(LED90-DO)") (class "Default")
      (node (ref "LED90") (pin "2") (pinfunction "DO_2") (pintype "bidirectional"))
      (node (ref "LED91") (pin "4") (pinfunction "DI_4") (pintype "bidirectional"))
    )
    (net (code "98") (name "Net-(LED91-DO)") (class "Default")
      (node (ref "LED91") (pin "2") (pinfunction "DO_2") (pintype "bidirectional"))
      (node (ref "LED92") (pin "4") (pinfunction "DI_4") (pintype "bidirectional"))
    )
    (net (code "99") (name "Net-(LED92-DO)") (class "Default")
      (node (ref "LED92") (pin "2") (pinfunction "DO_2") (pintype "bidirectional"))
      (node (ref "PAD20") (pin "1") (pinfunction "P_1") (pintype "passive"))
    )
    (net (code "100") (name "Net-(LED93-DI)") (class "Default")
      (node (ref "LED93") (pin "4") (pinfunction "DI_4") (pintype "bidirectional"))
      (node (ref "PAD25") (pin "1") (pinfunction "P_1") (pintype "passive"))
    )
    (net (code "101") (name "Net-(LED93-DO)") (class "Default")
      (node (ref "LED93") (pin "2") (pinfunction "DO_2") (pintype "bidirectional"))
      (node (ref "LED94") (pin "4") (pinfunction "DI_4") (pintype "bidirectional"))
    )
    (net (code "102") (name "Net-(LED94-DO)") (class "Default")
      (node (ref "LED94") (pin "2") (pinfunction "DO_2") (pintype "bidirectional"))
      (node (ref "LED95") (pin "4") (pinfunction "DI_4") (pintype "bidirectional"))
    )
    (net (code "103") (name "Net-(LED95-DO)") (class "Default")
      (node (ref "LED95") (pin "2") (pinfunction "DO_2") (pintype "bidirectional"))
      (node (ref "LED96") (pin "4") (pinfunction "DI_4") (pintype "bidirectional"))
    )
    (net (code "104") (name "Net-(LED96-DO)") (class "Default")
      (node (ref "LED96") (pin "2") (pinfunction "DO_2") (pintype "bidirectional"))
      (node (ref "LED97") (pin "4") (pinfunction "DI_4") (pintype "bidirectional"))
    )
    (net (code "105") (name "Net-(LED97-DO)") (class "Default")
      (node (ref "LED97") (pin "2") (pinfunction "DO_2") (pintype "bidirectional"))
      (node (ref "LED98") (pin "4") (pinfunction "DI_4") (pintype "bidirectional"))
    )
    (net (code "106") (name "Net-(LED98-DO)") (class "Default")
      (node (ref "LED98") (pin "2") (pinfunction "DO_2") (pintype "bidirectional"))
      (node (ref "LED99") (pin "4") (pinfunction "DI_4") (pintype "bidirectional"))
    )
    (net (code "107") (name "Net-(LED100-DI)") (class "Default")
      (node (ref "LED100") (pin "4") (pinfunction "DI_4") (pintype "bidirectional"))
      (node (ref "LED99") (pin "2") (pinfunction "DO_2") (pintype "bidirectional"))
    )
    (net (code "108") (name "Net-(LED100-DO)") (class "Default")
      (node (ref "LED100") (pin "2") (pinfunction "DO_2") (pintype "bidirectional"))
      (node (ref "LED101") (pin "4") (pinfunction "DI_4") (pintype "bidirectional"))
    )
    (net (code "109") (name "Net-(LED101-DO)") (class "Default")
      (node (ref "LED101") (pin "2") (pinfunction "DO_2") (pintype "bidirectional"))
      (node (ref "LED102") (pin "4") (pinfunction "DI_4") (pintype "bidirectional"))
    )
    (net (code "110") (name "Net-(LED102-DO)") (class "Default")
      (node (ref "LED102") (pin "2") (pinfunction "DO_2") (pintype "bidirectional"))
      (node (ref "LED103") (pin "4") (pinfunction "DI_4") (pintype "bidirectional"))
    )
    (net (code "111") (name "Net-(LED103-DO)") (class "Default")
      (node (ref "LED103") (pin "2") (pinfunction "DO_2") (pintype "bidirectional"))
      (node (ref "LED104") (pin "4") (pinfunction "DI_4") (pintype "bidirectional"))
    )
    (net (code "112") (name "Net-(LED104-DO)") (class "Default")
      (node (ref "LED104") (pin "2") (pinfunction "DO_2") (pintype "bidirectional"))
      (node (ref "LED105") (pin "4") (pinfunction "DI_4") (pintype "bidirectional"))
    )
    (net (code "113") (name "Net-(LED105-DO)") (class "Default")
      (node (ref "LED105") (pin "2") (pinfunction "DO_2") (pintype "bidirectional"))
      (node (ref "LED106") (pin "4") (pinfunction "DI_4") (pintype "bidirectional"))
    )
    (net (code "114") (name "Net-(LED106-DO)") (class "Default")
      (node (ref "LED106") (pin "2") (pinfunction "DO_2") (pintype "bidirectional"))
      (node (ref "LED107") (pin "4") (pinfunction "DI_4") (pintype "bidirectional"))
    )
    (net (code "115") (name "Net-(LED107-DO)") (class "Default")
      (node (ref "LED107") (pin "2") (pinfunction "DO_2") (pintype "bidirectional"))
      (node (ref "LED108") (pin "4") (pinfunction "DI_4") (pintype "bidirectional"))
    )
    (net (code "116") (name "Net-(LED108-DO)") (class "Default")
      (node (ref "LED108") (pin "2") (pinfunction "DO_2") (pintype "bidirectional"))
      (node (ref "LED109") (pin "4") (pinfunction "DI_4") (pintype "bidirectional"))
    )
    (net (code "117") (name "Net-(LED109-DO)") (class "Default")
      (node (ref "LED109") (pin "2") (pinfunction "DO_2") (pintype "bidirectional"))
      (node (ref "LED110") (pin "4") (pinfunction "DI_4") (pintype "bidirectional"))
    )
    (net (code "118") (name "Net-(LED110-DO)") (class "Default")
      (node (ref "LED110") (pin "2") (pinfunction "DO_2") (pintype "bidirectional"))
      (node (ref "LED111") (pin "4") (pinfunction "DI_4") (pintype "bidirectional"))
    )
    (net (code "119") (name "Net-(LED111-DO)") (class "Default")
      (node (ref "LED111") (pin "2") (pinfunction "DO_2") (pintype "bidirectional"))
      (node (ref "LED112") (pin "4") (pinfunction "DI_4") (pintype "bidirectional"))
    )
    (net (code "120") (name "Net-(LED112-DO)") (class "Default")
      (node (ref "LED112") (pin "2") (pinfunction "DO_2") (pintype "bidirectional"))
      (node (ref "LED113") (pin "4") (pinfunction "DI_4") (pintype "bidirectional"))
    )
    (net (code "121") (name "Net-(LED113-DO)") (class "Default")
      (node (ref "LED113") (pin "2") (pinfunction "DO_2") (pintype "bidirectional"))
      (node (ref "LED114") (pin "4") (pinfunction "DI_4") (pintype "bidirectional"))
    )
    (net (code "122") (name "Net-(LED114-DO)") (class "Default")
      (node (ref "LED114") (pin "2") (pinfunction "DO_2") (pintype "bidirectional"))
      (node (ref "LED115") (pin "4") (pinfunction "DI_4") (pintype "bidirectional"))
    )
    (net (code "123") (name "Net-(LED115-DO)") (class "Default")
      (node (ref "LED115") (pin "2") (pinfunction "DO_2") (pintype "bidirectional"))
      (node (ref "LED116") (pin "4") (pinfunction "DI_4") (pintype "bidirectional"))
    )
    (net (code "124") (name "Net-(LED116-DO)") (class "Default")
      (node (ref "LED116") (pin "2") (pinfunction "DO_2") (pintype "bidirectional"))
      (node (ref "LED117") (pin "4") (pinfunction "DI_4") (pintype "bidirectional"))
    )
    (net (code "125") (name "Net-(LED117-DO)") (class "Default")
      (node (ref "LED117") (pin "2") (pinfunction "DO_2") (pintype "bidirectional"))
      (node (ref "LED118") (pin "4") (pinfunction "DI_4") (pintype "bidirectional"))
    )
    (net (code "126") (name "Net-(LED118-DO)") (class "Default")
      (node (ref "LED118") (pin "2") (pinfunction "DO_2") (pintype "bidirectional"))
      (node (ref "LED119") (pin "4") (pinfunction "DI_4") (pintype "bidirectional"))
    )
    (net (code "127") (name "Net-(LED119-DO)") (class "Default")
      (node (ref "LED119") (pin "2") (pinfunction "DO_2") (pintype "bidirectional"))
      (node (ref "LED120") (pin "4") (pinfunction "DI_4") (pintype "bidirectional"))
    )
    (net (code "128") (name "Net-(LED120-DO)") (class "Default")
      (node (ref "LED120") (pin "2") (pinfunction "DO_2") (pintype "bidirectional"))
      (node (ref "LED121") (pin "4") (pinfunction "DI_4") (pintype "bidirectional"))
    )
    (net (code "129") (name "Net-(LED121-DO)") (class "Default")
      (node (ref "LED121") (pin "2") (pinfunction "DO_2") (pintype "bidirectional"))
      (node (ref "LED122") (pin "4") (pinfunction "DI_4") (pintype "bidirectional"))
    )
    (net (code "130") (name "Net-(LED122-DO)") (class "Default")
      (node (ref "LED122") (pin "2") (pinfunction "DO_2") (pintype "bidirectional"))
      (node (ref "LED123") (pin "4") (pinfunction "DI_4") (pintype "bidirectional"))
    )
    (net (code "131") (name "Net-(LED123-DO)") (class "Default")
      (node (ref "LED123") (pin "2") (pinfunction "DO_2") (pintype "bidirectional"))
      (node (ref "LED124") (pin "4") (pinfunction "DI_4") (pintype "bidirectional"))
    )
    (net (code "132") (name "Net-(LED124-DO)") (class "Default")
      (node (ref "LED124") (pin "2") (pinfunction "DO_2") (pintype "bidirectional"))
      (node (ref "LED125") (pin "4") (pinfunction "DI_4") (pintype "bidirectional"))
    )
    (net (code "133") (name "Net-(LED125-DO)") (class "Default")
      (node (ref "LED125") (pin "2") (pinfunction "DO_2") (pintype "bidirectional"))
      (node (ref "LED126") (pin "4") (pinfunction "DI_4") (pintype "bidirectional"))
    )
    (net (code "134") (name "Net-(LED126-DO)") (class "Default")
      (node (ref "LED126") (pin "2") (pinfunction "DO_2") (pintype "bidirectional"))
      (node (ref "LED127") (pin "4") (pinfunction "DI_4") (pintype "bidirectional"))
    )
    (net (code "135") (name "Net-(LED127-DO)") (class "Default")
      (node (ref "LED127") (pin "2") (pinfunction "DO_2") (pintype "bidirectional"))
      (node (ref "LED128") (pin "4") (pinfunction "DI_4") (pintype "bidirectional"))
    )
    (net (code "136") (name "Net-(LED128-DO)") (class "Default")
      (node (ref "LED128") (pin "2") (pinfunction "DO_2") (pintype "bidirectional"))
      (node (ref "LED129") (pin "4") (pinfunction "DI_4") (pintype "bidirectional"))
    )
    (net (code "137") (name "Net-(LED129-DO)") (class "Default")
      (node (ref "LED129") (pin "2") (pinfunction "DO_2") (pintype "bidirectional"))
      (node (ref "LED130") (pin "4") (pinfunction "DI_4") (pintype "bidirectional"))
    )
    (net (code "138") (name "Net-(LED130-DO)") (class "Default")
      (node (ref "LED130") (pin "2") (pinfunction "DO_2") (pintype "bidirectional"))
      (node (ref "LED131") (pin "4") (pinfunction "DI_4") (pintype "bidirectional"))
    )
    (net (code "139") (name "Net-(LED131-DO)") (class "Default")
      (node (ref "LED131") (pin "2") (pinfunction "DO_2") (pintype "bidirectional"))
      (node (ref "LED132") (pin "4") (pinfunction "DI_4") (pintype "bidirectional"))
    )
    (net (code "140") (name "Net-(LED132-DO)") (class "Default")
      (node (ref "LED132") (pin "2") (pinfunction "DO_2") (pintype "bidirectional"))
      (node (ref "PAD28") (pin "1") (pinfunction "P_1") (pintype "passive"))
    )
    (net (code "141") (name "Net-(LED133-DI)") (class "Default")
      (node (ref "LED133") (pin "4") (pinfunction "DI_4") (pintype "bidirectional"))
      (node (ref "PAD21") (pin "1") (pinfunction "P_1") (pintype "passive"))
    )
    (net (code "142") (name "Net-(LED133-DO)") (class "Default")
      (node (ref "LED133") (pin "2") (pinfunction "DO_2") (pintype "bidirectional"))
      (node (ref "LED134") (pin "4") (pinfunction "DI_4") (pintype "bidirectional"))
    )
    (net (code "143") (name "Net-(LED134-DO)") (class "Default")
      (node (ref "LED134") (pin "2") (pinfunction "DO_2") (pintype "bidirectional"))
      (node (ref "LED135") (pin "4") (pinfunction "DI_4") (pintype "bidirectional"))
    )
    (net (code "144") (name "Net-(LED135-DO)") (class "Default")
      (node (ref "LED135") (pin "2") (pinfunction "DO_2") (pintype "bidirectional"))
      (node (ref "LED136") (pin "4") (pinfunction "DI_4") (pintype "bidirectional"))
    )
    (net (code "145") (name "Net-(LED136-DO)") (class "Default")
      (node (ref "LED136") (pin "2") (pinfunction "DO_2") (pintype "bidirectional"))
      (node (ref "LED137") (pin "4") (pinfunction "DI_4") (pintype "bidirectional"))
    )
    (net (code "146") (name "Net-(LED137-DO)") (class "Default")
      (node (ref "LED137") (pin "2") (pinfunction "DO_2") (pintype "bidirectional"))
      (node (ref "LED138") (pin "4") (pinfunction "DI_4") (pintype "bidirectional"))
    )
    (net (code "147") (name "Net-(LED138-DO)") (class "Default")
      (node (ref "LED138") (pin "2") (pinfunction "DO_2") (pintype "bidirectional"))
      (node (ref "LED139") (pin "4") (pinfunction "DI_4") (pintype "bidirectional"))
    )
    (net (code "148") (name "Net-(LED139-DO)") (class "Default")
      (node (ref "LED139") (pin "2") (pinfunction "DO_2") (pintype "bidirectional"))
      (node (ref "LED140") (pin "4") (pinfunction "DI_4") (pintype "bidirectional"))
    )
    (net (code "149") (name "Net-(LED140-DO)") (class "Default")
      (node (ref "LED140") (pin "2") (pinfunction "DO_2") (pintype "bidirectional"))
      (node (ref "LED141") (pin "4") (pinfunction "DI_4") (pintype "bidirectional"))
    )
    (net (code "150") (name "Net-(LED141-DO)") (class "Default")
      (node (ref "LED141") (pin "2") (pinfunction "DO_2") (pintype "bidirectional"))
      (node (ref "LED142") (pin "4") (pinfunction "DI_4") (pintype "bidirectional"))
    )
    (net (code "151") (name "Net-(LED142-DO)") (class "Default")
      (node (ref "LED142") (pin "2") (pinfunction "DO_2") (pintype "bidirectional"))
      (node (ref "LED143") (pin "4") (pinfunction "DI_4") (pintype "bidirectional"))
    )
    (net (code "152") (name "Net-(LED143-DO)") (class "Default")
      (node (ref "LED143") (pin "2") (pinfunction "DO_2") (pintype "bidirectional"))
      (node (ref "LED144") (pin "4") (pinfunction "DI_4") (pintype "bidirectional"))
    )
    (net (code "153") (name "Net-(LED144-DO)") (class "Default")
      (node (ref "LED144") (pin "2") (pinfunction "DO_2") (pintype "bidirectional"))
      (node (ref "LED145") (pin "4") (pinfunction "DI_4") (pintype "bidirectional"))
    )
    (net (code "154") (name "Net-(LED145-DO)") (class "Default")
      (node (ref "LED145") (pin "2") (pinfunction "DO_2") (pintype "bidirectional"))
      (node (ref "LED146") (pin "4") (pinfunction "DI_4") (pintype "bidirectional"))
    )
    (net (code "155") (name "Net-(LED146-DO)") (class "Default")
      (node (ref "LED146") (pin "2") (pinfunction "DO_2") (pintype "bidirectional"))
      (node (ref "LED147") (pin "4") (pinfunction "DI_4") (pintype "bidirectional"))
    )
    (net (code "156") (name "Net-(LED147-DO)") (class "Default")
      (node (ref "LED147") (pin "2") (pinfunction "DO_2") (pintype "bidirectional"))
      (node (ref "LED148") (pin "4") (pinfunction "DI_4") (pintype "bidirectional"))
    )
    (net (code "157") (name "Net-(LED148-DO)") (class "Default")
      (node (ref "LED148") (pin "2") (pinfunction "DO_2") (pintype "bidirectional"))
      (node (ref "LED149") (pin "4") (pinfunction "DI_4") (pintype "bidirectional"))
    )
    (net (code "158") (name "Net-(LED149-DO)") (class "Default")
      (node (ref "LED149") (pin "2") (pinfunction "DO_2") (pintype "bidirectional"))
      (node (ref "LED150") (pin "4") (pinfunction "DI_4") (pintype "bidirectional"))
    )
    (net (code "159") (name "Net-(LED150-DO)") (class "Default")
      (node (ref "LED150") (pin "2") (pinfunction "DO_2") (pintype "bidirectional"))
      (node (ref "LED151") (pin "4") (pinfunction "DI_4") (pintype "bidirectional"))
    )
    (net (code "160") (name "Net-(LED151-DO)") (class "Default")
      (node (ref "LED151") (pin "2") (pinfunction "DO_2") (pintype "bidirectional"))
      (node (ref "LED152") (pin "4") (pinfunction "DI_4") (pintype "bidirectional"))
    )
    (net (code "161") (name "Net-(LED152-DO)") (class "Default")
      (node (ref "LED152") (pin "2") (pinfunction "DO_2") (pintype "bidirectional"))
      (node (ref "LED153") (pin "4") (pinfunction "DI_4") (pintype "bidirectional"))
    )
    (net (code "162") (name "Net-(LED153-DO)") (class "Default")
      (node (ref "LED153") (pin "2") (pinfunction "DO_2") (pintype "bidirectional"))
      (node (ref "LED154") (pin "4") (pinfunction "DI_4") (pintype "bidirectional"))
    )
    (net (code "163") (name "Net-(LED154-DO)") (class "Default")
      (node (ref "LED154") (pin "2") (pinfunction "DO_2") (pintype "bidirectional"))
      (node (ref "LED155") (pin "4") (pinfunction "DI_4") (pintype "bidirectional"))
    )
    (net (code "164") (name "Net-(LED155-DO)") (class "Default")
      (node (ref "LED155") (pin "2") (pinfunction "DO_2") (pintype "bidirectional"))
      (node (ref "LED156") (pin "4") (pinfunction "DI_4") (pintype "bidirectional"))
    )
    (net (code "165") (name "Net-(LED156-DO)") (class "Default")
      (node (ref "LED156") (pin "2") (pinfunction "DO_2") (pintype "bidirectional"))
      (node (ref "LED157") (pin "4") (pinfunction "DI_4") (pintype "bidirectional"))
    )
    (net (code "166") (name "Net-(LED157-DO)") (class "Default")
      (node (ref "LED157") (pin "2") (pinfunction "DO_2") (pintype "bidirectional"))
      (node (ref "LED158") (pin "4") (pinfunction "DI_4") (pintype "bidirectional"))
    )
    (net (code "167") (name "Net-(LED158-DO)") (class "Default")
      (node (ref "LED158") (pin "2") (pinfunction "DO_2") (pintype "bidirectional"))
      (node (ref "LED159") (pin "4") (pinfunction "DI_4") (pintype "bidirectional"))
    )
    (net (code "168") (name "Net-(LED159-DO)") (class "Default")
      (node (ref "LED159") (pin "2") (pinfunction "DO_2") (pintype "bidirectional"))
      (node (ref "LED160") (pin "4") (pinfunction "DI_4") (pintype "bidirectional"))
    )
    (net (code "169") (name "Net-(LED160-DO)") (class "Default")
      (node (ref "LED160") (pin "2") (pinfunction "DO_2") (pintype "bidirectional"))
      (node (ref "LED161") (pin "4") (pinfunction "DI_4") (pintype "bidirectional"))
    )
    (net (code "170") (name "Net-(LED161-DO)") (class "Default")
      (node (ref "LED161") (pin "2") (pinfunction "DO_2") (pintype "bidirectional"))
      (node (ref "LED162") (pin "4") (pinfunction "DI_4") (pintype "bidirectional"))
    )
    (net (code "171") (name "Net-(LED162-DO)") (class "Default")
      (node (ref "LED162") (pin "2") (pinfunction "DO_2") (pintype "bidirectional"))
      (node (ref "LED163") (pin "4") (pinfunction "DI_4") (pintype "bidirectional"))
    )
    (net (code "172") (name "Net-(LED163-DO)") (class "Default")
      (node (ref "LED163") (pin "2") (pinfunction "DO_2") (pintype "bidirectional"))
      (node (ref "LED164") (pin "4") (pinfunction "DI_4") (pintype "bidirectional"))
    )
    (net (code "173") (name "Net-(LED164-DO)") (class "Default")
      (node (ref "LED164") (pin "2") (pinfunction "DO_2") (pintype "bidirectional"))
      (node (ref "LED165") (pin "4") (pinfunction "DI_4") (pintype "bidirectional"))
    )
    (net (code "174") (name "Net-(LED165-DO)") (class "Default")
      (node (ref "LED165") (pin "2") (pinfunction "DO_2") (pintype "bidirectional"))
      (node (ref "LED166") (pin "4") (pinfunction "DI_4") (pintype "bidirectional"))
    )
    (net (code "175") (name "Net-(LED166-DO)") (class "Default")
      (node (ref "LED166") (pin "2") (pinfunction "DO_2") (pintype "bidirectional"))
      (node (ref "LED167") (pin "4") (pinfunction "DI_4") (pintype "bidirectional"))
    )
    (net (code "176") (name "Net-(LED167-DO)") (class "Default")
      (node (ref "LED167") (pin "2") (pinfunction "DO_2") (pintype "bidirectional"))
      (node (ref "LED168") (pin "4") (pinfunction "DI_4") (pintype "bidirectional"))
    )
    (net (code "177") (name "Net-(LED168-DO)") (class "Default")
      (node (ref "LED168") (pin "2") (pinfunction "DO_2") (pintype "bidirectional"))
      (node (ref "LED169") (pin "4") (pinfunction "DI_4") (pintype "bidirectional"))
    )
    (net (code "178") (name "Net-(LED169-DO)") (class "Default")
      (node (ref "LED169") (pin "2") (pinfunction "DO_2") (pintype "bidirectional"))
      (node (ref "LED170") (pin "4") (pinfunction "DI_4") (pintype "bidirectional"))
    )
    (net (code "179") (name "Net-(LED170-DO)") (class "Default")
      (node (ref "LED170") (pin "2") (pinfunction "DO_2") (pintype "bidirectional"))
      (node (ref "LED171") (pin "4") (pinfunction "DI_4") (pintype "bidirectional"))
    )
    (net (code "180") (name "Net-(LED171-DO)") (class "Default")
      (node (ref "LED171") (pin "2") (pinfunction "DO_2") (pintype "bidirectional"))
      (node (ref "LED172") (pin "4") (pinfunction "DI_4") (pintype "bidirectional"))
    )
    (net (code "181") (name "Net-(LED172-DO)") (class "Default")
      (node (ref "LED172") (pin "2") (pinfunction "DO_2") (pintype "bidirectional"))
      (node (ref "LED173") (pin "4") (pinfunction "DI_4") (pintype "bidirectional"))
    )
    (net (code "182") (name "Net-(LED173-DO)") (class "Default")
      (node (ref "LED173") (pin "2") (pinfunction "DO_2") (pintype "bidirectional"))
      (node (ref "LED174") (pin "4") (pinfunction "DI_4") (pintype "bidirectional"))
    )
    (net (code "183") (name "Net-(LED174-DO)") (class "Default")
      (node (ref "LED174") (pin "2") (pinfunction "DO_2") (pintype "bidirectional"))
      (node (ref "LED175") (pin "4") (pinfunction "DI_4") (pintype "bidirectional"))
    )
    (net (code "184") (name "Net-(LED175-DO)") (class "Default")
      (node (ref "LED175") (pin "2") (pinfunction "DO_2") (pintype "bidirectional"))
      (node (ref "LED176") (pin "4") (pinfunction "DI_4") (pintype "bidirectional"))
    )
    (net (code "185") (name "Net-(LED176-DO)") (class "Default")
      (node (ref "LED176") (pin "2") (pinfunction "DO_2") (pintype "bidirectional"))
      (node (ref "LED177") (pin "4") (pinfunction "DI_4") (pintype "bidirectional"))
    )
    (net (code "186") (name "Net-(LED177-DO)") (class "Default")
      (node (ref "LED177") (pin "2") (pinfunction "DO_2") (pintype "bidirectional"))
      (node (ref "LED178") (pin "4") (pinfunction "DI_4") (pintype "bidirectional"))
    )
    (net (code "187") (name "Net-(LED178-DO)") (class "Default")
      (node (ref "LED178") (pin "2") (pinfunction "DO_2") (pintype "bidirectional"))
      (node (ref "LED179") (pin "4") (pinfunction "DI_4") (pintype "bidirectional"))
    )
    (net (code "188") (name "Net-(LED179-DO)") (class "Default")
      (node (ref "LED179") (pin "2") (pinfunction "DO_2") (pintype "bidirectional"))
      (node (ref "LED180") (pin "4") (pinfunction "DI_4") (pintype "bidirectional"))
    )
    (net (code "189") (name "Net-(LED180-DO)") (class "Default")
      (node (ref "LED180") (pin "2") (pinfunction "DO_2") (pintype "bidirectional"))
      (node (ref "LED181") (pin "4") (pinfunction "DI_4") (pintype "bidirectional"))
    )
    (net (code "190") (name "Net-(LED181-DO)") (class "Default")
      (node (ref "LED181") (pin "2") (pinfunction "DO_2") (pintype "bidirectional"))
      (node (ref "LED182") (pin "4") (pinfunction "DI_4") (pintype "bidirectional"))
    )
    (net (code "191") (name "Net-(LED182-DO)") (class "Default")
      (node (ref "LED182") (pin "2") (pinfunction "DO_2") (pintype "bidirectional"))
      (node (ref "LED183") (pin "4") (pinfunction "DI_4") (pintype "bidirectional"))
    )
    (net (code "192") (name "Net-(LED183-DO)") (class "Default")
      (node (ref "LED183") (pin "2") (pinfunction "DO_2") (pintype "bidirectional"))
      (node (ref "LED184") (pin "4") (pinfunction "DI_4") (pintype "bidirectional"))
    )
    (net (code "193") (name "Net-(LED184-DO)") (class "Default")
      (node (ref "LED184") (pin "2") (pinfunction "DO_2") (pintype "bidirectional"))
      (node (ref "LED185") (pin "4") (pinfunction "DI_4") (pintype "bidirectional"))
    )
    (net (code "194") (name "Net-(LED185-DO)") (class "Default")
      (node (ref "LED185") (pin "2") (pinfunction "DO_2") (pintype "bidirectional"))
      (node (ref "LED186") (pin "4") (pinfunction "DI_4") (pintype "bidirectional"))
    )
    (net (code "195") (name "Net-(LED186-DO)") (class "Default")
      (node (ref "LED186") (pin "2") (pinfunction "DO_2") (pintype "bidirectional"))
      (node (ref "LED187") (pin "4") (pinfunction "DI_4") (pintype "bidirectional"))
    )
    (net (code "196") (name "Net-(LED187-DO)") (class "Default")
      (node (ref "LED187") (pin "2") (pinfunction "DO_2") (pintype "bidirectional"))
      (node (ref "LED188") (pin "4") (pinfunction "DI_4") (pintype "bidirectional"))
    )
    (net (code "197") (name "Net-(LED188-DO)") (class "Default")
      (node (ref "LED188") (pin "2") (pinfunction "DO_2") (pintype "bidirectional"))
      (node (ref "LED189") (pin "4") (pinfunction "DI_4") (pintype "bidirectional"))
    )
    (net (code "198") (name "Net-(LED189-DO)") (class "Default")
      (node (ref "LED189") (pin "2") (pinfunction "DO_2") (pintype "bidirectional"))
      (node (ref "LED190") (pin "4") (pinfunction "DI_4") (pintype "bidirectional"))
    )
    (net (code "199") (name "Net-(LED190-DO)") (class "Default")
      (node (ref "LED190") (pin "2") (pinfunction "DO_2") (pintype "bidirectional"))
      (node (ref "LED191") (pin "4") (pinfunction "DI_4") (pintype "bidirectional"))
    )
    (net (code "200") (name "Net-(LED191-DO)") (class "Default")
      (node (ref "LED191") (pin "2") (pinfunction "DO_2") (pintype "bidirectional"))
      (node (ref "LED192") (pin "4") (pinfunction "DI_4") (pintype "bidirectional"))
    )
    (net (code "201") (name "Net-(LED192-DO)") (class "Default")
      (node (ref "LED192") (pin "2") (pinfunction "DO_2") (pintype "bidirectional"))
      (node (ref "PAD24") (pin "1") (pinfunction "P_1") (pintype "passive"))
    )
    (net (code "202") (name "unconnected-(TP1-PadTP)") (class "Default")
      (node (ref "TP1") (pin "TP") (pinfunction "TP_TP") (pintype "input"))
    )
    (net (code "203") (name "unconnected-(TP2-PadTP)") (class "Default")
      (node (ref "TP2") (pin "TP") (pinfunction "TP_TP") (pintype "input"))
    )
    (net (code "204") (name "unconnected-(TP3-PadTP)") (class "Default")
      (node (ref "TP3") (pin "TP") (pinfunction "TP_TP") (pintype "input"))
    )
    (net (code "205") (name "unconnected-(TP4-PadTP)") (class "Default")
      (node (ref "TP4") (pin "TP") (pinfunction "TP_TP") (pintype "input"))
    )
  )
)
